# UCirKitBreadboardTop-0823.net
KiCad netlist of a schematic drawn in EAGLE
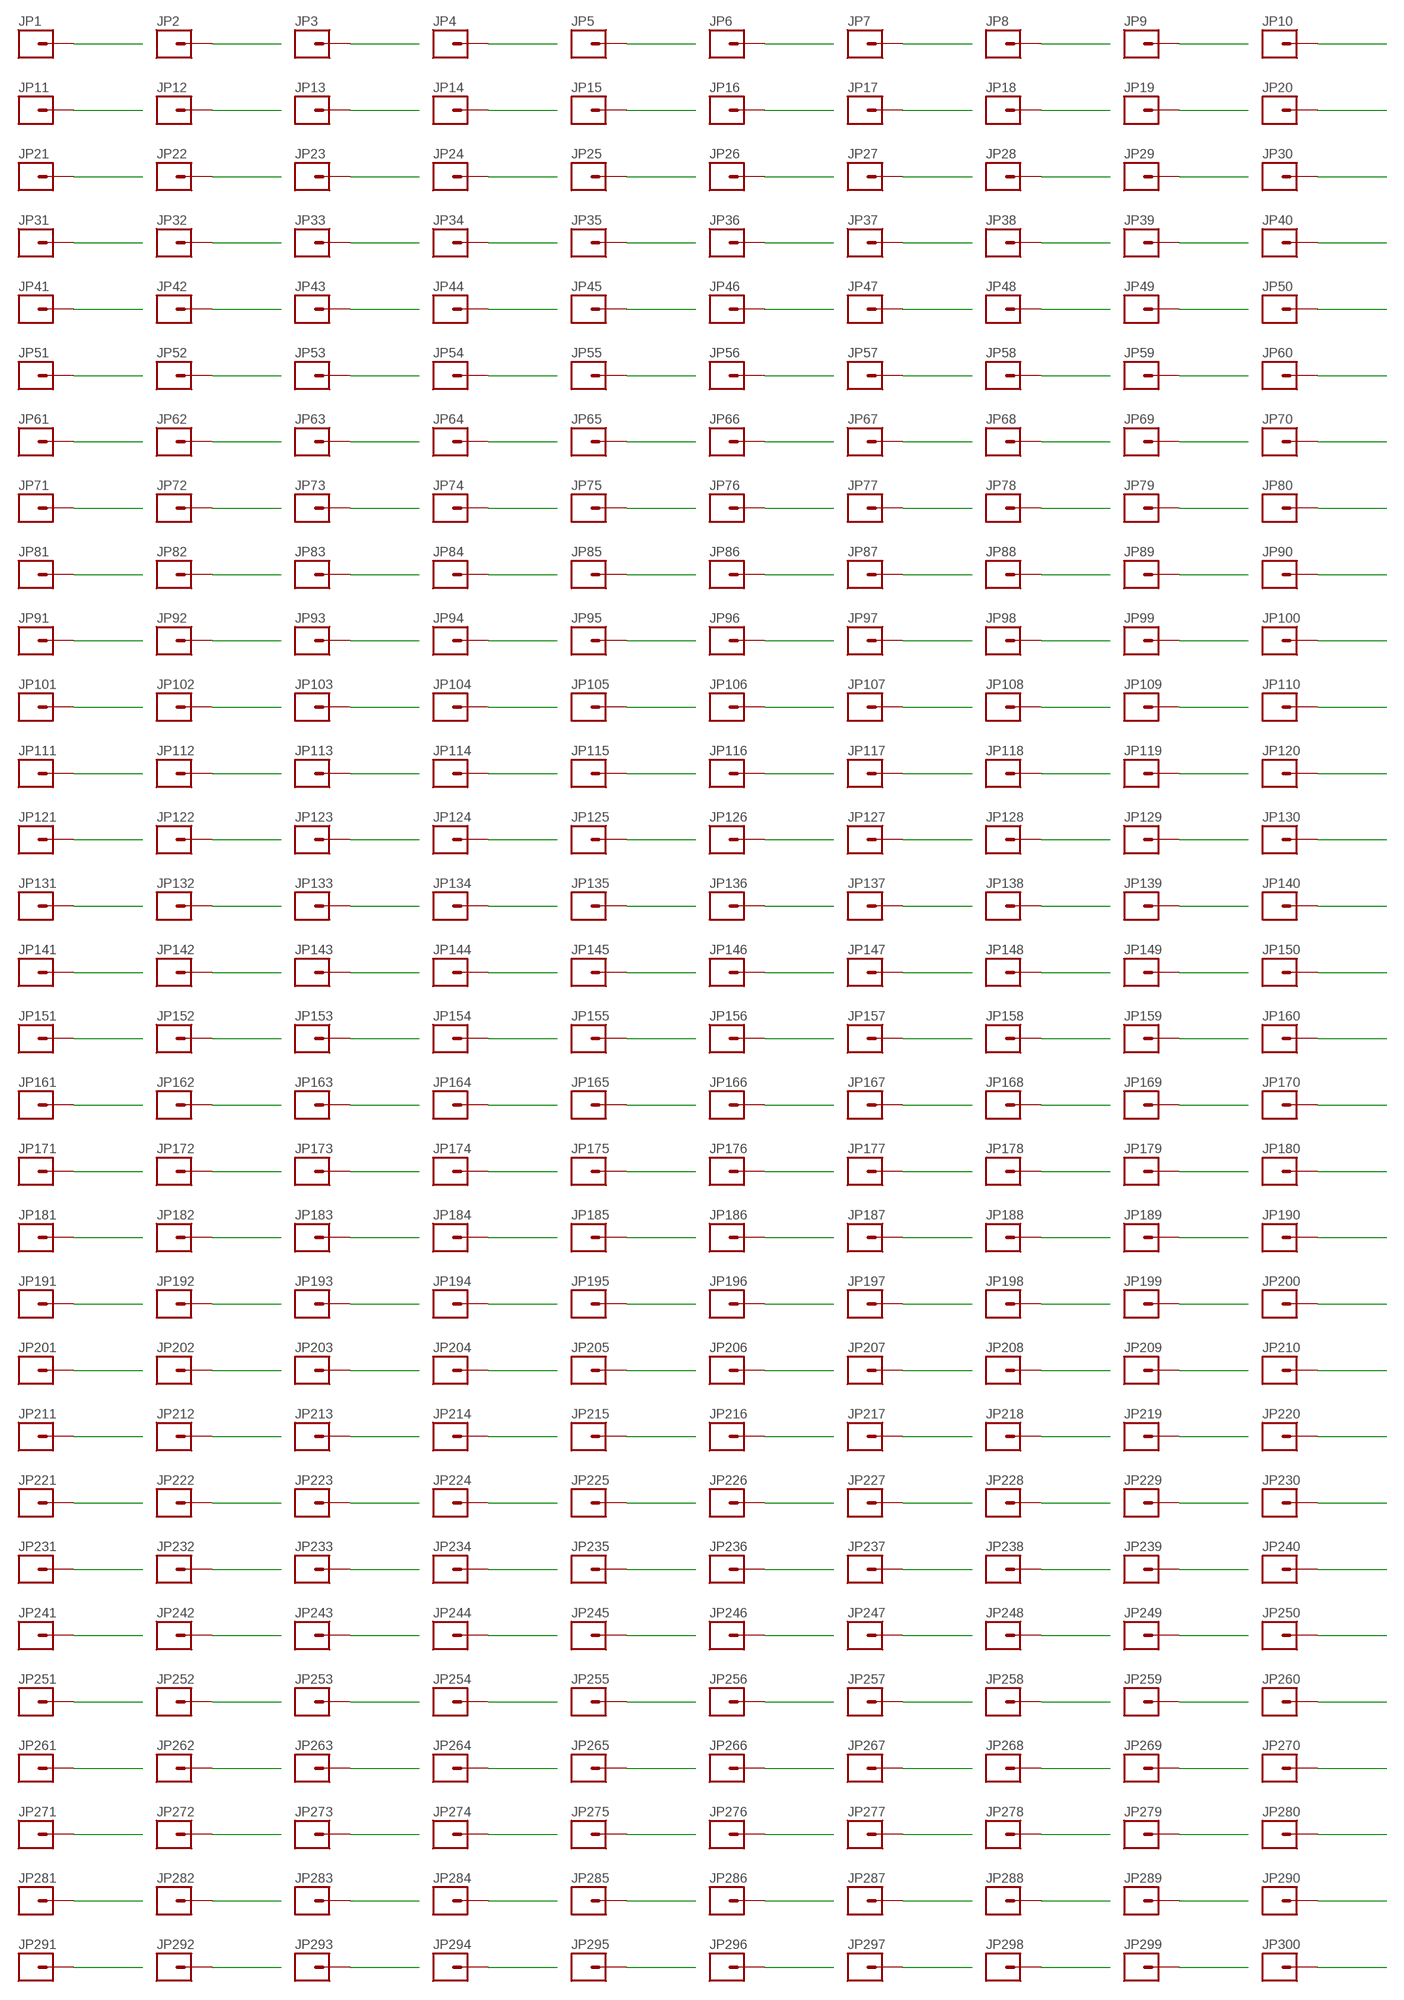
[diagram p0: schematic, sheet 1, part 1 of 2]
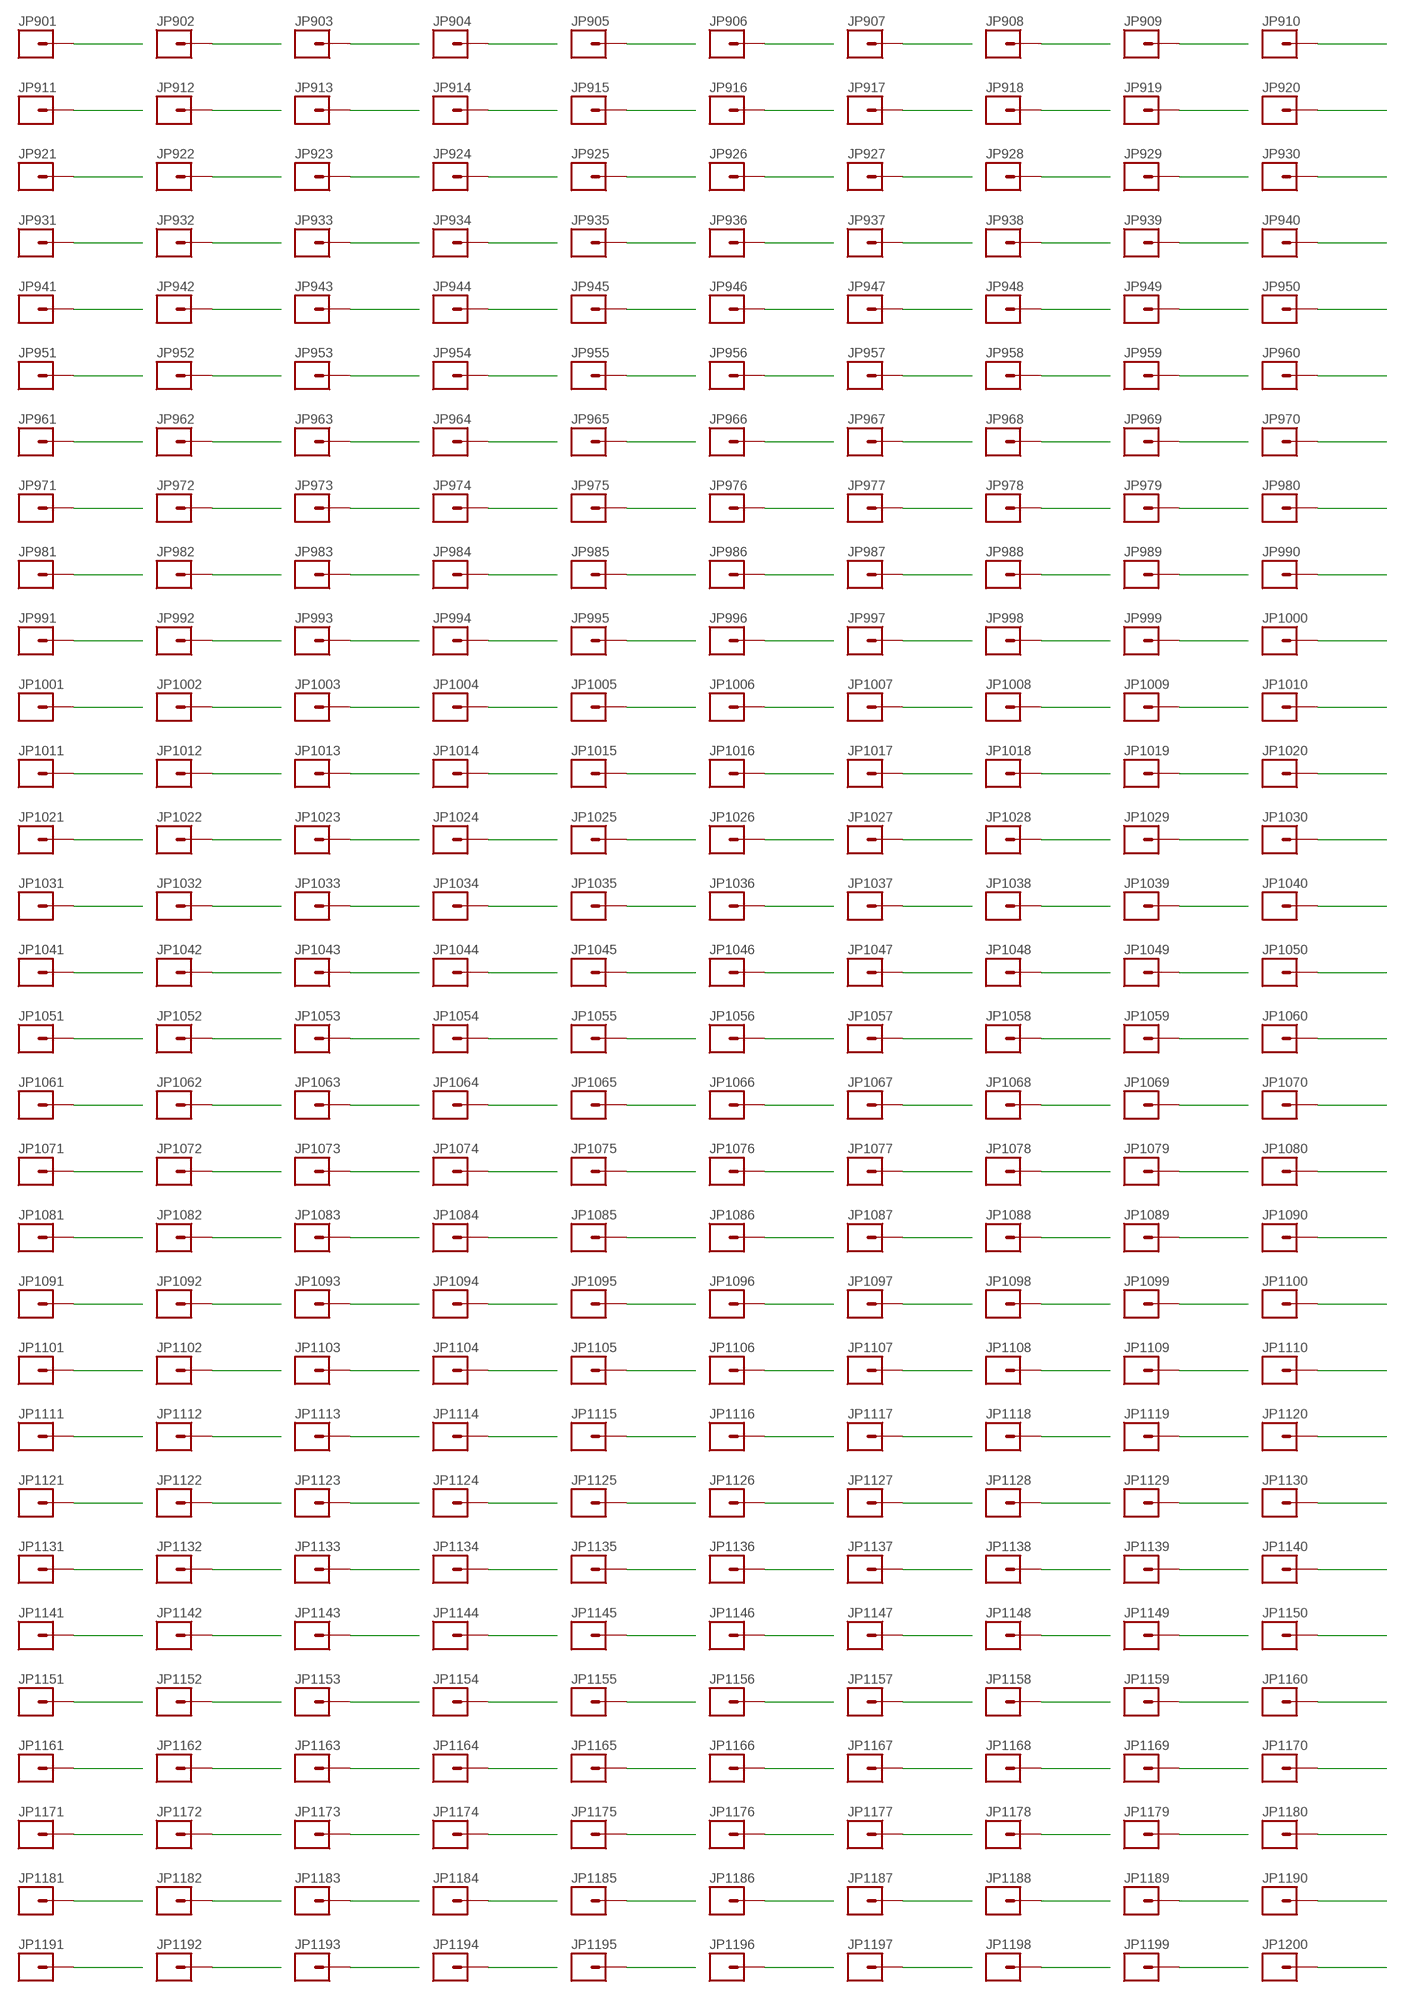
[diagram p1: schematic, sheet 1, part 2 of 2]

(export (version "E")
  (design (tool "Eeschema 10.0.6"))
  (components
    (comp (ref "JP1")
      (value "M01PTH_WITHOUT_TEXT")
      (footprint "eagle-import:1X01_WITHOUT_TEXT")
      (libsource (lib "eagle-import") (part "M01PTH_WITHOUT_TEXT"))
    )
    (comp (ref "JP2")
      (value "M01PTH_WITHOUT_TEXT")
      (footprint "eagle-import:1X01_WITHOUT_TEXT")
      (libsource (lib "eagle-import") (part "M01PTH_WITHOUT_TEXT"))
    )
    (comp (ref "JP3")
      (value "M01PTH_WITHOUT_TEXT")
      (footprint "eagle-import:1X01_WITHOUT_TEXT")
      (libsource (lib "eagle-import") (part "M01PTH_WITHOUT_TEXT"))
    )
    (comp (ref "JP4")
      (value "M01PTH_WITHOUT_TEXT")
      (footprint "eagle-import:1X01_WITHOUT_TEXT")
      (libsource (lib "eagle-import") (part "M01PTH_WITHOUT_TEXT"))
    )
    (comp (ref "JP5")
      (value "M01PTH_WITHOUT_TEXT")
      (footprint "eagle-import:1X01_WITHOUT_TEXT")
      (libsource (lib "eagle-import") (part "M01PTH_WITHOUT_TEXT"))
    )
    (comp (ref "JP6")
      (value "M01PTH_WITHOUT_TEXT")
      (footprint "eagle-import:1X01_WITHOUT_TEXT")
      (libsource (lib "eagle-import") (part "M01PTH_WITHOUT_TEXT"))
    )
    (comp (ref "JP7")
      (value "M01PTH_WITHOUT_TEXT")
      (footprint "eagle-import:1X01_WITHOUT_TEXT")
      (libsource (lib "eagle-import") (part "M01PTH_WITHOUT_TEXT"))
    )
    (comp (ref "JP8")
      (value "M01PTH_WITHOUT_TEXT")
      (footprint "eagle-import:1X01_WITHOUT_TEXT")
      (libsource (lib "eagle-import") (part "M01PTH_WITHOUT_TEXT"))
    )
    (comp (ref "JP9")
      (value "M01PTH_WITHOUT_TEXT")
      (footprint "eagle-import:1X01_WITHOUT_TEXT")
      (libsource (lib "eagle-import") (part "M01PTH_WITHOUT_TEXT"))
    )
    (comp (ref "JP10")
      (value "M01PTH_WITHOUT_TEXT")
      (footprint "eagle-import:1X01_WITHOUT_TEXT")
      (libsource (lib "eagle-import") (part "M01PTH_WITHOUT_TEXT"))
    )
    (comp (ref "JP11")
      (value "M01PTH_WITHOUT_TEXT")
      (footprint "eagle-import:1X01_WITHOUT_TEXT")
      (libsource (lib "eagle-import") (part "M01PTH_WITHOUT_TEXT"))
    )
    (comp (ref "JP12")
      (value "M01PTH_WITHOUT_TEXT")
      (footprint "eagle-import:1X01_WITHOUT_TEXT")
      (libsource (lib "eagle-import") (part "M01PTH_WITHOUT_TEXT"))
    )
    (comp (ref "JP13")
      (value "M01PTH_WITHOUT_TEXT")
      (footprint "eagle-import:1X01_WITHOUT_TEXT")
      (libsource (lib "eagle-import") (part "M01PTH_WITHOUT_TEXT"))
    )
    (comp (ref "JP14")
      (value "M01PTH_WITHOUT_TEXT")
      (footprint "eagle-import:1X01_WITHOUT_TEXT")
      (libsource (lib "eagle-import") (part "M01PTH_WITHOUT_TEXT"))
    )
    (comp (ref "JP15")
      (value "M01PTH_WITHOUT_TEXT")
      (footprint "eagle-import:1X01_WITHOUT_TEXT")
      (libsource (lib "eagle-import") (part "M01PTH_WITHOUT_TEXT"))
    )
    (comp (ref "JP16")
      (value "M01PTH_WITHOUT_TEXT")
      (footprint "eagle-import:1X01_WITHOUT_TEXT")
      (libsource (lib "eagle-import") (part "M01PTH_WITHOUT_TEXT"))
    )
    (comp (ref "JP17")
      (value "M01PTH_WITHOUT_TEXT")
      (footprint "eagle-import:1X01_WITHOUT_TEXT")
      (libsource (lib "eagle-import") (part "M01PTH_WITHOUT_TEXT"))
    )
    (comp (ref "JP18")
      (value "M01PTH_WITHOUT_TEXT")
      (footprint "eagle-import:1X01_WITHOUT_TEXT")
      (libsource (lib "eagle-import") (part "M01PTH_WITHOUT_TEXT"))
    )
    (comp (ref "JP19")
      (value "M01PTH_WITHOUT_TEXT")
      (footprint "eagle-import:1X01_WITHOUT_TEXT")
      (libsource (lib "eagle-import") (part "M01PTH_WITHOUT_TEXT"))
    )
    (comp (ref "JP20")
      (value "M01PTH_WITHOUT_TEXT")
      (footprint "eagle-import:1X01_WITHOUT_TEXT")
      (libsource (lib "eagle-import") (part "M01PTH_WITHOUT_TEXT"))
    )
    (comp (ref "JP21")
      (value "M01PTH_WITHOUT_TEXT")
      (footprint "eagle-import:1X01_WITHOUT_TEXT")
      (libsource (lib "eagle-import") (part "M01PTH_WITHOUT_TEXT"))
    )
    (comp (ref "JP22")
      (value "M01PTH_WITHOUT_TEXT")
      (footprint "eagle-import:1X01_WITHOUT_TEXT")
      (libsource (lib "eagle-import") (part "M01PTH_WITHOUT_TEXT"))
    )
    (comp (ref "JP23")
      (value "M01PTH_WITHOUT_TEXT")
      (footprint "eagle-import:1X01_WITHOUT_TEXT")
      (libsource (lib "eagle-import") (part "M01PTH_WITHOUT_TEXT"))
    )
    (comp (ref "JP24")
      (value "M01PTH_WITHOUT_TEXT")
      (footprint "eagle-import:1X01_WITHOUT_TEXT")
      (libsource (lib "eagle-import") (part "M01PTH_WITHOUT_TEXT"))
    )
    (comp (ref "JP25")
      (value "M01PTH_WITHOUT_TEXT")
      (footprint "eagle-import:1X01_WITHOUT_TEXT")
      (libsource (lib "eagle-import") (part "M01PTH_WITHOUT_TEXT"))
    )
    (comp (ref "JP26")
      (value "M01PTH_WITHOUT_TEXT")
      (footprint "eagle-import:1X01_WITHOUT_TEXT")
      (libsource (lib "eagle-import") (part "M01PTH_WITHOUT_TEXT"))
    )
    (comp (ref "JP27")
      (value "M01PTH_WITHOUT_TEXT")
      (footprint "eagle-import:1X01_WITHOUT_TEXT")
      (libsource (lib "eagle-import") (part "M01PTH_WITHOUT_TEXT"))
    )
    (comp (ref "JP28")
      (value "M01PTH_WITHOUT_TEXT")
      (footprint "eagle-import:1X01_WITHOUT_TEXT")
      (libsource (lib "eagle-import") (part "M01PTH_WITHOUT_TEXT"))
    )
    (comp (ref "JP29")
      (value "M01PTH_WITHOUT_TEXT")
      (footprint "eagle-import:1X01_WITHOUT_TEXT")
      (libsource (lib "eagle-import") (part "M01PTH_WITHOUT_TEXT"))
    )
    (comp (ref "JP30")
      (value "M01PTH_WITHOUT_TEXT")
      (footprint "eagle-import:1X01_WITHOUT_TEXT")
      (libsource (lib "eagle-import") (part "M01PTH_WITHOUT_TEXT"))
    )
    (comp (ref "JP31")
      (value "M01PTH_WITHOUT_TEXT")
      (footprint "eagle-import:1X01_WITHOUT_TEXT")
      (libsource (lib "eagle-import") (part "M01PTH_WITHOUT_TEXT"))
    )
    (comp (ref "JP32")
      (value "M01PTH_WITHOUT_TEXT")
      (footprint "eagle-import:1X01_WITHOUT_TEXT")
      (libsource (lib "eagle-import") (part "M01PTH_WITHOUT_TEXT"))
    )
    (comp (ref "JP33")
      (value "M01PTH_WITHOUT_TEXT")
      (footprint "eagle-import:1X01_WITHOUT_TEXT")
      (libsource (lib "eagle-import") (part "M01PTH_WITHOUT_TEXT"))
    )
    (comp (ref "JP34")
      (value "M01PTH_WITHOUT_TEXT")
      (footprint "eagle-import:1X01_WITHOUT_TEXT")
      (libsource (lib "eagle-import") (part "M01PTH_WITHOUT_TEXT"))
    )
    (comp (ref "JP35")
      (value "M01PTH_WITHOUT_TEXT")
      (footprint "eagle-import:1X01_WITHOUT_TEXT")
      (libsource (lib "eagle-import") (part "M01PTH_WITHOUT_TEXT"))
    )
    (comp (ref "JP36")
      (value "M01PTH_WITHOUT_TEXT")
      (footprint "eagle-import:1X01_WITHOUT_TEXT")
      (libsource (lib "eagle-import") (part "M01PTH_WITHOUT_TEXT"))
    )
    (comp (ref "JP37")
      (value "M01PTH_WITHOUT_TEXT")
      (footprint "eagle-import:1X01_WITHOUT_TEXT")
      (libsource (lib "eagle-import") (part "M01PTH_WITHOUT_TEXT"))
    )
    (comp (ref "JP38")
      (value "M01PTH_WITHOUT_TEXT")
      (footprint "eagle-import:1X01_WITHOUT_TEXT")
      (libsource (lib "eagle-import") (part "M01PTH_WITHOUT_TEXT"))
    )
    (comp (ref "JP39")
      (value "M01PTH_WITHOUT_TEXT")
      (footprint "eagle-import:1X01_WITHOUT_TEXT")
      (libsource (lib "eagle-import") (part "M01PTH_WITHOUT_TEXT"))
    )
    (comp (ref "JP40")
      (value "M01PTH_WITHOUT_TEXT")
      (footprint "eagle-import:1X01_WITHOUT_TEXT")
      (libsource (lib "eagle-import") (part "M01PTH_WITHOUT_TEXT"))
    )
    (comp (ref "JP41")
      (value "M01PTH_WITHOUT_TEXT")
      (footprint "eagle-import:1X01_WITHOUT_TEXT")
      (libsource (lib "eagle-import") (part "M01PTH_WITHOUT_TEXT"))
    )
    (comp (ref "JP42")
      (value "M01PTH_WITHOUT_TEXT")
      (footprint "eagle-import:1X01_WITHOUT_TEXT")
      (libsource (lib "eagle-import") (part "M01PTH_WITHOUT_TEXT"))
    )
    (comp (ref "JP43")
      (value "M01PTH_WITHOUT_TEXT")
      (footprint "eagle-import:1X01_WITHOUT_TEXT")
      (libsource (lib "eagle-import") (part "M01PTH_WITHOUT_TEXT"))
    )
    (comp (ref "JP44")
      (value "M01PTH_WITHOUT_TEXT")
      (footprint "eagle-import:1X01_WITHOUT_TEXT")
      (libsource (lib "eagle-import") (part "M01PTH_WITHOUT_TEXT"))
    )
    (comp (ref "JP45")
      (value "M01PTH_WITHOUT_TEXT")
      (footprint "eagle-import:1X01_WITHOUT_TEXT")
      (libsource (lib "eagle-import") (part "M01PTH_WITHOUT_TEXT"))
    )
    (comp (ref "JP46")
      (value "M01PTH_WITHOUT_TEXT")
      (footprint "eagle-import:1X01_WITHOUT_TEXT")
      (libsource (lib "eagle-import") (part "M01PTH_WITHOUT_TEXT"))
    )
    (comp (ref "JP47")
      (value "M01PTH_WITHOUT_TEXT")
      (footprint "eagle-import:1X01_WITHOUT_TEXT")
      (libsource (lib "eagle-import") (part "M01PTH_WITHOUT_TEXT"))
    )
    (comp (ref "JP48")
      (value "M01PTH_WITHOUT_TEXT")
      (footprint "eagle-import:1X01_WITHOUT_TEXT")
      (libsource (lib "eagle-import") (part "M01PTH_WITHOUT_TEXT"))
    )
    (comp (ref "JP49")
      (value "M01PTH_WITHOUT_TEXT")
      (footprint "eagle-import:1X01_WITHOUT_TEXT")
      (libsource (lib "eagle-import") (part "M01PTH_WITHOUT_TEXT"))
    )
    (comp (ref "JP50")
      (value "M01PTH_WITHOUT_TEXT")
      (footprint "eagle-import:1X01_WITHOUT_TEXT")
      (libsource (lib "eagle-import") (part "M01PTH_WITHOUT_TEXT"))
    )
    (comp (ref "JP51")
      (value "M01PTH_WITHOUT_TEXT")
      (footprint "eagle-import:1X01_WITHOUT_TEXT")
      (libsource (lib "eagle-import") (part "M01PTH_WITHOUT_TEXT"))
    )
    (comp (ref "JP52")
      (value "M01PTH_WITHOUT_TEXT")
      (footprint "eagle-import:1X01_WITHOUT_TEXT")
      (libsource (lib "eagle-import") (part "M01PTH_WITHOUT_TEXT"))
    )
    (comp (ref "JP53")
      (value "M01PTH_WITHOUT_TEXT")
      (footprint "eagle-import:1X01_WITHOUT_TEXT")
      (libsource (lib "eagle-import") (part "M01PTH_WITHOUT_TEXT"))
    )
    (comp (ref "JP54")
      (value "M01PTH_WITHOUT_TEXT")
      (footprint "eagle-import:1X01_WITHOUT_TEXT")
      (libsource (lib "eagle-import") (part "M01PTH_WITHOUT_TEXT"))
    )
    (comp (ref "JP55")
      (value "M01PTH_WITHOUT_TEXT")
      (footprint "eagle-import:1X01_WITHOUT_TEXT")
      (libsource (lib "eagle-import") (part "M01PTH_WITHOUT_TEXT"))
    )
    (comp (ref "JP56")
      (value "M01PTH_WITHOUT_TEXT")
      (footprint "eagle-import:1X01_WITHOUT_TEXT")
      (libsource (lib "eagle-import") (part "M01PTH_WITHOUT_TEXT"))
    )
    (comp (ref "JP57")
      (value "M01PTH_WITHOUT_TEXT")
      (footprint "eagle-import:1X01_WITHOUT_TEXT")
      (libsource (lib "eagle-import") (part "M01PTH_WITHOUT_TEXT"))
    )
    (comp (ref "JP58")
      (value "M01PTH_WITHOUT_TEXT")
      (footprint "eagle-import:1X01_WITHOUT_TEXT")
      (libsource (lib "eagle-import") (part "M01PTH_WITHOUT_TEXT"))
    )
    (comp (ref "JP59")
      (value "M01PTH_WITHOUT_TEXT")
      (footprint "eagle-import:1X01_WITHOUT_TEXT")
      (libsource (lib "eagle-import") (part "M01PTH_WITHOUT_TEXT"))
    )
    (comp (ref "JP60")
      (value "M01PTH_WITHOUT_TEXT")
      (footprint "eagle-import:1X01_WITHOUT_TEXT")
      (libsource (lib "eagle-import") (part "M01PTH_WITHOUT_TEXT"))
    )
    (comp (ref "JP61")
      (value "M01PTH_WITHOUT_TEXT")
      (footprint "eagle-import:1X01_WITHOUT_TEXT")
      (libsource (lib "eagle-import") (part "M01PTH_WITHOUT_TEXT"))
    )
    (comp (ref "JP62")
      (value "M01PTH_WITHOUT_TEXT")
      (footprint "eagle-import:1X01_WITHOUT_TEXT")
      (libsource (lib "eagle-import") (part "M01PTH_WITHOUT_TEXT"))
    )
    (comp (ref "JP63")
      (value "M01PTH_WITHOUT_TEXT")
      (footprint "eagle-import:1X01_WITHOUT_TEXT")
      (libsource (lib "eagle-import") (part "M01PTH_WITHOUT_TEXT"))
    )
    (comp (ref "JP64")
      (value "M01PTH_WITHOUT_TEXT")
      (footprint "eagle-import:1X01_WITHOUT_TEXT")
      (libsource (lib "eagle-import") (part "M01PTH_WITHOUT_TEXT"))
    )
    (comp (ref "JP65")
      (value "M01PTH_WITHOUT_TEXT")
      (footprint "eagle-import:1X01_WITHOUT_TEXT")
      (libsource (lib "eagle-import") (part "M01PTH_WITHOUT_TEXT"))
    )
    (comp (ref "JP66")
      (value "M01PTH_WITHOUT_TEXT")
      (footprint "eagle-import:1X01_WITHOUT_TEXT")
      (libsource (lib "eagle-import") (part "M01PTH_WITHOUT_TEXT"))
    )
    (comp (ref "JP67")
      (value "M01PTH_WITHOUT_TEXT")
      (footprint "eagle-import:1X01_WITHOUT_TEXT")
      (libsource (lib "eagle-import") (part "M01PTH_WITHOUT_TEXT"))
    )
    (comp (ref "JP68")
      (value "M01PTH_WITHOUT_TEXT")
      (footprint "eagle-import:1X01_WITHOUT_TEXT")
      (libsource (lib "eagle-import") (part "M01PTH_WITHOUT_TEXT"))
    )
    (comp (ref "JP69")
      (value "M01PTH_WITHOUT_TEXT")
      (footprint "eagle-import:1X01_WITHOUT_TEXT")
      (libsource (lib "eagle-import") (part "M01PTH_WITHOUT_TEXT"))
    )
    (comp (ref "JP70")
      (value "M01PTH_WITHOUT_TEXT")
      (footprint "eagle-import:1X01_WITHOUT_TEXT")
      (libsource (lib "eagle-import") (part "M01PTH_WITHOUT_TEXT"))
    )
    (comp (ref "JP71")
      (value "M01PTH_WITHOUT_TEXT")
      (footprint "eagle-import:1X01_WITHOUT_TEXT")
      (libsource (lib "eagle-import") (part "M01PTH_WITHOUT_TEXT"))
    )
    (comp (ref "JP72")
      (value "M01PTH_WITHOUT_TEXT")
      (footprint "eagle-import:1X01_WITHOUT_TEXT")
      (libsource (lib "eagle-import") (part "M01PTH_WITHOUT_TEXT"))
    )
    (comp (ref "JP73")
      (value "M01PTH_WITHOUT_TEXT")
      (footprint "eagle-import:1X01_WITHOUT_TEXT")
      (libsource (lib "eagle-import") (part "M01PTH_WITHOUT_TEXT"))
    )
    (comp (ref "JP74")
      (value "M01PTH_WITHOUT_TEXT")
      (footprint "eagle-import:1X01_WITHOUT_TEXT")
      (libsource (lib "eagle-import") (part "M01PTH_WITHOUT_TEXT"))
    )
    (comp (ref "JP75")
      (value "M01PTH_WITHOUT_TEXT")
      (footprint "eagle-import:1X01_WITHOUT_TEXT")
      (libsource (lib "eagle-import") (part "M01PTH_WITHOUT_TEXT"))
    )
    (comp (ref "JP76")
      (value "M01PTH_WITHOUT_TEXT")
      (footprint "eagle-import:1X01_WITHOUT_TEXT")
      (libsource (lib "eagle-import") (part "M01PTH_WITHOUT_TEXT"))
    )
    (comp (ref "JP77")
      (value "M01PTH_WITHOUT_TEXT")
      (footprint "eagle-import:1X01_WITHOUT_TEXT")
      (libsource (lib "eagle-import") (part "M01PTH_WITHOUT_TEXT"))
    )
    (comp (ref "JP78")
      (value "M01PTH_WITHOUT_TEXT")
      (footprint "eagle-import:1X01_WITHOUT_TEXT")
      (libsource (lib "eagle-import") (part "M01PTH_WITHOUT_TEXT"))
    )
    (comp (ref "JP79")
      (value "M01PTH_WITHOUT_TEXT")
      (footprint "eagle-import:1X01_WITHOUT_TEXT")
      (libsource (lib "eagle-import") (part "M01PTH_WITHOUT_TEXT"))
    )
    (comp (ref "JP80")
      (value "M01PTH_WITHOUT_TEXT")
      (footprint "eagle-import:1X01_WITHOUT_TEXT")
      (libsource (lib "eagle-import") (part "M01PTH_WITHOUT_TEXT"))
    )
    (comp (ref "JP81")
      (value "M01PTH_WITHOUT_TEXT")
      (footprint "eagle-import:1X01_WITHOUT_TEXT")
      (libsource (lib "eagle-import") (part "M01PTH_WITHOUT_TEXT"))
    )
    (comp (ref "JP82")
      (value "M01PTH_WITHOUT_TEXT")
      (footprint "eagle-import:1X01_WITHOUT_TEXT")
      (libsource (lib "eagle-import") (part "M01PTH_WITHOUT_TEXT"))
    )
    (comp (ref "JP83")
      (value "M01PTH_WITHOUT_TEXT")
      (footprint "eagle-import:1X01_WITHOUT_TEXT")
      (libsource (lib "eagle-import") (part "M01PTH_WITHOUT_TEXT"))
    )
    (comp (ref "JP84")
      (value "M01PTH_WITHOUT_TEXT")
      (footprint "eagle-import:1X01_WITHOUT_TEXT")
      (libsource (lib "eagle-import") (part "M01PTH_WITHOUT_TEXT"))
    )
    (comp (ref "JP85")
      (value "M01PTH_WITHOUT_TEXT")
      (footprint "eagle-import:1X01_WITHOUT_TEXT")
      (libsource (lib "eagle-import") (part "M01PTH_WITHOUT_TEXT"))
    )
    (comp (ref "JP86")
      (value "M01PTH_WITHOUT_TEXT")
      (footprint "eagle-import:1X01_WITHOUT_TEXT")
      (libsource (lib "eagle-import") (part "M01PTH_WITHOUT_TEXT"))
    )
    (comp (ref "JP87")
      (value "M01PTH_WITHOUT_TEXT")
      (footprint "eagle-import:1X01_WITHOUT_TEXT")
      (libsource (lib "eagle-import") (part "M01PTH_WITHOUT_TEXT"))
    )
    (comp (ref "JP88")
      (value "M01PTH_WITHOUT_TEXT")
      (footprint "eagle-import:1X01_WITHOUT_TEXT")
      (libsource (lib "eagle-import") (part "M01PTH_WITHOUT_TEXT"))
    )
    (comp (ref "JP89")
      (value "M01PTH_WITHOUT_TEXT")
      (footprint "eagle-import:1X01_WITHOUT_TEXT")
      (libsource (lib "eagle-import") (part "M01PTH_WITHOUT_TEXT"))
    )
    (comp (ref "JP90")
      (value "M01PTH_WITHOUT_TEXT")
      (footprint "eagle-import:1X01_WITHOUT_TEXT")
      (libsource (lib "eagle-import") (part "M01PTH_WITHOUT_TEXT"))
    )
    (comp (ref "JP91")
      (value "M01PTH_WITHOUT_TEXT")
      (footprint "eagle-import:1X01_WITHOUT_TEXT")
      (libsource (lib "eagle-import") (part "M01PTH_WITHOUT_TEXT"))
    )
    (comp (ref "JP92")
      (value "M01PTH_WITHOUT_TEXT")
      (footprint "eagle-import:1X01_WITHOUT_TEXT")
      (libsource (lib "eagle-import") (part "M01PTH_WITHOUT_TEXT"))
    )
    (comp (ref "JP93")
      (value "M01PTH_WITHOUT_TEXT")
      (footprint "eagle-import:1X01_WITHOUT_TEXT")
      (libsource (lib "eagle-import") (part "M01PTH_WITHOUT_TEXT"))
    )
    (comp (ref "JP94")
      (value "M01PTH_WITHOUT_TEXT")
      (footprint "eagle-import:1X01_WITHOUT_TEXT")
      (libsource (lib "eagle-import") (part "M01PTH_WITHOUT_TEXT"))
    )
    (comp (ref "JP95")
      (value "M01PTH_WITHOUT_TEXT")
      (footprint "eagle-import:1X01_WITHOUT_TEXT")
      (libsource (lib "eagle-import") (part "M01PTH_WITHOUT_TEXT"))
    )
    (comp (ref "JP96")
      (value "M01PTH_WITHOUT_TEXT")
      (footprint "eagle-import:1X01_WITHOUT_TEXT")
      (libsource (lib "eagle-import") (part "M01PTH_WITHOUT_TEXT"))
    )
    (comp (ref "JP97")
      (value "M01PTH_WITHOUT_TEXT")
      (footprint "eagle-import:1X01_WITHOUT_TEXT")
      (libsource (lib "eagle-import") (part "M01PTH_WITHOUT_TEXT"))
    )
    (comp (ref "JP98")
      (value "M01PTH_WITHOUT_TEXT")
      (footprint "eagle-import:1X01_WITHOUT_TEXT")
      (libsource (lib "eagle-import") (part "M01PTH_WITHOUT_TEXT"))
    )
    (comp (ref "JP99")
      (value "M01PTH_WITHOUT_TEXT")
      (footprint "eagle-import:1X01_WITHOUT_TEXT")
      (libsource (lib "eagle-import") (part "M01PTH_WITHOUT_TEXT"))
    )
    (comp (ref "JP100")
      (value "M01PTH_WITHOUT_TEXT")
      (footprint "eagle-import:1X01_WITHOUT_TEXT")
      (libsource (lib "eagle-import") (part "M01PTH_WITHOUT_TEXT"))
    )
    (comp (ref "JP101")
      (value "M01PTH_WITHOUT_TEXT")
      (footprint "eagle-import:1X01_WITHOUT_TEXT")
      (libsource (lib "eagle-import") (part "M01PTH_WITHOUT_TEXT"))
    )
    (comp (ref "JP102")
      (value "M01PTH_WITHOUT_TEXT")
      (footprint "eagle-import:1X01_WITHOUT_TEXT")
      (libsource (lib "eagle-import") (part "M01PTH_WITHOUT_TEXT"))
    )
    (comp (ref "JP103")
      (value "M01PTH_WITHOUT_TEXT")
      (footprint "eagle-import:1X01_WITHOUT_TEXT")
      (libsource (lib "eagle-import") (part "M01PTH_WITHOUT_TEXT"))
    )
    (comp (ref "JP104")
      (value "M01PTH_WITHOUT_TEXT")
      (footprint "eagle-import:1X01_WITHOUT_TEXT")
      (libsource (lib "eagle-import") (part "M01PTH_WITHOUT_TEXT"))
    )
    (comp (ref "JP105")
      (value "M01PTH_WITHOUT_TEXT")
      (footprint "eagle-import:1X01_WITHOUT_TEXT")
      (libsource (lib "eagle-import") (part "M01PTH_WITHOUT_TEXT"))
    )
    (comp (ref "JP106")
      (value "M01PTH_WITHOUT_TEXT")
      (footprint "eagle-import:1X01_WITHOUT_TEXT")
      (libsource (lib "eagle-import") (part "M01PTH_WITHOUT_TEXT"))
    )
    (comp (ref "JP107")
      (value "M01PTH_WITHOUT_TEXT")
      (footprint "eagle-import:1X01_WITHOUT_TEXT")
      (libsource (lib "eagle-import") (part "M01PTH_WITHOUT_TEXT"))
    )
    (comp (ref "JP108")
      (value "M01PTH_WITHOUT_TEXT")
      (footprint "eagle-import:1X01_WITHOUT_TEXT")
      (libsource (lib "eagle-import") (part "M01PTH_WITHOUT_TEXT"))
    )
    (comp (ref "JP109")
      (value "M01PTH_WITHOUT_TEXT")
      (footprint "eagle-import:1X01_WITHOUT_TEXT")
      (libsource (lib "eagle-import") (part "M01PTH_WITHOUT_TEXT"))
    )
    (comp (ref "JP110")
      (value "M01PTH_WITHOUT_TEXT")
      (footprint "eagle-import:1X01_WITHOUT_TEXT")
      (libsource (lib "eagle-import") (part "M01PTH_WITHOUT_TEXT"))
    )
    (comp (ref "JP111")
      (value "M01PTH_WITHOUT_TEXT")
      (footprint "eagle-import:1X01_WITHOUT_TEXT")
      (libsource (lib "eagle-import") (part "M01PTH_WITHOUT_TEXT"))
    )
    (comp (ref "JP112")
      (value "M01PTH_WITHOUT_TEXT")
      (footprint "eagle-import:1X01_WITHOUT_TEXT")
      (libsource (lib "eagle-import") (part "M01PTH_WITHOUT_TEXT"))
    )
    (comp (ref "JP113")
      (value "M01PTH_WITHOUT_TEXT")
      (footprint "eagle-import:1X01_WITHOUT_TEXT")
      (libsource (lib "eagle-import") (part "M01PTH_WITHOUT_TEXT"))
    )
    (comp (ref "JP114")
      (value "M01PTH_WITHOUT_TEXT")
      (footprint "eagle-import:1X01_WITHOUT_TEXT")
      (libsource (lib "eagle-import") (part "M01PTH_WITHOUT_TEXT"))
    )
    (comp (ref "JP115")
      (value "M01PTH_WITHOUT_TEXT")
      (footprint "eagle-import:1X01_WITHOUT_TEXT")
      (libsource (lib "eagle-import") (part "M01PTH_WITHOUT_TEXT"))
    )
    (comp (ref "JP116")
      (value "M01PTH_WITHOUT_TEXT")
      (footprint "eagle-import:1X01_WITHOUT_TEXT")
      (libsource (lib "eagle-import") (part "M01PTH_WITHOUT_TEXT"))
    )
    (comp (ref "JP117")
      (value "M01PTH_WITHOUT_TEXT")
      (footprint "eagle-import:1X01_WITHOUT_TEXT")
      (libsource (lib "eagle-import") (part "M01PTH_WITHOUT_TEXT"))
    )
    (comp (ref "JP118")
      (value "M01PTH_WITHOUT_TEXT")
      (footprint "eagle-import:1X01_WITHOUT_TEXT")
      (libsource (lib "eagle-import") (part "M01PTH_WITHOUT_TEXT"))
    )
    (comp (ref "JP119")
      (value "M01PTH_WITHOUT_TEXT")
      (footprint "eagle-import:1X01_WITHOUT_TEXT")
      (libsource (lib "eagle-import") (part "M01PTH_WITHOUT_TEXT"))
    )
    (comp (ref "JP120")
      (value "M01PTH_WITHOUT_TEXT")
      (footprint "eagle-import:1X01_WITHOUT_TEXT")
      (libsource (lib "eagle-import") (part "M01PTH_WITHOUT_TEXT"))
    )
    (comp (ref "JP121")
      (value "M01PTH_WITHOUT_TEXT")
      (footprint "eagle-import:1X01_WITHOUT_TEXT")
      (libsource (lib "eagle-import") (part "M01PTH_WITHOUT_TEXT"))
    )
    (comp (ref "JP122")
      (value "M01PTH_WITHOUT_TEXT")
      (footprint "eagle-import:1X01_WITHOUT_TEXT")
      (libsource (lib "eagle-import") (part "M01PTH_WITHOUT_TEXT"))
    )
    (comp (ref "JP123")
      (value "M01PTH_WITHOUT_TEXT")
      (footprint "eagle-import:1X01_WITHOUT_TEXT")
      (libsource (lib "eagle-import") (part "M01PTH_WITHOUT_TEXT"))
    )
    (comp (ref "JP124")
      (value "M01PTH_WITHOUT_TEXT")
      (footprint "eagle-import:1X01_WITHOUT_TEXT")
      (libsource (lib "eagle-import") (part "M01PTH_WITHOUT_TEXT"))
    )
    (comp (ref "JP125")
      (value "M01PTH_WITHOUT_TEXT")
      (footprint "eagle-import:1X01_WITHOUT_TEXT")
      (libsource (lib "eagle-import") (part "M01PTH_WITHOUT_TEXT"))
    )
    (comp (ref "JP126")
      (value "M01PTH_WITHOUT_TEXT")
      (footprint "eagle-import:1X01_WITHOUT_TEXT")
      (libsource (lib "eagle-import") (part "M01PTH_WITHOUT_TEXT"))
    )
    (comp (ref "JP127")
      (value "M01PTH_WITHOUT_TEXT")
      (footprint "eagle-import:1X01_WITHOUT_TEXT")
      (libsource (lib "eagle-import") (part "M01PTH_WITHOUT_TEXT"))
    )
    (comp (ref "JP128")
      (value "M01PTH_WITHOUT_TEXT")
      (footprint "eagle-import:1X01_WITHOUT_TEXT")
      (libsource (lib "eagle-import") (part "M01PTH_WITHOUT_TEXT"))
    )
    (comp (ref "JP129")
      (value "M01PTH_WITHOUT_TEXT")
      (footprint "eagle-import:1X01_WITHOUT_TEXT")
      (libsource (lib "eagle-import") (part "M01PTH_WITHOUT_TEXT"))
    )
    (comp (ref "JP130")
      (value "M01PTH_WITHOUT_TEXT")
      (footprint "eagle-import:1X01_WITHOUT_TEXT")
      (libsource (lib "eagle-import") (part "M01PTH_WITHOUT_TEXT"))
    )
    (comp (ref "JP131")
      (value "M01PTH_WITHOUT_TEXT")
      (footprint "eagle-import:1X01_WITHOUT_TEXT")
      (libsource (lib "eagle-import") (part "M01PTH_WITHOUT_TEXT"))
    )
    (comp (ref "JP132")
      (value "M01PTH_WITHOUT_TEXT")
      (footprint "eagle-import:1X01_WITHOUT_TEXT")
      (libsource (lib "eagle-import") (part "M01PTH_WITHOUT_TEXT"))
    )
    (comp (ref "JP133")
      (value "M01PTH_WITHOUT_TEXT")
      (footprint "eagle-import:1X01_WITHOUT_TEXT")
      (libsource (lib "eagle-import") (part "M01PTH_WITHOUT_TEXT"))
    )
    (comp (ref "JP134")
      (value "M01PTH_WITHOUT_TEXT")
      (footprint "eagle-import:1X01_WITHOUT_TEXT")
      (libsource (lib "eagle-import") (part "M01PTH_WITHOUT_TEXT"))
    )
    (comp (ref "JP135")
      (value "M01PTH_WITHOUT_TEXT")
      (footprint "eagle-import:1X01_WITHOUT_TEXT")
      (libsource (lib "eagle-import") (part "M01PTH_WITHOUT_TEXT"))
    )
    (comp (ref "JP136")
      (value "M01PTH_WITHOUT_TEXT")
      (footprint "eagle-import:1X01_WITHOUT_TEXT")
      (libsource (lib "eagle-import") (part "M01PTH_WITHOUT_TEXT"))
    )
    (comp (ref "JP137")
      (value "M01PTH_WITHOUT_TEXT")
      (footprint "eagle-import:1X01_WITHOUT_TEXT")
      (libsource (lib "eagle-import") (part "M01PTH_WITHOUT_TEXT"))
    )
    (comp (ref "JP138")
      (value "M01PTH_WITHOUT_TEXT")
      (footprint "eagle-import:1X01_WITHOUT_TEXT")
      (libsource (lib "eagle-import") (part "M01PTH_WITHOUT_TEXT"))
    )
    (comp (ref "JP139")
      (value "M01PTH_WITHOUT_TEXT")
      (footprint "eagle-import:1X01_WITHOUT_TEXT")
      (libsource (lib "eagle-import") (part "M01PTH_WITHOUT_TEXT"))
    )
    (comp (ref "JP140")
      (value "M01PTH_WITHOUT_TEXT")
      (footprint "eagle-import:1X01_WITHOUT_TEXT")
      (libsource (lib "eagle-import") (part "M01PTH_WITHOUT_TEXT"))
    )
    (comp (ref "JP141")
      (value "M01PTH_WITHOUT_TEXT")
      (footprint "eagle-import:1X01_WITHOUT_TEXT")
      (libsource (lib "eagle-import") (part "M01PTH_WITHOUT_TEXT"))
    )
    (comp (ref "JP142")
      (value "M01PTH_WITHOUT_TEXT")
      (footprint "eagle-import:1X01_WITHOUT_TEXT")
      (libsource (lib "eagle-import") (part "M01PTH_WITHOUT_TEXT"))
    )
    (comp (ref "JP143")
      (value "M01PTH_WITHOUT_TEXT")
      (footprint "eagle-import:1X01_WITHOUT_TEXT")
      (libsource (lib "eagle-import") (part "M01PTH_WITHOUT_TEXT"))
    )
    (comp (ref "JP144")
      (value "M01PTH_WITHOUT_TEXT")
      (footprint "eagle-import:1X01_WITHOUT_TEXT")
      (libsource (lib "eagle-import") (part "M01PTH_WITHOUT_TEXT"))
    )
    (comp (ref "JP145")
      (value "M01PTH_WITHOUT_TEXT")
      (footprint "eagle-import:1X01_WITHOUT_TEXT")
      (libsource (lib "eagle-import") (part "M01PTH_WITHOUT_TEXT"))
    )
    (comp (ref "JP146")
      (value "M01PTH_WITHOUT_TEXT")
      (footprint "eagle-import:1X01_WITHOUT_TEXT")
      (libsource (lib "eagle-import") (part "M01PTH_WITHOUT_TEXT"))
    )
    (comp (ref "JP147")
      (value "M01PTH_WITHOUT_TEXT")
      (footprint "eagle-import:1X01_WITHOUT_TEXT")
      (libsource (lib "eagle-import") (part "M01PTH_WITHOUT_TEXT"))
    )
    (comp (ref "JP148")
      (value "M01PTH_WITHOUT_TEXT")
      (footprint "eagle-import:1X01_WITHOUT_TEXT")
      (libsource (lib "eagle-import") (part "M01PTH_WITHOUT_TEXT"))
    )
    (comp (ref "JP149")
      (value "M01PTH_WITHOUT_TEXT")
      (footprint "eagle-import:1X01_WITHOUT_TEXT")
      (libsource (lib "eagle-import") (part "M01PTH_WITHOUT_TEXT"))
    )
    (comp (ref "JP150")
      (value "M01PTH_WITHOUT_TEXT")
      (footprint "eagle-import:1X01_WITHOUT_TEXT")
      (libsource (lib "eagle-import") (part "M01PTH_WITHOUT_TEXT"))
    )
    (comp (ref "JP151")
      (value "M01PTH_WITHOUT_TEXT")
      (footprint "eagle-import:1X01_WITHOUT_TEXT")
      (libsource (lib "eagle-import") (part "M01PTH_WITHOUT_TEXT"))
    )
    (comp (ref "JP152")
      (value "M01PTH_WITHOUT_TEXT")
      (footprint "eagle-import:1X01_WITHOUT_TEXT")
      (libsource (lib "eagle-import") (part "M01PTH_WITHOUT_TEXT"))
    )
    (comp (ref "JP153")
      (value "M01PTH_WITHOUT_TEXT")
      (footprint "eagle-import:1X01_WITHOUT_TEXT")
      (libsource (lib "eagle-import") (part "M01PTH_WITHOUT_TEXT"))
    )
    (comp (ref "JP154")
      (value "M01PTH_WITHOUT_TEXT")
      (footprint "eagle-import:1X01_WITHOUT_TEXT")
      (libsource (lib "eagle-import") (part "M01PTH_WITHOUT_TEXT"))
    )
    (comp (ref "JP155")
      (value "M01PTH_WITHOUT_TEXT")
      (footprint "eagle-import:1X01_WITHOUT_TEXT")
      (libsource (lib "eagle-import") (part "M01PTH_WITHOUT_TEXT"))
    )
    (comp (ref "JP156")
      (value "M01PTH_WITHOUT_TEXT")
      (footprint "eagle-import:1X01_WITHOUT_TEXT")
      (libsource (lib "eagle-import") (part "M01PTH_WITHOUT_TEXT"))
    )
    (comp (ref "JP157")
      (value "M01PTH_WITHOUT_TEXT")
      (footprint "eagle-import:1X01_WITHOUT_TEXT")
      (libsource (lib "eagle-import") (part "M01PTH_WITHOUT_TEXT"))
    )
    (comp (ref "JP158")
      (value "M01PTH_WITHOUT_TEXT")
      (footprint "eagle-import:1X01_WITHOUT_TEXT")
      (libsource (lib "eagle-import") (part "M01PTH_WITHOUT_TEXT"))
    )
    (comp (ref "JP159")
      (value "M01PTH_WITHOUT_TEXT")
      (footprint "eagle-import:1X01_WITHOUT_TEXT")
      (libsource (lib "eagle-import") (part "M01PTH_WITHOUT_TEXT"))
    )
    (comp (ref "JP160")
      (value "M01PTH_WITHOUT_TEXT")
      (footprint "eagle-import:1X01_WITHOUT_TEXT")
      (libsource (lib "eagle-import") (part "M01PTH_WITHOUT_TEXT"))
    )
    (comp (ref "JP161")
      (value "M01PTH_WITHOUT_TEXT")
      (footprint "eagle-import:1X01_WITHOUT_TEXT")
      (libsource (lib "eagle-import") (part "M01PTH_WITHOUT_TEXT"))
    )
    (comp (ref "JP162")
      (value "M01PTH_WITHOUT_TEXT")
      (footprint "eagle-import:1X01_WITHOUT_TEXT")
      (libsource (lib "eagle-import") (part "M01PTH_WITHOUT_TEXT"))
    )
    (comp (ref "JP163")
      (value "M01PTH_WITHOUT_TEXT")
      (footprint "eagle-import:1X01_WITHOUT_TEXT")
      (libsource (lib "eagle-import") (part "M01PTH_WITHOUT_TEXT"))
    )
    (comp (ref "JP164")
      (value "M01PTH_WITHOUT_TEXT")
      (footprint "eagle-import:1X01_WITHOUT_TEXT")
      (libsource (lib "eagle-import") (part "M01PTH_WITHOUT_TEXT"))
    )
    (comp (ref "JP165")
      (value "M01PTH_WITHOUT_TEXT")
      (footprint "eagle-import:1X01_WITHOUT_TEXT")
      (libsource (lib "eagle-import") (part "M01PTH_WITHOUT_TEXT"))
    )
    (comp (ref "JP166")
      (value "M01PTH_WITHOUT_TEXT")
      (footprint "eagle-import:1X01_WITHOUT_TEXT")
      (libsource (lib "eagle-import") (part "M01PTH_WITHOUT_TEXT"))
    )
    (comp (ref "JP167")
      (value "M01PTH_WITHOUT_TEXT")
      (footprint "eagle-import:1X01_WITHOUT_TEXT")
      (libsource (lib "eagle-import") (part "M01PTH_WITHOUT_TEXT"))
    )
    (comp (ref "JP168")
      (value "M01PTH_WITHOUT_TEXT")
      (footprint "eagle-import:1X01_WITHOUT_TEXT")
      (libsource (lib "eagle-import") (part "M01PTH_WITHOUT_TEXT"))
    )
    (comp (ref "JP169")
      (value "M01PTH_WITHOUT_TEXT")
      (footprint "eagle-import:1X01_WITHOUT_TEXT")
      (libsource (lib "eagle-import") (part "M01PTH_WITHOUT_TEXT"))
    )
    (comp (ref "JP170")
      (value "M01PTH_WITHOUT_TEXT")
      (footprint "eagle-import:1X01_WITHOUT_TEXT")
      (libsource (lib "eagle-import") (part "M01PTH_WITHOUT_TEXT"))
    )
    (comp (ref "JP171")
      (value "M01PTH_WITHOUT_TEXT")
      (footprint "eagle-import:1X01_WITHOUT_TEXT")
      (libsource (lib "eagle-import") (part "M01PTH_WITHOUT_TEXT"))
    )
    (comp (ref "JP172")
      (value "M01PTH_WITHOUT_TEXT")
      (footprint "eagle-import:1X01_WITHOUT_TEXT")
      (libsource (lib "eagle-import") (part "M01PTH_WITHOUT_TEXT"))
    )
    (comp (ref "JP173")
      (value "M01PTH_WITHOUT_TEXT")
      (footprint "eagle-import:1X01_WITHOUT_TEXT")
      (libsource (lib "eagle-import") (part "M01PTH_WITHOUT_TEXT"))
    )
    (comp (ref "JP174")
      (value "M01PTH_WITHOUT_TEXT")
      (footprint "eagle-import:1X01_WITHOUT_TEXT")
      (libsource (lib "eagle-import") (part "M01PTH_WITHOUT_TEXT"))
    )
    (comp (ref "JP175")
      (value "M01PTH_WITHOUT_TEXT")
      (footprint "eagle-import:1X01_WITHOUT_TEXT")
      (libsource (lib "eagle-import") (part "M01PTH_WITHOUT_TEXT"))
    )
    (comp (ref "JP176")
      (value "M01PTH_WITHOUT_TEXT")
      (footprint "eagle-import:1X01_WITHOUT_TEXT")
      (libsource (lib "eagle-import") (part "M01PTH_WITHOUT_TEXT"))
    )
    (comp (ref "JP177")
      (value "M01PTH_WITHOUT_TEXT")
      (footprint "eagle-import:1X01_WITHOUT_TEXT")
      (libsource (lib "eagle-import") (part "M01PTH_WITHOUT_TEXT"))
    )
    (comp (ref "JP178")
      (value "M01PTH_WITHOUT_TEXT")
      (footprint "eagle-import:1X01_WITHOUT_TEXT")
      (libsource (lib "eagle-import") (part "M01PTH_WITHOUT_TEXT"))
    )
    (comp (ref "JP179")
      (value "M01PTH_WITHOUT_TEXT")
      (footprint "eagle-import:1X01_WITHOUT_TEXT")
      (libsource (lib "eagle-import") (part "M01PTH_WITHOUT_TEXT"))
    )
    (comp (ref "JP180")
      (value "M01PTH_WITHOUT_TEXT")
      (footprint "eagle-import:1X01_WITHOUT_TEXT")
      (libsource (lib "eagle-import") (part "M01PTH_WITHOUT_TEXT"))
    )
    (comp (ref "JP181")
      (value "M01PTH_WITHOUT_TEXT")
      (footprint "eagle-import:1X01_WITHOUT_TEXT")
      (libsource (lib "eagle-import") (part "M01PTH_WITHOUT_TEXT"))
    )
    (comp (ref "JP182")
      (value "M01PTH_WITHOUT_TEXT")
      (footprint "eagle-import:1X01_WITHOUT_TEXT")
      (libsource (lib "eagle-import") (part "M01PTH_WITHOUT_TEXT"))
    )
    (comp (ref "JP183")
      (value "M01PTH_WITHOUT_TEXT")
      (footprint "eagle-import:1X01_WITHOUT_TEXT")
      (libsource (lib "eagle-import") (part "M01PTH_WITHOUT_TEXT"))
    )
    (comp (ref "JP184")
      (value "M01PTH_WITHOUT_TEXT")
      (footprint "eagle-import:1X01_WITHOUT_TEXT")
      (libsource (lib "eagle-import") (part "M01PTH_WITHOUT_TEXT"))
    )
    (comp (ref "JP185")
      (value "M01PTH_WITHOUT_TEXT")
      (footprint "eagle-import:1X01_WITHOUT_TEXT")
      (libsource (lib "eagle-import") (part "M01PTH_WITHOUT_TEXT"))
    )
    (comp (ref "JP186")
      (value "M01PTH_WITHOUT_TEXT")
      (footprint "eagle-import:1X01_WITHOUT_TEXT")
      (libsource (lib "eagle-import") (part "M01PTH_WITHOUT_TEXT"))
    )
    (comp (ref "JP187")
      (value "M01PTH_WITHOUT_TEXT")
      (footprint "eagle-import:1X01_WITHOUT_TEXT")
      (libsource (lib "eagle-import") (part "M01PTH_WITHOUT_TEXT"))
    )
    (comp (ref "JP188")
      (value "M01PTH_WITHOUT_TEXT")
      (footprint "eagle-import:1X01_WITHOUT_TEXT")
      (libsource (lib "eagle-import") (part "M01PTH_WITHOUT_TEXT"))
    )
    (comp (ref "JP189")
      (value "M01PTH_WITHOUT_TEXT")
      (footprint "eagle-import:1X01_WITHOUT_TEXT")
      (libsource (lib "eagle-import") (part "M01PTH_WITHOUT_TEXT"))
    )
    (comp (ref "JP190")
      (value "M01PTH_WITHOUT_TEXT")
      (footprint "eagle-import:1X01_WITHOUT_TEXT")
      (libsource (lib "eagle-import") (part "M01PTH_WITHOUT_TEXT"))
    )
    (comp (ref "JP191")
      (value "M01PTH_WITHOUT_TEXT")
      (footprint "eagle-import:1X01_WITHOUT_TEXT")
      (libsource (lib "eagle-import") (part "M01PTH_WITHOUT_TEXT"))
    )
    (comp (ref "JP192")
      (value "M01PTH_WITHOUT_TEXT")
      (footprint "eagle-import:1X01_WITHOUT_TEXT")
      (libsource (lib "eagle-import") (part "M01PTH_WITHOUT_TEXT"))
    )
    (comp (ref "JP193")
      (value "M01PTH_WITHOUT_TEXT")
      (footprint "eagle-import:1X01_WITHOUT_TEXT")
      (libsource (lib "eagle-import") (part "M01PTH_WITHOUT_TEXT"))
    )
    (comp (ref "JP194")
      (value "M01PTH_WITHOUT_TEXT")
      (footprint "eagle-import:1X01_WITHOUT_TEXT")
      (libsource (lib "eagle-import") (part "M01PTH_WITHOUT_TEXT"))
    )
    (comp (ref "JP195")
      (value "M01PTH_WITHOUT_TEXT")
      (footprint "eagle-import:1X01_WITHOUT_TEXT")
      (libsource (lib "eagle-import") (part "M01PTH_WITHOUT_TEXT"))
    )
    (comp (ref "JP196")
      (value "M01PTH_WITHOUT_TEXT")
      (footprint "eagle-import:1X01_WITHOUT_TEXT")
      (libsource (lib "eagle-import") (part "M01PTH_WITHOUT_TEXT"))
    )
    (comp (ref "JP197")
      (value "M01PTH_WITHOUT_TEXT")
      (footprint "eagle-import:1X01_WITHOUT_TEXT")
      (libsource (lib "eagle-import") (part "M01PTH_WITHOUT_TEXT"))
    )
    (comp (ref "JP198")
      (value "M01PTH_WITHOUT_TEXT")
      (footprint "eagle-import:1X01_WITHOUT_TEXT")
      (libsource (lib "eagle-import") (part "M01PTH_WITHOUT_TEXT"))
    )
    (comp (ref "JP199")
      (value "M01PTH_WITHOUT_TEXT")
      (footprint "eagle-import:1X01_WITHOUT_TEXT")
      (libsource (lib "eagle-import") (part "M01PTH_WITHOUT_TEXT"))
    )
    (comp (ref "JP200")
      (value "M01PTH_WITHOUT_TEXT")
      (footprint "eagle-import:1X01_WITHOUT_TEXT")
      (libsource (lib "eagle-import") (part "M01PTH_WITHOUT_TEXT"))
    )
    (comp (ref "JP201")
      (value "M01PTH_WITHOUT_TEXT")
      (footprint "eagle-import:1X01_WITHOUT_TEXT")
      (libsource (lib "eagle-import") (part "M01PTH_WITHOUT_TEXT"))
    )
    (comp (ref "JP202")
      (value "M01PTH_WITHOUT_TEXT")
      (footprint "eagle-import:1X01_WITHOUT_TEXT")
      (libsource (lib "eagle-import") (part "M01PTH_WITHOUT_TEXT"))
    )
    (comp (ref "JP203")
      (value "M01PTH_WITHOUT_TEXT")
      (footprint "eagle-import:1X01_WITHOUT_TEXT")
      (libsource (lib "eagle-import") (part "M01PTH_WITHOUT_TEXT"))
    )
    (comp (ref "JP204")
      (value "M01PTH_WITHOUT_TEXT")
      (footprint "eagle-import:1X01_WITHOUT_TEXT")
      (libsource (lib "eagle-import") (part "M01PTH_WITHOUT_TEXT"))
    )
    (comp (ref "JP205")
      (value "M01PTH_WITHOUT_TEXT")
      (footprint "eagle-import:1X01_WITHOUT_TEXT")
      (libsource (lib "eagle-import") (part "M01PTH_WITHOUT_TEXT"))
    )
    (comp (ref "JP206")
      (value "M01PTH_WITHOUT_TEXT")
      (footprint "eagle-import:1X01_WITHOUT_TEXT")
      (libsource (lib "eagle-import") (part "M01PTH_WITHOUT_TEXT"))
    )
    (comp (ref "JP207")
      (value "M01PTH_WITHOUT_TEXT")
      (footprint "eagle-import:1X01_WITHOUT_TEXT")
      (libsource (lib "eagle-import") (part "M01PTH_WITHOUT_TEXT"))
    )
    (comp (ref "JP208")
      (value "M01PTH_WITHOUT_TEXT")
      (footprint "eagle-import:1X01_WITHOUT_TEXT")
      (libsource (lib "eagle-import") (part "M01PTH_WITHOUT_TEXT"))
    )
    (comp (ref "JP209")
      (value "M01PTH_WITHOUT_TEXT")
      (footprint "eagle-import:1X01_WITHOUT_TEXT")
      (libsource (lib "eagle-import") (part "M01PTH_WITHOUT_TEXT"))
    )
    (comp (ref "JP210")
      (value "M01PTH_WITHOUT_TEXT")
      (footprint "eagle-import:1X01_WITHOUT_TEXT")
      (libsource (lib "eagle-import") (part "M01PTH_WITHOUT_TEXT"))
    )
    (comp (ref "JP211")
      (value "M01PTH_WITHOUT_TEXT")
      (footprint "eagle-import:1X01_WITHOUT_TEXT")
      (libsource (lib "eagle-import") (part "M01PTH_WITHOUT_TEXT"))
    )
    (comp (ref "JP212")
      (value "M01PTH_WITHOUT_TEXT")
      (footprint "eagle-import:1X01_WITHOUT_TEXT")
      (libsource (lib "eagle-import") (part "M01PTH_WITHOUT_TEXT"))
    )
    (comp (ref "JP213")
      (value "M01PTH_WITHOUT_TEXT")
      (footprint "eagle-import:1X01_WITHOUT_TEXT")
      (libsource (lib "eagle-import") (part "M01PTH_WITHOUT_TEXT"))
    )
    (comp (ref "JP214")
      (value "M01PTH_WITHOUT_TEXT")
      (footprint "eagle-import:1X01_WITHOUT_TEXT")
      (libsource (lib "eagle-import") (part "M01PTH_WITHOUT_TEXT"))
    )
    (comp (ref "JP215")
      (value "M01PTH_WITHOUT_TEXT")
      (footprint "eagle-import:1X01_WITHOUT_TEXT")
      (libsource (lib "eagle-import") (part "M01PTH_WITHOUT_TEXT"))
    )
    (comp (ref "JP216")
      (value "M01PTH_WITHOUT_TEXT")
      (footprint "eagle-import:1X01_WITHOUT_TEXT")
      (libsource (lib "eagle-import") (part "M01PTH_WITHOUT_TEXT"))
    )
    (comp (ref "JP217")
      (value "M01PTH_WITHOUT_TEXT")
      (footprint "eagle-import:1X01_WITHOUT_TEXT")
      (libsource (lib "eagle-import") (part "M01PTH_WITHOUT_TEXT"))
    )
    (comp (ref "JP218")
      (value "M01PTH_WITHOUT_TEXT")
      (footprint "eagle-import:1X01_WITHOUT_TEXT")
      (libsource (lib "eagle-import") (part "M01PTH_WITHOUT_TEXT"))
    )
    (comp (ref "JP219")
      (value "M01PTH_WITHOUT_TEXT")
      (footprint "eagle-import:1X01_WITHOUT_TEXT")
      (libsource (lib "eagle-import") (part "M01PTH_WITHOUT_TEXT"))
    )
    (comp (ref "JP220")
      (value "M01PTH_WITHOUT_TEXT")
      (footprint "eagle-import:1X01_WITHOUT_TEXT")
      (libsource (lib "eagle-import") (part "M01PTH_WITHOUT_TEXT"))
    )
    (comp (ref "JP221")
      (value "M01PTH_WITHOUT_TEXT")
      (footprint "eagle-import:1X01_WITHOUT_TEXT")
      (libsource (lib "eagle-import") (part "M01PTH_WITHOUT_TEXT"))
    )
    (comp (ref "JP222")
      (value "M01PTH_WITHOUT_TEXT")
      (footprint "eagle-import:1X01_WITHOUT_TEXT")
      (libsource (lib "eagle-import") (part "M01PTH_WITHOUT_TEXT"))
    )
    (comp (ref "JP223")
      (value "M01PTH_WITHOUT_TEXT")
      (footprint "eagle-import:1X01_WITHOUT_TEXT")
      (libsource (lib "eagle-import") (part "M01PTH_WITHOUT_TEXT"))
    )
    (comp (ref "JP224")
      (value "M01PTH_WITHOUT_TEXT")
      (footprint "eagle-import:1X01_WITHOUT_TEXT")
      (libsource (lib "eagle-import") (part "M01PTH_WITHOUT_TEXT"))
    )
    (comp (ref "JP225")
      (value "M01PTH_WITHOUT_TEXT")
      (footprint "eagle-import:1X01_WITHOUT_TEXT")
      (libsource (lib "eagle-import") (part "M01PTH_WITHOUT_TEXT"))
    )
    (comp (ref "JP226")
      (value "M01PTH_WITHOUT_TEXT")
      (footprint "eagle-import:1X01_WITHOUT_TEXT")
      (libsource (lib "eagle-import") (part "M01PTH_WITHOUT_TEXT"))
    )
    (comp (ref "JP227")
      (value "M01PTH_WITHOUT_TEXT")
      (footprint "eagle-import:1X01_WITHOUT_TEXT")
      (libsource (lib "eagle-import") (part "M01PTH_WITHOUT_TEXT"))
    )
    (comp (ref "JP228")
      (value "M01PTH_WITHOUT_TEXT")
      (footprint "eagle-import:1X01_WITHOUT_TEXT")
      (libsource (lib "eagle-import") (part "M01PTH_WITHOUT_TEXT"))
    )
    (comp (ref "JP229")
      (value "M01PTH_WITHOUT_TEXT")
      (footprint "eagle-import:1X01_WITHOUT_TEXT")
      (libsource (lib "eagle-import") (part "M01PTH_WITHOUT_TEXT"))
    )
    (comp (ref "JP230")
      (value "M01PTH_WITHOUT_TEXT")
      (footprint "eagle-import:1X01_WITHOUT_TEXT")
      (libsource (lib "eagle-import") (part "M01PTH_WITHOUT_TEXT"))
    )
    (comp (ref "JP231")
      (value "M01PTH_WITHOUT_TEXT")
      (footprint "eagle-import:1X01_WITHOUT_TEXT")
      (libsource (lib "eagle-import") (part "M01PTH_WITHOUT_TEXT"))
    )
    (comp (ref "JP232")
      (value "M01PTH_WITHOUT_TEXT")
      (footprint "eagle-import:1X01_WITHOUT_TEXT")
      (libsource (lib "eagle-import") (part "M01PTH_WITHOUT_TEXT"))
    )
    (comp (ref "JP233")
      (value "M01PTH_WITHOUT_TEXT")
      (footprint "eagle-import:1X01_WITHOUT_TEXT")
      (libsource (lib "eagle-import") (part "M01PTH_WITHOUT_TEXT"))
    )
    (comp (ref "JP234")
      (value "M01PTH_WITHOUT_TEXT")
      (footprint "eagle-import:1X01_WITHOUT_TEXT")
      (libsource (lib "eagle-import") (part "M01PTH_WITHOUT_TEXT"))
    )
    (comp (ref "JP235")
      (value "M01PTH_WITHOUT_TEXT")
      (footprint "eagle-import:1X01_WITHOUT_TEXT")
      (libsource (lib "eagle-import") (part "M01PTH_WITHOUT_TEXT"))
    )
    (comp (ref "JP236")
      (value "M01PTH_WITHOUT_TEXT")
      (footprint "eagle-import:1X01_WITHOUT_TEXT")
      (libsource (lib "eagle-import") (part "M01PTH_WITHOUT_TEXT"))
    )
    (comp (ref "JP237")
      (value "M01PTH_WITHOUT_TEXT")
      (footprint "eagle-import:1X01_WITHOUT_TEXT")
      (libsource (lib "eagle-import") (part "M01PTH_WITHOUT_TEXT"))
    )
    (comp (ref "JP238")
      (value "M01PTH_WITHOUT_TEXT")
      (footprint "eagle-import:1X01_WITHOUT_TEXT")
      (libsource (lib "eagle-import") (part "M01PTH_WITHOUT_TEXT"))
    )
    (comp (ref "JP239")
      (value "M01PTH_WITHOUT_TEXT")
      (footprint "eagle-import:1X01_WITHOUT_TEXT")
      (libsource (lib "eagle-import") (part "M01PTH_WITHOUT_TEXT"))
    )
    (comp (ref "JP240")
      (value "M01PTH_WITHOUT_TEXT")
      (footprint "eagle-import:1X01_WITHOUT_TEXT")
      (libsource (lib "eagle-import") (part "M01PTH_WITHOUT_TEXT"))
    )
    (comp (ref "JP241")
      (value "M01PTH_WITHOUT_TEXT")
      (footprint "eagle-import:1X01_WITHOUT_TEXT")
      (libsource (lib "eagle-import") (part "M01PTH_WITHOUT_TEXT"))
    )
    (comp (ref "JP242")
      (value "M01PTH_WITHOUT_TEXT")
      (footprint "eagle-import:1X01_WITHOUT_TEXT")
      (libsource (lib "eagle-import") (part "M01PTH_WITHOUT_TEXT"))
    )
    (comp (ref "JP243")
      (value "M01PTH_WITHOUT_TEXT")
      (footprint "eagle-import:1X01_WITHOUT_TEXT")
      (libsource (lib "eagle-import") (part "M01PTH_WITHOUT_TEXT"))
    )
    (comp (ref "JP244")
      (value "M01PTH_WITHOUT_TEXT")
      (footprint "eagle-import:1X01_WITHOUT_TEXT")
      (libsource (lib "eagle-import") (part "M01PTH_WITHOUT_TEXT"))
    )
    (comp (ref "JP245")
      (value "M01PTH_WITHOUT_TEXT")
      (footprint "eagle-import:1X01_WITHOUT_TEXT")
      (libsource (lib "eagle-import") (part "M01PTH_WITHOUT_TEXT"))
    )
    (comp (ref "JP246")
      (value "M01PTH_WITHOUT_TEXT")
      (footprint "eagle-import:1X01_WITHOUT_TEXT")
      (libsource (lib "eagle-import") (part "M01PTH_WITHOUT_TEXT"))
    )
    (comp (ref "JP247")
      (value "M01PTH_WITHOUT_TEXT")
      (footprint "eagle-import:1X01_WITHOUT_TEXT")
      (libsource (lib "eagle-import") (part "M01PTH_WITHOUT_TEXT"))
    )
    (comp (ref "JP248")
      (value "M01PTH_WITHOUT_TEXT")
      (footprint "eagle-import:1X01_WITHOUT_TEXT")
      (libsource (lib "eagle-import") (part "M01PTH_WITHOUT_TEXT"))
    )
    (comp (ref "JP249")
      (value "M01PTH_WITHOUT_TEXT")
      (footprint "eagle-import:1X01_WITHOUT_TEXT")
      (libsource (lib "eagle-import") (part "M01PTH_WITHOUT_TEXT"))
    )
    (comp (ref "JP250")
      (value "M01PTH_WITHOUT_TEXT")
      (footprint "eagle-import:1X01_WITHOUT_TEXT")
      (libsource (lib "eagle-import") (part "M01PTH_WITHOUT_TEXT"))
    )
    (comp (ref "JP251")
      (value "M01PTH_WITHOUT_TEXT")
      (footprint "eagle-import:1X01_WITHOUT_TEXT")
      (libsource (lib "eagle-import") (part "M01PTH_WITHOUT_TEXT"))
    )
    (comp (ref "JP252")
      (value "M01PTH_WITHOUT_TEXT")
      (footprint "eagle-import:1X01_WITHOUT_TEXT")
      (libsource (lib "eagle-import") (part "M01PTH_WITHOUT_TEXT"))
    )
    (comp (ref "JP253")
      (value "M01PTH_WITHOUT_TEXT")
      (footprint "eagle-import:1X01_WITHOUT_TEXT")
      (libsource (lib "eagle-import") (part "M01PTH_WITHOUT_TEXT"))
    )
    (comp (ref "JP254")
      (value "M01PTH_WITHOUT_TEXT")
      (footprint "eagle-import:1X01_WITHOUT_TEXT")
      (libsource (lib "eagle-import") (part "M01PTH_WITHOUT_TEXT"))
    )
    (comp (ref "JP255")
      (value "M01PTH_WITHOUT_TEXT")
      (footprint "eagle-import:1X01_WITHOUT_TEXT")
      (libsource (lib "eagle-import") (part "M01PTH_WITHOUT_TEXT"))
    )
    (comp (ref "JP256")
      (value "M01PTH_WITHOUT_TEXT")
      (footprint "eagle-import:1X01_WITHOUT_TEXT")
      (libsource (lib "eagle-import") (part "M01PTH_WITHOUT_TEXT"))
    )
    (comp (ref "JP257")
      (value "M01PTH_WITHOUT_TEXT")
      (footprint "eagle-import:1X01_WITHOUT_TEXT")
      (libsource (lib "eagle-import") (part "M01PTH_WITHOUT_TEXT"))
    )
    (comp (ref "JP258")
      (value "M01PTH_WITHOUT_TEXT")
      (footprint "eagle-import:1X01_WITHOUT_TEXT")
      (libsource (lib "eagle-import") (part "M01PTH_WITHOUT_TEXT"))
    )
    (comp (ref "JP259")
      (value "M01PTH_WITHOUT_TEXT")
      (footprint "eagle-import:1X01_WITHOUT_TEXT")
      (libsource (lib "eagle-import") (part "M01PTH_WITHOUT_TEXT"))
    )
    (comp (ref "JP260")
      (value "M01PTH_WITHOUT_TEXT")
      (footprint "eagle-import:1X01_WITHOUT_TEXT")
      (libsource (lib "eagle-import") (part "M01PTH_WITHOUT_TEXT"))
    )
    (comp (ref "JP261")
      (value "M01PTH_WITHOUT_TEXT")
      (footprint "eagle-import:1X01_WITHOUT_TEXT")
      (libsource (lib "eagle-import") (part "M01PTH_WITHOUT_TEXT"))
    )
    (comp (ref "JP262")
      (value "M01PTH_WITHOUT_TEXT")
      (footprint "eagle-import:1X01_WITHOUT_TEXT")
      (libsource (lib "eagle-import") (part "M01PTH_WITHOUT_TEXT"))
    )
    (comp (ref "JP263")
      (value "M01PTH_WITHOUT_TEXT")
      (footprint "eagle-import:1X01_WITHOUT_TEXT")
      (libsource (lib "eagle-import") (part "M01PTH_WITHOUT_TEXT"))
    )
    (comp (ref "JP264")
      (value "M01PTH_WITHOUT_TEXT")
      (footprint "eagle-import:1X01_WITHOUT_TEXT")
      (libsource (lib "eagle-import") (part "M01PTH_WITHOUT_TEXT"))
    )
    (comp (ref "JP265")
      (value "M01PTH_WITHOUT_TEXT")
      (footprint "eagle-import:1X01_WITHOUT_TEXT")
      (libsource (lib "eagle-import") (part "M01PTH_WITHOUT_TEXT"))
    )
    (comp (ref "JP266")
      (value "M01PTH_WITHOUT_TEXT")
      (footprint "eagle-import:1X01_WITHOUT_TEXT")
      (libsource (lib "eagle-import") (part "M01PTH_WITHOUT_TEXT"))
    )
    (comp (ref "JP267")
      (value "M01PTH_WITHOUT_TEXT")
      (footprint "eagle-import:1X01_WITHOUT_TEXT")
      (libsource (lib "eagle-import") (part "M01PTH_WITHOUT_TEXT"))
    )
    (comp (ref "JP268")
      (value "M01PTH_WITHOUT_TEXT")
      (footprint "eagle-import:1X01_WITHOUT_TEXT")
      (libsource (lib "eagle-import") (part "M01PTH_WITHOUT_TEXT"))
    )
    (comp (ref "JP269")
      (value "M01PTH_WITHOUT_TEXT")
      (footprint "eagle-import:1X01_WITHOUT_TEXT")
      (libsource (lib "eagle-import") (part "M01PTH_WITHOUT_TEXT"))
    )
    (comp (ref "JP270")
      (value "M01PTH_WITHOUT_TEXT")
      (footprint "eagle-import:1X01_WITHOUT_TEXT")
      (libsource (lib "eagle-import") (part "M01PTH_WITHOUT_TEXT"))
    )
    (comp (ref "JP271")
      (value "M01PTH_WITHOUT_TEXT")
      (footprint "eagle-import:1X01_WITHOUT_TEXT")
      (libsource (lib "eagle-import") (part "M01PTH_WITHOUT_TEXT"))
    )
    (comp (ref "JP272")
      (value "M01PTH_WITHOUT_TEXT")
      (footprint "eagle-import:1X01_WITHOUT_TEXT")
      (libsource (lib "eagle-import") (part "M01PTH_WITHOUT_TEXT"))
    )
    (comp (ref "JP273")
      (value "M01PTH_WITHOUT_TEXT")
      (footprint "eagle-import:1X01_WITHOUT_TEXT")
      (libsource (lib "eagle-import") (part "M01PTH_WITHOUT_TEXT"))
    )
    (comp (ref "JP274")
      (value "M01PTH_WITHOUT_TEXT")
      (footprint "eagle-import:1X01_WITHOUT_TEXT")
      (libsource (lib "eagle-import") (part "M01PTH_WITHOUT_TEXT"))
    )
    (comp (ref "JP275")
      (value "M01PTH_WITHOUT_TEXT")
      (footprint "eagle-import:1X01_WITHOUT_TEXT")
      (libsource (lib "eagle-import") (part "M01PTH_WITHOUT_TEXT"))
    )
    (comp (ref "JP276")
      (value "M01PTH_WITHOUT_TEXT")
      (footprint "eagle-import:1X01_WITHOUT_TEXT")
      (libsource (lib "eagle-import") (part "M01PTH_WITHOUT_TEXT"))
    )
    (comp (ref "JP277")
      (value "M01PTH_WITHOUT_TEXT")
      (footprint "eagle-import:1X01_WITHOUT_TEXT")
      (libsource (lib "eagle-import") (part "M01PTH_WITHOUT_TEXT"))
    )
    (comp (ref "JP278")
      (value "M01PTH_WITHOUT_TEXT")
      (footprint "eagle-import:1X01_WITHOUT_TEXT")
      (libsource (lib "eagle-import") (part "M01PTH_WITHOUT_TEXT"))
    )
    (comp (ref "JP279")
      (value "M01PTH_WITHOUT_TEXT")
      (footprint "eagle-import:1X01_WITHOUT_TEXT")
      (libsource (lib "eagle-import") (part "M01PTH_WITHOUT_TEXT"))
    )
    (comp (ref "JP280")
      (value "M01PTH_WITHOUT_TEXT")
      (footprint "eagle-import:1X01_WITHOUT_TEXT")
      (libsource (lib "eagle-import") (part "M01PTH_WITHOUT_TEXT"))
    )
    (comp (ref "JP281")
      (value "M01PTH_WITHOUT_TEXT")
      (footprint "eagle-import:1X01_WITHOUT_TEXT")
      (libsource (lib "eagle-import") (part "M01PTH_WITHOUT_TEXT"))
    )
    (comp (ref "JP282")
      (value "M01PTH_WITHOUT_TEXT")
      (footprint "eagle-import:1X01_WITHOUT_TEXT")
      (libsource (lib "eagle-import") (part "M01PTH_WITHOUT_TEXT"))
    )
    (comp (ref "JP283")
      (value "M01PTH_WITHOUT_TEXT")
      (footprint "eagle-import:1X01_WITHOUT_TEXT")
      (libsource (lib "eagle-import") (part "M01PTH_WITHOUT_TEXT"))
    )
    (comp (ref "JP284")
      (value "M01PTH_WITHOUT_TEXT")
      (footprint "eagle-import:1X01_WITHOUT_TEXT")
      (libsource (lib "eagle-import") (part "M01PTH_WITHOUT_TEXT"))
    )
    (comp (ref "JP285")
      (value "M01PTH_WITHOUT_TEXT")
      (footprint "eagle-import:1X01_WITHOUT_TEXT")
      (libsource (lib "eagle-import") (part "M01PTH_WITHOUT_TEXT"))
    )
    (comp (ref "JP286")
      (value "M01PTH_WITHOUT_TEXT")
      (footprint "eagle-import:1X01_WITHOUT_TEXT")
      (libsource (lib "eagle-import") (part "M01PTH_WITHOUT_TEXT"))
    )
    (comp (ref "JP287")
      (value "M01PTH_WITHOUT_TEXT")
      (footprint "eagle-import:1X01_WITHOUT_TEXT")
      (libsource (lib "eagle-import") (part "M01PTH_WITHOUT_TEXT"))
    )
    (comp (ref "JP288")
      (value "M01PTH_WITHOUT_TEXT")
      (footprint "eagle-import:1X01_WITHOUT_TEXT")
      (libsource (lib "eagle-import") (part "M01PTH_WITHOUT_TEXT"))
    )
    (comp (ref "JP289")
      (value "M01PTH_WITHOUT_TEXT")
      (footprint "eagle-import:1X01_WITHOUT_TEXT")
      (libsource (lib "eagle-import") (part "M01PTH_WITHOUT_TEXT"))
    )
    (comp (ref "JP290")
      (value "M01PTH_WITHOUT_TEXT")
      (footprint "eagle-import:1X01_WITHOUT_TEXT")
      (libsource (lib "eagle-import") (part "M01PTH_WITHOUT_TEXT"))
    )
    (comp (ref "JP291")
      (value "M01PTH_WITHOUT_TEXT")
      (footprint "eagle-import:1X01_WITHOUT_TEXT")
      (libsource (lib "eagle-import") (part "M01PTH_WITHOUT_TEXT"))
    )
    (comp (ref "JP292")
      (value "M01PTH_WITHOUT_TEXT")
      (footprint "eagle-import:1X01_WITHOUT_TEXT")
      (libsource (lib "eagle-import") (part "M01PTH_WITHOUT_TEXT"))
    )
    (comp (ref "JP293")
      (value "M01PTH_WITHOUT_TEXT")
      (footprint "eagle-import:1X01_WITHOUT_TEXT")
      (libsource (lib "eagle-import") (part "M01PTH_WITHOUT_TEXT"))
    )
    (comp (ref "JP294")
      (value "M01PTH_WITHOUT_TEXT")
      (footprint "eagle-import:1X01_WITHOUT_TEXT")
      (libsource (lib "eagle-import") (part "M01PTH_WITHOUT_TEXT"))
    )
    (comp (ref "JP295")
      (value "M01PTH_WITHOUT_TEXT")
      (footprint "eagle-import:1X01_WITHOUT_TEXT")
      (libsource (lib "eagle-import") (part "M01PTH_WITHOUT_TEXT"))
    )
    (comp (ref "JP296")
      (value "M01PTH_WITHOUT_TEXT")
      (footprint "eagle-import:1X01_WITHOUT_TEXT")
      (libsource (lib "eagle-import") (part "M01PTH_WITHOUT_TEXT"))
    )
    (comp (ref "JP297")
      (value "M01PTH_WITHOUT_TEXT")
      (footprint "eagle-import:1X01_WITHOUT_TEXT")
      (libsource (lib "eagle-import") (part "M01PTH_WITHOUT_TEXT"))
    )
    (comp (ref "JP298")
      (value "M01PTH_WITHOUT_TEXT")
      (footprint "eagle-import:1X01_WITHOUT_TEXT")
      (libsource (lib "eagle-import") (part "M01PTH_WITHOUT_TEXT"))
    )
    (comp (ref "JP299")
      (value "M01PTH_WITHOUT_TEXT")
      (footprint "eagle-import:1X01_WITHOUT_TEXT")
      (libsource (lib "eagle-import") (part "M01PTH_WITHOUT_TEXT"))
    )
    (comp (ref "JP300")
      (value "M01PTH_WITHOUT_TEXT")
      (footprint "eagle-import:1X01_WITHOUT_TEXT")
      (libsource (lib "eagle-import") (part "M01PTH_WITHOUT_TEXT"))
    )
    (comp (ref "JP901")
      (value "M01PTH_SMD_3.25X0.85MM_NO_SILK")
      (footprint "eagle-import:1X01_SMD_3.25X0.85MM_NO_SILK")
      (libsource (lib "eagle-import") (part "M01PTH_SMD_3.25X0.85MM_NO_SILK"))
    )
    (comp (ref "JP902")
      (value "M01PTH_SMD_3.25X0.85MM_NO_SILK")
      (footprint "eagle-import:1X01_SMD_3.25X0.85MM_NO_SILK")
      (libsource (lib "eagle-import") (part "M01PTH_SMD_3.25X0.85MM_NO_SILK"))
    )
    (comp (ref "JP903")
      (value "M01PTH_SMD_3.25X0.85MM_NO_SILK")
      (footprint "eagle-import:1X01_SMD_3.25X0.85MM_NO_SILK")
      (libsource (lib "eagle-import") (part "M01PTH_SMD_3.25X0.85MM_NO_SILK"))
    )
    (comp (ref "JP904")
      (value "M01PTH_SMD_3.25X0.85MM_NO_SILK")
      (footprint "eagle-import:1X01_SMD_3.25X0.85MM_NO_SILK")
      (libsource (lib "eagle-import") (part "M01PTH_SMD_3.25X0.85MM_NO_SILK"))
    )
    (comp (ref "JP905")
      (value "M01PTH_SMD_3.25X0.85MM_NO_SILK")
      (footprint "eagle-import:1X01_SMD_3.25X0.85MM_NO_SILK")
      (libsource (lib "eagle-import") (part "M01PTH_SMD_3.25X0.85MM_NO_SILK"))
    )
    (comp (ref "JP906")
      (value "M01PTH_SMD_3.25X0.85MM_NO_SILK")
      (footprint "eagle-import:1X01_SMD_3.25X0.85MM_NO_SILK")
      (libsource (lib "eagle-import") (part "M01PTH_SMD_3.25X0.85MM_NO_SILK"))
    )
    (comp (ref "JP907")
      (value "M01PTH_SMD_3.25X0.85MM_NO_SILK")
      (footprint "eagle-import:1X01_SMD_3.25X0.85MM_NO_SILK")
      (libsource (lib "eagle-import") (part "M01PTH_SMD_3.25X0.85MM_NO_SILK"))
    )
    (comp (ref "JP908")
      (value "M01PTH_SMD_3.25X0.85MM_NO_SILK")
      (footprint "eagle-import:1X01_SMD_3.25X0.85MM_NO_SILK")
      (libsource (lib "eagle-import") (part "M01PTH_SMD_3.25X0.85MM_NO_SILK"))
    )
    (comp (ref "JP909")
      (value "M01PTH_SMD_3.25X0.85MM_NO_SILK")
      (footprint "eagle-import:1X01_SMD_3.25X0.85MM_NO_SILK")
      (libsource (lib "eagle-import") (part "M01PTH_SMD_3.25X0.85MM_NO_SILK"))
    )
    (comp (ref "JP910")
      (value "M01PTH_SMD_3.25X0.85MM_NO_SILK")
      (footprint "eagle-import:1X01_SMD_3.25X0.85MM_NO_SILK")
      (libsource (lib "eagle-import") (part "M01PTH_SMD_3.25X0.85MM_NO_SILK"))
    )
    (comp (ref "JP911")
      (value "M01PTH_SMD_3.25X0.85MM_NO_SILK")
      (footprint "eagle-import:1X01_SMD_3.25X0.85MM_NO_SILK")
      (libsource (lib "eagle-import") (part "M01PTH_SMD_3.25X0.85MM_NO_SILK"))
    )
    (comp (ref "JP912")
      (value "M01PTH_SMD_3.25X0.85MM_NO_SILK")
      (footprint "eagle-import:1X01_SMD_3.25X0.85MM_NO_SILK")
      (libsource (lib "eagle-import") (part "M01PTH_SMD_3.25X0.85MM_NO_SILK"))
    )
    (comp (ref "JP913")
      (value "M01PTH_SMD_3.25X0.85MM_NO_SILK")
      (footprint "eagle-import:1X01_SMD_3.25X0.85MM_NO_SILK")
      (libsource (lib "eagle-import") (part "M01PTH_SMD_3.25X0.85MM_NO_SILK"))
    )
    (comp (ref "JP914")
      (value "M01PTH_SMD_3.25X0.85MM_NO_SILK")
      (footprint "eagle-import:1X01_SMD_3.25X0.85MM_NO_SILK")
      (libsource (lib "eagle-import") (part "M01PTH_SMD_3.25X0.85MM_NO_SILK"))
    )
    (comp (ref "JP915")
      (value "M01PTH_SMD_3.25X0.85MM_NO_SILK")
      (footprint "eagle-import:1X01_SMD_3.25X0.85MM_NO_SILK")
      (libsource (lib "eagle-import") (part "M01PTH_SMD_3.25X0.85MM_NO_SILK"))
    )
    (comp (ref "JP916")
      (value "M01PTH_SMD_3.25X0.85MM_NO_SILK")
      (footprint "eagle-import:1X01_SMD_3.25X0.85MM_NO_SILK")
      (libsource (lib "eagle-import") (part "M01PTH_SMD_3.25X0.85MM_NO_SILK"))
    )
    (comp (ref "JP917")
      (value "M01PTH_SMD_3.25X0.85MM_NO_SILK")
      (footprint "eagle-import:1X01_SMD_3.25X0.85MM_NO_SILK")
      (libsource (lib "eagle-import") (part "M01PTH_SMD_3.25X0.85MM_NO_SILK"))
    )
    (comp (ref "JP918")
      (value "M01PTH_SMD_3.25X0.85MM_NO_SILK")
      (footprint "eagle-import:1X01_SMD_3.25X0.85MM_NO_SILK")
      (libsource (lib "eagle-import") (part "M01PTH_SMD_3.25X0.85MM_NO_SILK"))
    )
    (comp (ref "JP919")
      (value "M01PTH_SMD_3.25X0.85MM_NO_SILK")
      (footprint "eagle-import:1X01_SMD_3.25X0.85MM_NO_SILK")
      (libsource (lib "eagle-import") (part "M01PTH_SMD_3.25X0.85MM_NO_SILK"))
    )
    (comp (ref "JP920")
      (value "M01PTH_SMD_3.25X0.85MM_NO_SILK")
      (footprint "eagle-import:1X01_SMD_3.25X0.85MM_NO_SILK")
      (libsource (lib "eagle-import") (part "M01PTH_SMD_3.25X0.85MM_NO_SILK"))
    )
    (comp (ref "JP921")
      (value "M01PTH_SMD_3.25X0.85MM_NO_SILK")
      (footprint "eagle-import:1X01_SMD_3.25X0.85MM_NO_SILK")
      (libsource (lib "eagle-import") (part "M01PTH_SMD_3.25X0.85MM_NO_SILK"))
    )
    (comp (ref "JP922")
      (value "M01PTH_SMD_3.25X0.85MM_NO_SILK")
      (footprint "eagle-import:1X01_SMD_3.25X0.85MM_NO_SILK")
      (libsource (lib "eagle-import") (part "M01PTH_SMD_3.25X0.85MM_NO_SILK"))
    )
    (comp (ref "JP923")
      (value "M01PTH_SMD_3.25X0.85MM_NO_SILK")
      (footprint "eagle-import:1X01_SMD_3.25X0.85MM_NO_SILK")
      (libsource (lib "eagle-import") (part "M01PTH_SMD_3.25X0.85MM_NO_SILK"))
    )
    (comp (ref "JP924")
      (value "M01PTH_SMD_3.25X0.85MM_NO_SILK")
      (footprint "eagle-import:1X01_SMD_3.25X0.85MM_NO_SILK")
      (libsource (lib "eagle-import") (part "M01PTH_SMD_3.25X0.85MM_NO_SILK"))
    )
    (comp (ref "JP925")
      (value "M01PTH_SMD_3.25X0.85MM_NO_SILK")
      (footprint "eagle-import:1X01_SMD_3.25X0.85MM_NO_SILK")
      (libsource (lib "eagle-import") (part "M01PTH_SMD_3.25X0.85MM_NO_SILK"))
    )
    (comp (ref "JP926")
      (value "M01PTH_SMD_3.25X0.85MM_NO_SILK")
      (footprint "eagle-import:1X01_SMD_3.25X0.85MM_NO_SILK")
      (libsource (lib "eagle-import") (part "M01PTH_SMD_3.25X0.85MM_NO_SILK"))
    )
    (comp (ref "JP927")
      (value "M01PTH_SMD_3.25X0.85MM_NO_SILK")
      (footprint "eagle-import:1X01_SMD_3.25X0.85MM_NO_SILK")
      (libsource (lib "eagle-import") (part "M01PTH_SMD_3.25X0.85MM_NO_SILK"))
    )
    (comp (ref "JP928")
      (value "M01PTH_SMD_3.25X0.85MM_NO_SILK")
      (footprint "eagle-import:1X01_SMD_3.25X0.85MM_NO_SILK")
      (libsource (lib "eagle-import") (part "M01PTH_SMD_3.25X0.85MM_NO_SILK"))
    )
    (comp (ref "JP929")
      (value "M01PTH_SMD_3.25X0.85MM_NO_SILK")
      (footprint "eagle-import:1X01_SMD_3.25X0.85MM_NO_SILK")
      (libsource (lib "eagle-import") (part "M01PTH_SMD_3.25X0.85MM_NO_SILK"))
    )
    (comp (ref "JP930")
      (value "M01PTH_SMD_3.25X0.85MM_NO_SILK")
      (footprint "eagle-import:1X01_SMD_3.25X0.85MM_NO_SILK")
      (libsource (lib "eagle-import") (part "M01PTH_SMD_3.25X0.85MM_NO_SILK"))
    )
    (comp (ref "JP931")
      (value "M01PTH_SMD_3.25X0.85MM_NO_SILK")
      (footprint "eagle-import:1X01_SMD_3.25X0.85MM_NO_SILK")
      (libsource (lib "eagle-import") (part "M01PTH_SMD_3.25X0.85MM_NO_SILK"))
    )
    (comp (ref "JP932")
      (value "M01PTH_SMD_3.25X0.85MM_NO_SILK")
      (footprint "eagle-import:1X01_SMD_3.25X0.85MM_NO_SILK")
      (libsource (lib "eagle-import") (part "M01PTH_SMD_3.25X0.85MM_NO_SILK"))
    )
    (comp (ref "JP933")
      (value "M01PTH_SMD_3.25X0.85MM_NO_SILK")
      (footprint "eagle-import:1X01_SMD_3.25X0.85MM_NO_SILK")
      (libsource (lib "eagle-import") (part "M01PTH_SMD_3.25X0.85MM_NO_SILK"))
    )
    (comp (ref "JP934")
      (value "M01PTH_SMD_3.25X0.85MM_NO_SILK")
      (footprint "eagle-import:1X01_SMD_3.25X0.85MM_NO_SILK")
      (libsource (lib "eagle-import") (part "M01PTH_SMD_3.25X0.85MM_NO_SILK"))
    )
    (comp (ref "JP935")
      (value "M01PTH_SMD_3.25X0.85MM_NO_SILK")
      (footprint "eagle-import:1X01_SMD_3.25X0.85MM_NO_SILK")
      (libsource (lib "eagle-import") (part "M01PTH_SMD_3.25X0.85MM_NO_SILK"))
    )
    (comp (ref "JP936")
      (value "M01PTH_SMD_3.25X0.85MM_NO_SILK")
      (footprint "eagle-import:1X01_SMD_3.25X0.85MM_NO_SILK")
      (libsource (lib "eagle-import") (part "M01PTH_SMD_3.25X0.85MM_NO_SILK"))
    )
    (comp (ref "JP937")
      (value "M01PTH_SMD_3.25X0.85MM_NO_SILK")
      (footprint "eagle-import:1X01_SMD_3.25X0.85MM_NO_SILK")
      (libsource (lib "eagle-import") (part "M01PTH_SMD_3.25X0.85MM_NO_SILK"))
    )
    (comp (ref "JP938")
      (value "M01PTH_SMD_3.25X0.85MM_NO_SILK")
      (footprint "eagle-import:1X01_SMD_3.25X0.85MM_NO_SILK")
      (libsource (lib "eagle-import") (part "M01PTH_SMD_3.25X0.85MM_NO_SILK"))
    )
    (comp (ref "JP939")
      (value "M01PTH_SMD_3.25X0.85MM_NO_SILK")
      (footprint "eagle-import:1X01_SMD_3.25X0.85MM_NO_SILK")
      (libsource (lib "eagle-import") (part "M01PTH_SMD_3.25X0.85MM_NO_SILK"))
    )
    (comp (ref "JP940")
      (value "M01PTH_SMD_3.25X0.85MM_NO_SILK")
      (footprint "eagle-import:1X01_SMD_3.25X0.85MM_NO_SILK")
      (libsource (lib "eagle-import") (part "M01PTH_SMD_3.25X0.85MM_NO_SILK"))
    )
    (comp (ref "JP941")
      (value "M01PTH_SMD_3.25X0.85MM_NO_SILK")
      (footprint "eagle-import:1X01_SMD_3.25X0.85MM_NO_SILK")
      (libsource (lib "eagle-import") (part "M01PTH_SMD_3.25X0.85MM_NO_SILK"))
    )
    (comp (ref "JP942")
      (value "M01PTH_SMD_3.25X0.85MM_NO_SILK")
      (footprint "eagle-import:1X01_SMD_3.25X0.85MM_NO_SILK")
      (libsource (lib "eagle-import") (part "M01PTH_SMD_3.25X0.85MM_NO_SILK"))
    )
    (comp (ref "JP943")
      (value "M01PTH_SMD_3.25X0.85MM_NO_SILK")
      (footprint "eagle-import:1X01_SMD_3.25X0.85MM_NO_SILK")
      (libsource (lib "eagle-import") (part "M01PTH_SMD_3.25X0.85MM_NO_SILK"))
    )
    (comp (ref "JP944")
      (value "M01PTH_SMD_3.25X0.85MM_NO_SILK")
      (footprint "eagle-import:1X01_SMD_3.25X0.85MM_NO_SILK")
      (libsource (lib "eagle-import") (part "M01PTH_SMD_3.25X0.85MM_NO_SILK"))
    )
    (comp (ref "JP945")
      (value "M01PTH_SMD_3.25X0.85MM_NO_SILK")
      (footprint "eagle-import:1X01_SMD_3.25X0.85MM_NO_SILK")
      (libsource (lib "eagle-import") (part "M01PTH_SMD_3.25X0.85MM_NO_SILK"))
    )
    (comp (ref "JP946")
      (value "M01PTH_SMD_3.25X0.85MM_NO_SILK")
      (footprint "eagle-import:1X01_SMD_3.25X0.85MM_NO_SILK")
      (libsource (lib "eagle-import") (part "M01PTH_SMD_3.25X0.85MM_NO_SILK"))
    )
    (comp (ref "JP947")
      (value "M01PTH_SMD_3.25X0.85MM_NO_SILK")
      (footprint "eagle-import:1X01_SMD_3.25X0.85MM_NO_SILK")
      (libsource (lib "eagle-import") (part "M01PTH_SMD_3.25X0.85MM_NO_SILK"))
    )
    (comp (ref "JP948")
      (value "M01PTH_SMD_3.25X0.85MM_NO_SILK")
      (footprint "eagle-import:1X01_SMD_3.25X0.85MM_NO_SILK")
      (libsource (lib "eagle-import") (part "M01PTH_SMD_3.25X0.85MM_NO_SILK"))
    )
    (comp (ref "JP949")
      (value "M01PTH_SMD_3.25X0.85MM_NO_SILK")
      (footprint "eagle-import:1X01_SMD_3.25X0.85MM_NO_SILK")
      (libsource (lib "eagle-import") (part "M01PTH_SMD_3.25X0.85MM_NO_SILK"))
    )
    (comp (ref "JP950")
      (value "M01PTH_SMD_3.25X0.85MM_NO_SILK")
      (footprint "eagle-import:1X01_SMD_3.25X0.85MM_NO_SILK")
      (libsource (lib "eagle-import") (part "M01PTH_SMD_3.25X0.85MM_NO_SILK"))
    )
    (comp (ref "JP951")
      (value "M01PTH_SMD_3.25X0.85MM_NO_SILK")
      (footprint "eagle-import:1X01_SMD_3.25X0.85MM_NO_SILK")
      (libsource (lib "eagle-import") (part "M01PTH_SMD_3.25X0.85MM_NO_SILK"))
    )
    (comp (ref "JP952")
      (value "M01PTH_SMD_3.25X0.85MM_NO_SILK")
      (footprint "eagle-import:1X01_SMD_3.25X0.85MM_NO_SILK")
      (libsource (lib "eagle-import") (part "M01PTH_SMD_3.25X0.85MM_NO_SILK"))
    )
    (comp (ref "JP953")
      (value "M01PTH_SMD_3.25X0.85MM_NO_SILK")
      (footprint "eagle-import:1X01_SMD_3.25X0.85MM_NO_SILK")
      (libsource (lib "eagle-import") (part "M01PTH_SMD_3.25X0.85MM_NO_SILK"))
    )
    (comp (ref "JP954")
      (value "M01PTH_SMD_3.25X0.85MM_NO_SILK")
      (footprint "eagle-import:1X01_SMD_3.25X0.85MM_NO_SILK")
      (libsource (lib "eagle-import") (part "M01PTH_SMD_3.25X0.85MM_NO_SILK"))
    )
    (comp (ref "JP955")
      (value "M01PTH_SMD_3.25X0.85MM_NO_SILK")
      (footprint "eagle-import:1X01_SMD_3.25X0.85MM_NO_SILK")
      (libsource (lib "eagle-import") (part "M01PTH_SMD_3.25X0.85MM_NO_SILK"))
    )
    (comp (ref "JP956")
      (value "M01PTH_SMD_3.25X0.85MM_NO_SILK")
      (footprint "eagle-import:1X01_SMD_3.25X0.85MM_NO_SILK")
      (libsource (lib "eagle-import") (part "M01PTH_SMD_3.25X0.85MM_NO_SILK"))
    )
    (comp (ref "JP957")
      (value "M01PTH_SMD_3.25X0.85MM_NO_SILK")
      (footprint "eagle-import:1X01_SMD_3.25X0.85MM_NO_SILK")
      (libsource (lib "eagle-import") (part "M01PTH_SMD_3.25X0.85MM_NO_SILK"))
    )
    (comp (ref "JP958")
      (value "M01PTH_SMD_3.25X0.85MM_NO_SILK")
      (footprint "eagle-import:1X01_SMD_3.25X0.85MM_NO_SILK")
      (libsource (lib "eagle-import") (part "M01PTH_SMD_3.25X0.85MM_NO_SILK"))
    )
    (comp (ref "JP959")
      (value "M01PTH_SMD_3.25X0.85MM_NO_SILK")
      (footprint "eagle-import:1X01_SMD_3.25X0.85MM_NO_SILK")
      (libsource (lib "eagle-import") (part "M01PTH_SMD_3.25X0.85MM_NO_SILK"))
    )
    (comp (ref "JP960")
      (value "M01PTH_SMD_3.25X0.85MM_NO_SILK")
      (footprint "eagle-import:1X01_SMD_3.25X0.85MM_NO_SILK")
      (libsource (lib "eagle-import") (part "M01PTH_SMD_3.25X0.85MM_NO_SILK"))
    )
    (comp (ref "JP961")
      (value "M01PTH_SMD_3.25X0.85MM_NO_SILK")
      (footprint "eagle-import:1X01_SMD_3.25X0.85MM_NO_SILK")
      (libsource (lib "eagle-import") (part "M01PTH_SMD_3.25X0.85MM_NO_SILK"))
    )
    (comp (ref "JP962")
      (value "M01PTH_SMD_3.25X0.85MM_NO_SILK")
      (footprint "eagle-import:1X01_SMD_3.25X0.85MM_NO_SILK")
      (libsource (lib "eagle-import") (part "M01PTH_SMD_3.25X0.85MM_NO_SILK"))
    )
    (comp (ref "JP963")
      (value "M01PTH_SMD_3.25X0.85MM_NO_SILK")
      (footprint "eagle-import:1X01_SMD_3.25X0.85MM_NO_SILK")
      (libsource (lib "eagle-import") (part "M01PTH_SMD_3.25X0.85MM_NO_SILK"))
    )
    (comp (ref "JP964")
      (value "M01PTH_SMD_3.25X0.85MM_NO_SILK")
      (footprint "eagle-import:1X01_SMD_3.25X0.85MM_NO_SILK")
      (libsource (lib "eagle-import") (part "M01PTH_SMD_3.25X0.85MM_NO_SILK"))
    )
    (comp (ref "JP965")
      (value "M01PTH_SMD_3.25X0.85MM_NO_SILK")
      (footprint "eagle-import:1X01_SMD_3.25X0.85MM_NO_SILK")
      (libsource (lib "eagle-import") (part "M01PTH_SMD_3.25X0.85MM_NO_SILK"))
    )
    (comp (ref "JP966")
      (value "M01PTH_SMD_3.25X0.85MM_NO_SILK")
      (footprint "eagle-import:1X01_SMD_3.25X0.85MM_NO_SILK")
      (libsource (lib "eagle-import") (part "M01PTH_SMD_3.25X0.85MM_NO_SILK"))
    )
    (comp (ref "JP967")
      (value "M01PTH_SMD_3.25X0.85MM_NO_SILK")
      (footprint "eagle-import:1X01_SMD_3.25X0.85MM_NO_SILK")
      (libsource (lib "eagle-import") (part "M01PTH_SMD_3.25X0.85MM_NO_SILK"))
    )
    (comp (ref "JP968")
      (value "M01PTH_SMD_3.25X0.85MM_NO_SILK")
      (footprint "eagle-import:1X01_SMD_3.25X0.85MM_NO_SILK")
      (libsource (lib "eagle-import") (part "M01PTH_SMD_3.25X0.85MM_NO_SILK"))
    )
    (comp (ref "JP969")
      (value "M01PTH_SMD_3.25X0.85MM_NO_SILK")
      (footprint "eagle-import:1X01_SMD_3.25X0.85MM_NO_SILK")
      (libsource (lib "eagle-import") (part "M01PTH_SMD_3.25X0.85MM_NO_SILK"))
    )
    (comp (ref "JP970")
      (value "M01PTH_SMD_3.25X0.85MM_NO_SILK")
      (footprint "eagle-import:1X01_SMD_3.25X0.85MM_NO_SILK")
      (libsource (lib "eagle-import") (part "M01PTH_SMD_3.25X0.85MM_NO_SILK"))
    )
    (comp (ref "JP971")
      (value "M01PTH_SMD_3.25X0.85MM_NO_SILK")
      (footprint "eagle-import:1X01_SMD_3.25X0.85MM_NO_SILK")
      (libsource (lib "eagle-import") (part "M01PTH_SMD_3.25X0.85MM_NO_SILK"))
    )
    (comp (ref "JP972")
      (value "M01PTH_SMD_3.25X0.85MM_NO_SILK")
      (footprint "eagle-import:1X01_SMD_3.25X0.85MM_NO_SILK")
      (libsource (lib "eagle-import") (part "M01PTH_SMD_3.25X0.85MM_NO_SILK"))
    )
    (comp (ref "JP973")
      (value "M01PTH_SMD_3.25X0.85MM_NO_SILK")
      (footprint "eagle-import:1X01_SMD_3.25X0.85MM_NO_SILK")
      (libsource (lib "eagle-import") (part "M01PTH_SMD_3.25X0.85MM_NO_SILK"))
    )
    (comp (ref "JP974")
      (value "M01PTH_SMD_3.25X0.85MM_NO_SILK")
      (footprint "eagle-import:1X01_SMD_3.25X0.85MM_NO_SILK")
      (libsource (lib "eagle-import") (part "M01PTH_SMD_3.25X0.85MM_NO_SILK"))
    )
    (comp (ref "JP975")
      (value "M01PTH_SMD_3.25X0.85MM_NO_SILK")
      (footprint "eagle-import:1X01_SMD_3.25X0.85MM_NO_SILK")
      (libsource (lib "eagle-import") (part "M01PTH_SMD_3.25X0.85MM_NO_SILK"))
    )
    (comp (ref "JP976")
      (value "M01PTH_SMD_3.25X0.85MM_NO_SILK")
      (footprint "eagle-import:1X01_SMD_3.25X0.85MM_NO_SILK")
      (libsource (lib "eagle-import") (part "M01PTH_SMD_3.25X0.85MM_NO_SILK"))
    )
    (comp (ref "JP977")
      (value "M01PTH_SMD_3.25X0.85MM_NO_SILK")
      (footprint "eagle-import:1X01_SMD_3.25X0.85MM_NO_SILK")
      (libsource (lib "eagle-import") (part "M01PTH_SMD_3.25X0.85MM_NO_SILK"))
    )
    (comp (ref "JP978")
      (value "M01PTH_SMD_3.25X0.85MM_NO_SILK")
      (footprint "eagle-import:1X01_SMD_3.25X0.85MM_NO_SILK")
      (libsource (lib "eagle-import") (part "M01PTH_SMD_3.25X0.85MM_NO_SILK"))
    )
    (comp (ref "JP979")
      (value "M01PTH_SMD_3.25X0.85MM_NO_SILK")
      (footprint "eagle-import:1X01_SMD_3.25X0.85MM_NO_SILK")
      (libsource (lib "eagle-import") (part "M01PTH_SMD_3.25X0.85MM_NO_SILK"))
    )
    (comp (ref "JP980")
      (value "M01PTH_SMD_3.25X0.85MM_NO_SILK")
      (footprint "eagle-import:1X01_SMD_3.25X0.85MM_NO_SILK")
      (libsource (lib "eagle-import") (part "M01PTH_SMD_3.25X0.85MM_NO_SILK"))
    )
    (comp (ref "JP981")
      (value "M01PTH_SMD_3.25X0.85MM_NO_SILK")
      (footprint "eagle-import:1X01_SMD_3.25X0.85MM_NO_SILK")
      (libsource (lib "eagle-import") (part "M01PTH_SMD_3.25X0.85MM_NO_SILK"))
    )
    (comp (ref "JP982")
      (value "M01PTH_SMD_3.25X0.85MM_NO_SILK")
      (footprint "eagle-import:1X01_SMD_3.25X0.85MM_NO_SILK")
      (libsource (lib "eagle-import") (part "M01PTH_SMD_3.25X0.85MM_NO_SILK"))
    )
    (comp (ref "JP983")
      (value "M01PTH_SMD_3.25X0.85MM_NO_SILK")
      (footprint "eagle-import:1X01_SMD_3.25X0.85MM_NO_SILK")
      (libsource (lib "eagle-import") (part "M01PTH_SMD_3.25X0.85MM_NO_SILK"))
    )
    (comp (ref "JP984")
      (value "M01PTH_SMD_3.25X0.85MM_NO_SILK")
      (footprint "eagle-import:1X01_SMD_3.25X0.85MM_NO_SILK")
      (libsource (lib "eagle-import") (part "M01PTH_SMD_3.25X0.85MM_NO_SILK"))
    )
    (comp (ref "JP985")
      (value "M01PTH_SMD_3.25X0.85MM_NO_SILK")
      (footprint "eagle-import:1X01_SMD_3.25X0.85MM_NO_SILK")
      (libsource (lib "eagle-import") (part "M01PTH_SMD_3.25X0.85MM_NO_SILK"))
    )
    (comp (ref "JP986")
      (value "M01PTH_SMD_3.25X0.85MM_NO_SILK")
      (footprint "eagle-import:1X01_SMD_3.25X0.85MM_NO_SILK")
      (libsource (lib "eagle-import") (part "M01PTH_SMD_3.25X0.85MM_NO_SILK"))
    )
    (comp (ref "JP987")
      (value "M01PTH_SMD_3.25X0.85MM_NO_SILK")
      (footprint "eagle-import:1X01_SMD_3.25X0.85MM_NO_SILK")
      (libsource (lib "eagle-import") (part "M01PTH_SMD_3.25X0.85MM_NO_SILK"))
    )
    (comp (ref "JP988")
      (value "M01PTH_SMD_3.25X0.85MM_NO_SILK")
      (footprint "eagle-import:1X01_SMD_3.25X0.85MM_NO_SILK")
      (libsource (lib "eagle-import") (part "M01PTH_SMD_3.25X0.85MM_NO_SILK"))
    )
    (comp (ref "JP989")
      (value "M01PTH_SMD_3.25X0.85MM_NO_SILK")
      (footprint "eagle-import:1X01_SMD_3.25X0.85MM_NO_SILK")
      (libsource (lib "eagle-import") (part "M01PTH_SMD_3.25X0.85MM_NO_SILK"))
    )
    (comp (ref "JP990")
      (value "M01PTH_SMD_3.25X0.85MM_NO_SILK")
      (footprint "eagle-import:1X01_SMD_3.25X0.85MM_NO_SILK")
      (libsource (lib "eagle-import") (part "M01PTH_SMD_3.25X0.85MM_NO_SILK"))
    )
    (comp (ref "JP991")
      (value "M01PTH_SMD_3.25X0.85MM_NO_SILK")
      (footprint "eagle-import:1X01_SMD_3.25X0.85MM_NO_SILK")
      (libsource (lib "eagle-import") (part "M01PTH_SMD_3.25X0.85MM_NO_SILK"))
    )
    (comp (ref "JP992")
      (value "M01PTH_SMD_3.25X0.85MM_NO_SILK")
      (footprint "eagle-import:1X01_SMD_3.25X0.85MM_NO_SILK")
      (libsource (lib "eagle-import") (part "M01PTH_SMD_3.25X0.85MM_NO_SILK"))
    )
    (comp (ref "JP993")
      (value "M01PTH_SMD_3.25X0.85MM_NO_SILK")
      (footprint "eagle-import:1X01_SMD_3.25X0.85MM_NO_SILK")
      (libsource (lib "eagle-import") (part "M01PTH_SMD_3.25X0.85MM_NO_SILK"))
    )
    (comp (ref "JP994")
      (value "M01PTH_SMD_3.25X0.85MM_NO_SILK")
      (footprint "eagle-import:1X01_SMD_3.25X0.85MM_NO_SILK")
      (libsource (lib "eagle-import") (part "M01PTH_SMD_3.25X0.85MM_NO_SILK"))
    )
    (comp (ref "JP995")
      (value "M01PTH_SMD_3.25X0.85MM_NO_SILK")
      (footprint "eagle-import:1X01_SMD_3.25X0.85MM_NO_SILK")
      (libsource (lib "eagle-import") (part "M01PTH_SMD_3.25X0.85MM_NO_SILK"))
    )
    (comp (ref "JP996")
      (value "M01PTH_SMD_3.25X0.85MM_NO_SILK")
      (footprint "eagle-import:1X01_SMD_3.25X0.85MM_NO_SILK")
      (libsource (lib "eagle-import") (part "M01PTH_SMD_3.25X0.85MM_NO_SILK"))
    )
    (comp (ref "JP997")
      (value "M01PTH_SMD_3.25X0.85MM_NO_SILK")
      (footprint "eagle-import:1X01_SMD_3.25X0.85MM_NO_SILK")
      (libsource (lib "eagle-import") (part "M01PTH_SMD_3.25X0.85MM_NO_SILK"))
    )
    (comp (ref "JP998")
      (value "M01PTH_SMD_3.25X0.85MM_NO_SILK")
      (footprint "eagle-import:1X01_SMD_3.25X0.85MM_NO_SILK")
      (libsource (lib "eagle-import") (part "M01PTH_SMD_3.25X0.85MM_NO_SILK"))
    )
    (comp (ref "JP999")
      (value "M01PTH_SMD_3.25X0.85MM_NO_SILK")
      (footprint "eagle-import:1X01_SMD_3.25X0.85MM_NO_SILK")
      (libsource (lib "eagle-import") (part "M01PTH_SMD_3.25X0.85MM_NO_SILK"))
    )
    (comp (ref "JP1000")
      (value "M01PTH_SMD_3.25X0.85MM_NO_SILK")
      (footprint "eagle-import:1X01_SMD_3.25X0.85MM_NO_SILK")
      (libsource (lib "eagle-import") (part "M01PTH_SMD_3.25X0.85MM_NO_SILK"))
    )
    (comp (ref "JP1001")
      (value "M01PTH_SMD_3.25X0.85MM_NO_SILK")
      (footprint "eagle-import:1X01_SMD_3.25X0.85MM_NO_SILK")
      (libsource (lib "eagle-import") (part "M01PTH_SMD_3.25X0.85MM_NO_SILK"))
    )
    (comp (ref "JP1002")
      (value "M01PTH_SMD_3.25X0.85MM_NO_SILK")
      (footprint "eagle-import:1X01_SMD_3.25X0.85MM_NO_SILK")
      (libsource (lib "eagle-import") (part "M01PTH_SMD_3.25X0.85MM_NO_SILK"))
    )
    (comp (ref "JP1003")
      (value "M01PTH_SMD_3.25X0.85MM_NO_SILK")
      (footprint "eagle-import:1X01_SMD_3.25X0.85MM_NO_SILK")
      (libsource (lib "eagle-import") (part "M01PTH_SMD_3.25X0.85MM_NO_SILK"))
    )
    (comp (ref "JP1004")
      (value "M01PTH_SMD_3.25X0.85MM_NO_SILK")
      (footprint "eagle-import:1X01_SMD_3.25X0.85MM_NO_SILK")
      (libsource (lib "eagle-import") (part "M01PTH_SMD_3.25X0.85MM_NO_SILK"))
    )
    (comp (ref "JP1005")
      (value "M01PTH_SMD_3.25X0.85MM_NO_SILK")
      (footprint "eagle-import:1X01_SMD_3.25X0.85MM_NO_SILK")
      (libsource (lib "eagle-import") (part "M01PTH_SMD_3.25X0.85MM_NO_SILK"))
    )
    (comp (ref "JP1006")
      (value "M01PTH_SMD_3.25X0.85MM_NO_SILK")
      (footprint "eagle-import:1X01_SMD_3.25X0.85MM_NO_SILK")
      (libsource (lib "eagle-import") (part "M01PTH_SMD_3.25X0.85MM_NO_SILK"))
    )
    (comp (ref "JP1007")
      (value "M01PTH_SMD_3.25X0.85MM_NO_SILK")
      (footprint "eagle-import:1X01_SMD_3.25X0.85MM_NO_SILK")
      (libsource (lib "eagle-import") (part "M01PTH_SMD_3.25X0.85MM_NO_SILK"))
    )
    (comp (ref "JP1008")
      (value "M01PTH_SMD_3.25X0.85MM_NO_SILK")
      (footprint "eagle-import:1X01_SMD_3.25X0.85MM_NO_SILK")
      (libsource (lib "eagle-import") (part "M01PTH_SMD_3.25X0.85MM_NO_SILK"))
    )
    (comp (ref "JP1009")
      (value "M01PTH_SMD_3.25X0.85MM_NO_SILK")
      (footprint "eagle-import:1X01_SMD_3.25X0.85MM_NO_SILK")
      (libsource (lib "eagle-import") (part "M01PTH_SMD_3.25X0.85MM_NO_SILK"))
    )
    (comp (ref "JP1010")
      (value "M01PTH_SMD_3.25X0.85MM_NO_SILK")
      (footprint "eagle-import:1X01_SMD_3.25X0.85MM_NO_SILK")
      (libsource (lib "eagle-import") (part "M01PTH_SMD_3.25X0.85MM_NO_SILK"))
    )
    (comp (ref "JP1011")
      (value "M01PTH_SMD_3.25X0.85MM_NO_SILK")
      (footprint "eagle-import:1X01_SMD_3.25X0.85MM_NO_SILK")
      (libsource (lib "eagle-import") (part "M01PTH_SMD_3.25X0.85MM_NO_SILK"))
    )
    (comp (ref "JP1012")
      (value "M01PTH_SMD_3.25X0.85MM_NO_SILK")
      (footprint "eagle-import:1X01_SMD_3.25X0.85MM_NO_SILK")
      (libsource (lib "eagle-import") (part "M01PTH_SMD_3.25X0.85MM_NO_SILK"))
    )
    (comp (ref "JP1013")
      (value "M01PTH_SMD_3.25X0.85MM_NO_SILK")
      (footprint "eagle-import:1X01_SMD_3.25X0.85MM_NO_SILK")
      (libsource (lib "eagle-import") (part "M01PTH_SMD_3.25X0.85MM_NO_SILK"))
    )
    (comp (ref "JP1014")
      (value "M01PTH_SMD_3.25X0.85MM_NO_SILK")
      (footprint "eagle-import:1X01_SMD_3.25X0.85MM_NO_SILK")
      (libsource (lib "eagle-import") (part "M01PTH_SMD_3.25X0.85MM_NO_SILK"))
    )
    (comp (ref "JP1015")
      (value "M01PTH_SMD_3.25X0.85MM_NO_SILK")
      (footprint "eagle-import:1X01_SMD_3.25X0.85MM_NO_SILK")
      (libsource (lib "eagle-import") (part "M01PTH_SMD_3.25X0.85MM_NO_SILK"))
    )
    (comp (ref "JP1016")
      (value "M01PTH_SMD_3.25X0.85MM_NO_SILK")
      (footprint "eagle-import:1X01_SMD_3.25X0.85MM_NO_SILK")
      (libsource (lib "eagle-import") (part "M01PTH_SMD_3.25X0.85MM_NO_SILK"))
    )
    (comp (ref "JP1017")
      (value "M01PTH_SMD_3.25X0.85MM_NO_SILK")
      (footprint "eagle-import:1X01_SMD_3.25X0.85MM_NO_SILK")
      (libsource (lib "eagle-import") (part "M01PTH_SMD_3.25X0.85MM_NO_SILK"))
    )
    (comp (ref "JP1018")
      (value "M01PTH_SMD_3.25X0.85MM_NO_SILK")
      (footprint "eagle-import:1X01_SMD_3.25X0.85MM_NO_SILK")
      (libsource (lib "eagle-import") (part "M01PTH_SMD_3.25X0.85MM_NO_SILK"))
    )
    (comp (ref "JP1019")
      (value "M01PTH_SMD_3.25X0.85MM_NO_SILK")
      (footprint "eagle-import:1X01_SMD_3.25X0.85MM_NO_SILK")
      (libsource (lib "eagle-import") (part "M01PTH_SMD_3.25X0.85MM_NO_SILK"))
    )
    (comp (ref "JP1020")
      (value "M01PTH_SMD_3.25X0.85MM_NO_SILK")
      (footprint "eagle-import:1X01_SMD_3.25X0.85MM_NO_SILK")
      (libsource (lib "eagle-import") (part "M01PTH_SMD_3.25X0.85MM_NO_SILK"))
    )
    (comp (ref "JP1021")
      (value "M01PTH_SMD_3.25X0.85MM_NO_SILK")
      (footprint "eagle-import:1X01_SMD_3.25X0.85MM_NO_SILK")
      (libsource (lib "eagle-import") (part "M01PTH_SMD_3.25X0.85MM_NO_SILK"))
    )
    (comp (ref "JP1022")
      (value "M01PTH_SMD_3.25X0.85MM_NO_SILK")
      (footprint "eagle-import:1X01_SMD_3.25X0.85MM_NO_SILK")
      (libsource (lib "eagle-import") (part "M01PTH_SMD_3.25X0.85MM_NO_SILK"))
    )
    (comp (ref "JP1023")
      (value "M01PTH_SMD_3.25X0.85MM_NO_SILK")
      (footprint "eagle-import:1X01_SMD_3.25X0.85MM_NO_SILK")
      (libsource (lib "eagle-import") (part "M01PTH_SMD_3.25X0.85MM_NO_SILK"))
    )
    (comp (ref "JP1024")
      (value "M01PTH_SMD_3.25X0.85MM_NO_SILK")
      (footprint "eagle-import:1X01_SMD_3.25X0.85MM_NO_SILK")
      (libsource (lib "eagle-import") (part "M01PTH_SMD_3.25X0.85MM_NO_SILK"))
    )
    (comp (ref "JP1025")
      (value "M01PTH_SMD_3.25X0.85MM_NO_SILK")
      (footprint "eagle-import:1X01_SMD_3.25X0.85MM_NO_SILK")
      (libsource (lib "eagle-import") (part "M01PTH_SMD_3.25X0.85MM_NO_SILK"))
    )
    (comp (ref "JP1026")
      (value "M01PTH_SMD_3.25X0.85MM_NO_SILK")
      (footprint "eagle-import:1X01_SMD_3.25X0.85MM_NO_SILK")
      (libsource (lib "eagle-import") (part "M01PTH_SMD_3.25X0.85MM_NO_SILK"))
    )
    (comp (ref "JP1027")
      (value "M01PTH_SMD_3.25X0.85MM_NO_SILK")
      (footprint "eagle-import:1X01_SMD_3.25X0.85MM_NO_SILK")
      (libsource (lib "eagle-import") (part "M01PTH_SMD_3.25X0.85MM_NO_SILK"))
    )
    (comp (ref "JP1028")
      (value "M01PTH_SMD_3.25X0.85MM_NO_SILK")
      (footprint "eagle-import:1X01_SMD_3.25X0.85MM_NO_SILK")
      (libsource (lib "eagle-import") (part "M01PTH_SMD_3.25X0.85MM_NO_SILK"))
    )
    (comp (ref "JP1029")
      (value "M01PTH_SMD_3.25X0.85MM_NO_SILK")
      (footprint "eagle-import:1X01_SMD_3.25X0.85MM_NO_SILK")
      (libsource (lib "eagle-import") (part "M01PTH_SMD_3.25X0.85MM_NO_SILK"))
    )
    (comp (ref "JP1030")
      (value "M01PTH_SMD_3.25X0.85MM_NO_SILK")
      (footprint "eagle-import:1X01_SMD_3.25X0.85MM_NO_SILK")
      (libsource (lib "eagle-import") (part "M01PTH_SMD_3.25X0.85MM_NO_SILK"))
    )
    (comp (ref "JP1031")
      (value "M01PTH_SMD_3.25X0.85MM_NO_SILK")
      (footprint "eagle-import:1X01_SMD_3.25X0.85MM_NO_SILK")
      (libsource (lib "eagle-import") (part "M01PTH_SMD_3.25X0.85MM_NO_SILK"))
    )
    (comp (ref "JP1032")
      (value "M01PTH_SMD_3.25X0.85MM_NO_SILK")
      (footprint "eagle-import:1X01_SMD_3.25X0.85MM_NO_SILK")
      (libsource (lib "eagle-import") (part "M01PTH_SMD_3.25X0.85MM_NO_SILK"))
    )
    (comp (ref "JP1033")
      (value "M01PTH_SMD_3.25X0.85MM_NO_SILK")
      (footprint "eagle-import:1X01_SMD_3.25X0.85MM_NO_SILK")
      (libsource (lib "eagle-import") (part "M01PTH_SMD_3.25X0.85MM_NO_SILK"))
    )
    (comp (ref "JP1034")
      (value "M01PTH_SMD_3.25X0.85MM_NO_SILK")
      (footprint "eagle-import:1X01_SMD_3.25X0.85MM_NO_SILK")
      (libsource (lib "eagle-import") (part "M01PTH_SMD_3.25X0.85MM_NO_SILK"))
    )
    (comp (ref "JP1035")
      (value "M01PTH_SMD_3.25X0.85MM_NO_SILK")
      (footprint "eagle-import:1X01_SMD_3.25X0.85MM_NO_SILK")
      (libsource (lib "eagle-import") (part "M01PTH_SMD_3.25X0.85MM_NO_SILK"))
    )
    (comp (ref "JP1036")
      (value "M01PTH_SMD_3.25X0.85MM_NO_SILK")
      (footprint "eagle-import:1X01_SMD_3.25X0.85MM_NO_SILK")
      (libsource (lib "eagle-import") (part "M01PTH_SMD_3.25X0.85MM_NO_SILK"))
    )
    (comp (ref "JP1037")
      (value "M01PTH_SMD_3.25X0.85MM_NO_SILK")
      (footprint "eagle-import:1X01_SMD_3.25X0.85MM_NO_SILK")
      (libsource (lib "eagle-import") (part "M01PTH_SMD_3.25X0.85MM_NO_SILK"))
    )
    (comp (ref "JP1038")
      (value "M01PTH_SMD_3.25X0.85MM_NO_SILK")
      (footprint "eagle-import:1X01_SMD_3.25X0.85MM_NO_SILK")
      (libsource (lib "eagle-import") (part "M01PTH_SMD_3.25X0.85MM_NO_SILK"))
    )
    (comp (ref "JP1039")
      (value "M01PTH_SMD_3.25X0.85MM_NO_SILK")
      (footprint "eagle-import:1X01_SMD_3.25X0.85MM_NO_SILK")
      (libsource (lib "eagle-import") (part "M01PTH_SMD_3.25X0.85MM_NO_SILK"))
    )
    (comp (ref "JP1040")
      (value "M01PTH_SMD_3.25X0.85MM_NO_SILK")
      (footprint "eagle-import:1X01_SMD_3.25X0.85MM_NO_SILK")
      (libsource (lib "eagle-import") (part "M01PTH_SMD_3.25X0.85MM_NO_SILK"))
    )
    (comp (ref "JP1041")
      (value "M01PTH_SMD_3.25X0.85MM_NO_SILK")
      (footprint "eagle-import:1X01_SMD_3.25X0.85MM_NO_SILK")
      (libsource (lib "eagle-import") (part "M01PTH_SMD_3.25X0.85MM_NO_SILK"))
    )
    (comp (ref "JP1042")
      (value "M01PTH_SMD_3.25X0.85MM_NO_SILK")
      (footprint "eagle-import:1X01_SMD_3.25X0.85MM_NO_SILK")
      (libsource (lib "eagle-import") (part "M01PTH_SMD_3.25X0.85MM_NO_SILK"))
    )
    (comp (ref "JP1043")
      (value "M01PTH_SMD_3.25X0.85MM_NO_SILK")
      (footprint "eagle-import:1X01_SMD_3.25X0.85MM_NO_SILK")
      (libsource (lib "eagle-import") (part "M01PTH_SMD_3.25X0.85MM_NO_SILK"))
    )
    (comp (ref "JP1044")
      (value "M01PTH_SMD_3.25X0.85MM_NO_SILK")
      (footprint "eagle-import:1X01_SMD_3.25X0.85MM_NO_SILK")
      (libsource (lib "eagle-import") (part "M01PTH_SMD_3.25X0.85MM_NO_SILK"))
    )
    (comp (ref "JP1045")
      (value "M01PTH_SMD_3.25X0.85MM_NO_SILK")
      (footprint "eagle-import:1X01_SMD_3.25X0.85MM_NO_SILK")
      (libsource (lib "eagle-import") (part "M01PTH_SMD_3.25X0.85MM_NO_SILK"))
    )
    (comp (ref "JP1046")
      (value "M01PTH_SMD_3.25X0.85MM_NO_SILK")
      (footprint "eagle-import:1X01_SMD_3.25X0.85MM_NO_SILK")
      (libsource (lib "eagle-import") (part "M01PTH_SMD_3.25X0.85MM_NO_SILK"))
    )
    (comp (ref "JP1047")
      (value "M01PTH_SMD_3.25X0.85MM_NO_SILK")
      (footprint "eagle-import:1X01_SMD_3.25X0.85MM_NO_SILK")
      (libsource (lib "eagle-import") (part "M01PTH_SMD_3.25X0.85MM_NO_SILK"))
    )
    (comp (ref "JP1048")
      (value "M01PTH_SMD_3.25X0.85MM_NO_SILK")
      (footprint "eagle-import:1X01_SMD_3.25X0.85MM_NO_SILK")
      (libsource (lib "eagle-import") (part "M01PTH_SMD_3.25X0.85MM_NO_SILK"))
    )
    (comp (ref "JP1049")
      (value "M01PTH_SMD_3.25X0.85MM_NO_SILK")
      (footprint "eagle-import:1X01_SMD_3.25X0.85MM_NO_SILK")
      (libsource (lib "eagle-import") (part "M01PTH_SMD_3.25X0.85MM_NO_SILK"))
    )
    (comp (ref "JP1050")
      (value "M01PTH_SMD_3.25X0.85MM_NO_SILK")
      (footprint "eagle-import:1X01_SMD_3.25X0.85MM_NO_SILK")
      (libsource (lib "eagle-import") (part "M01PTH_SMD_3.25X0.85MM_NO_SILK"))
    )
    (comp (ref "JP1051")
      (value "M01PTH_SMD_3.25X0.85MM_NO_SILK")
      (footprint "eagle-import:1X01_SMD_3.25X0.85MM_NO_SILK")
      (libsource (lib "eagle-import") (part "M01PTH_SMD_3.25X0.85MM_NO_SILK"))
    )
    (comp (ref "JP1052")
      (value "M01PTH_SMD_3.25X0.85MM_NO_SILK")
      (footprint "eagle-import:1X01_SMD_3.25X0.85MM_NO_SILK")
      (libsource (lib "eagle-import") (part "M01PTH_SMD_3.25X0.85MM_NO_SILK"))
    )
    (comp (ref "JP1053")
      (value "M01PTH_SMD_3.25X0.85MM_NO_SILK")
      (footprint "eagle-import:1X01_SMD_3.25X0.85MM_NO_SILK")
      (libsource (lib "eagle-import") (part "M01PTH_SMD_3.25X0.85MM_NO_SILK"))
    )
    (comp (ref "JP1054")
      (value "M01PTH_SMD_3.25X0.85MM_NO_SILK")
      (footprint "eagle-import:1X01_SMD_3.25X0.85MM_NO_SILK")
      (libsource (lib "eagle-import") (part "M01PTH_SMD_3.25X0.85MM_NO_SILK"))
    )
    (comp (ref "JP1055")
      (value "M01PTH_SMD_3.25X0.85MM_NO_SILK")
      (footprint "eagle-import:1X01_SMD_3.25X0.85MM_NO_SILK")
      (libsource (lib "eagle-import") (part "M01PTH_SMD_3.25X0.85MM_NO_SILK"))
    )
    (comp (ref "JP1056")
      (value "M01PTH_SMD_3.25X0.85MM_NO_SILK")
      (footprint "eagle-import:1X01_SMD_3.25X0.85MM_NO_SILK")
      (libsource (lib "eagle-import") (part "M01PTH_SMD_3.25X0.85MM_NO_SILK"))
    )
    (comp (ref "JP1057")
      (value "M01PTH_SMD_3.25X0.85MM_NO_SILK")
      (footprint "eagle-import:1X01_SMD_3.25X0.85MM_NO_SILK")
      (libsource (lib "eagle-import") (part "M01PTH_SMD_3.25X0.85MM_NO_SILK"))
    )
    (comp (ref "JP1058")
      (value "M01PTH_SMD_3.25X0.85MM_NO_SILK")
      (footprint "eagle-import:1X01_SMD_3.25X0.85MM_NO_SILK")
      (libsource (lib "eagle-import") (part "M01PTH_SMD_3.25X0.85MM_NO_SILK"))
    )
    (comp (ref "JP1059")
      (value "M01PTH_SMD_3.25X0.85MM_NO_SILK")
      (footprint "eagle-import:1X01_SMD_3.25X0.85MM_NO_SILK")
      (libsource (lib "eagle-import") (part "M01PTH_SMD_3.25X0.85MM_NO_SILK"))
    )
    (comp (ref "JP1060")
      (value "M01PTH_SMD_3.25X0.85MM_NO_SILK")
      (footprint "eagle-import:1X01_SMD_3.25X0.85MM_NO_SILK")
      (libsource (lib "eagle-import") (part "M01PTH_SMD_3.25X0.85MM_NO_SILK"))
    )
    (comp (ref "JP1061")
      (value "M01PTH_SMD_3.25X0.85MM_NO_SILK")
      (footprint "eagle-import:1X01_SMD_3.25X0.85MM_NO_SILK")
      (libsource (lib "eagle-import") (part "M01PTH_SMD_3.25X0.85MM_NO_SILK"))
    )
    (comp (ref "JP1062")
      (value "M01PTH_SMD_3.25X0.85MM_NO_SILK")
      (footprint "eagle-import:1X01_SMD_3.25X0.85MM_NO_SILK")
      (libsource (lib "eagle-import") (part "M01PTH_SMD_3.25X0.85MM_NO_SILK"))
    )
    (comp (ref "JP1063")
      (value "M01PTH_SMD_3.25X0.85MM_NO_SILK")
      (footprint "eagle-import:1X01_SMD_3.25X0.85MM_NO_SILK")
      (libsource (lib "eagle-import") (part "M01PTH_SMD_3.25X0.85MM_NO_SILK"))
    )
    (comp (ref "JP1064")
      (value "M01PTH_SMD_3.25X0.85MM_NO_SILK")
      (footprint "eagle-import:1X01_SMD_3.25X0.85MM_NO_SILK")
      (libsource (lib "eagle-import") (part "M01PTH_SMD_3.25X0.85MM_NO_SILK"))
    )
    (comp (ref "JP1065")
      (value "M01PTH_SMD_3.25X0.85MM_NO_SILK")
      (footprint "eagle-import:1X01_SMD_3.25X0.85MM_NO_SILK")
      (libsource (lib "eagle-import") (part "M01PTH_SMD_3.25X0.85MM_NO_SILK"))
    )
    (comp (ref "JP1066")
      (value "M01PTH_SMD_3.25X0.85MM_NO_SILK")
      (footprint "eagle-import:1X01_SMD_3.25X0.85MM_NO_SILK")
      (libsource (lib "eagle-import") (part "M01PTH_SMD_3.25X0.85MM_NO_SILK"))
    )
    (comp (ref "JP1067")
      (value "M01PTH_SMD_3.25X0.85MM_NO_SILK")
      (footprint "eagle-import:1X01_SMD_3.25X0.85MM_NO_SILK")
      (libsource (lib "eagle-import") (part "M01PTH_SMD_3.25X0.85MM_NO_SILK"))
    )
    (comp (ref "JP1068")
      (value "M01PTH_SMD_3.25X0.85MM_NO_SILK")
      (footprint "eagle-import:1X01_SMD_3.25X0.85MM_NO_SILK")
      (libsource (lib "eagle-import") (part "M01PTH_SMD_3.25X0.85MM_NO_SILK"))
    )
    (comp (ref "JP1069")
      (value "M01PTH_SMD_3.25X0.85MM_NO_SILK")
      (footprint "eagle-import:1X01_SMD_3.25X0.85MM_NO_SILK")
      (libsource (lib "eagle-import") (part "M01PTH_SMD_3.25X0.85MM_NO_SILK"))
    )
    (comp (ref "JP1070")
      (value "M01PTH_SMD_3.25X0.85MM_NO_SILK")
      (footprint "eagle-import:1X01_SMD_3.25X0.85MM_NO_SILK")
      (libsource (lib "eagle-import") (part "M01PTH_SMD_3.25X0.85MM_NO_SILK"))
    )
    (comp (ref "JP1071")
      (value "M01PTH_SMD_3.25X0.85MM_NO_SILK")
      (footprint "eagle-import:1X01_SMD_3.25X0.85MM_NO_SILK")
      (libsource (lib "eagle-import") (part "M01PTH_SMD_3.25X0.85MM_NO_SILK"))
    )
    (comp (ref "JP1072")
      (value "M01PTH_SMD_3.25X0.85MM_NO_SILK")
      (footprint "eagle-import:1X01_SMD_3.25X0.85MM_NO_SILK")
      (libsource (lib "eagle-import") (part "M01PTH_SMD_3.25X0.85MM_NO_SILK"))
    )
    (comp (ref "JP1073")
      (value "M01PTH_SMD_3.25X0.85MM_NO_SILK")
      (footprint "eagle-import:1X01_SMD_3.25X0.85MM_NO_SILK")
      (libsource (lib "eagle-import") (part "M01PTH_SMD_3.25X0.85MM_NO_SILK"))
    )
    (comp (ref "JP1074")
      (value "M01PTH_SMD_3.25X0.85MM_NO_SILK")
      (footprint "eagle-import:1X01_SMD_3.25X0.85MM_NO_SILK")
      (libsource (lib "eagle-import") (part "M01PTH_SMD_3.25X0.85MM_NO_SILK"))
    )
    (comp (ref "JP1075")
      (value "M01PTH_SMD_3.25X0.85MM_NO_SILK")
      (footprint "eagle-import:1X01_SMD_3.25X0.85MM_NO_SILK")
      (libsource (lib "eagle-import") (part "M01PTH_SMD_3.25X0.85MM_NO_SILK"))
    )
    (comp (ref "JP1076")
      (value "M01PTH_SMD_3.25X0.85MM_NO_SILK")
      (footprint "eagle-import:1X01_SMD_3.25X0.85MM_NO_SILK")
      (libsource (lib "eagle-import") (part "M01PTH_SMD_3.25X0.85MM_NO_SILK"))
    )
    (comp (ref "JP1077")
      (value "M01PTH_SMD_3.25X0.85MM_NO_SILK")
      (footprint "eagle-import:1X01_SMD_3.25X0.85MM_NO_SILK")
      (libsource (lib "eagle-import") (part "M01PTH_SMD_3.25X0.85MM_NO_SILK"))
    )
    (comp (ref "JP1078")
      (value "M01PTH_SMD_3.25X0.85MM_NO_SILK")
      (footprint "eagle-import:1X01_SMD_3.25X0.85MM_NO_SILK")
      (libsource (lib "eagle-import") (part "M01PTH_SMD_3.25X0.85MM_NO_SILK"))
    )
    (comp (ref "JP1079")
      (value "M01PTH_SMD_3.25X0.85MM_NO_SILK")
      (footprint "eagle-import:1X01_SMD_3.25X0.85MM_NO_SILK")
      (libsource (lib "eagle-import") (part "M01PTH_SMD_3.25X0.85MM_NO_SILK"))
    )
    (comp (ref "JP1080")
      (value "M01PTH_SMD_3.25X0.85MM_NO_SILK")
      (footprint "eagle-import:1X01_SMD_3.25X0.85MM_NO_SILK")
      (libsource (lib "eagle-import") (part "M01PTH_SMD_3.25X0.85MM_NO_SILK"))
    )
    (comp (ref "JP1081")
      (value "M01PTH_SMD_3.25X0.85MM_NO_SILK")
      (footprint "eagle-import:1X01_SMD_3.25X0.85MM_NO_SILK")
      (libsource (lib "eagle-import") (part "M01PTH_SMD_3.25X0.85MM_NO_SILK"))
    )
    (comp (ref "JP1082")
      (value "M01PTH_SMD_3.25X0.85MM_NO_SILK")
      (footprint "eagle-import:1X01_SMD_3.25X0.85MM_NO_SILK")
      (libsource (lib "eagle-import") (part "M01PTH_SMD_3.25X0.85MM_NO_SILK"))
    )
    (comp (ref "JP1083")
      (value "M01PTH_SMD_3.25X0.85MM_NO_SILK")
      (footprint "eagle-import:1X01_SMD_3.25X0.85MM_NO_SILK")
      (libsource (lib "eagle-import") (part "M01PTH_SMD_3.25X0.85MM_NO_SILK"))
    )
    (comp (ref "JP1084")
      (value "M01PTH_SMD_3.25X0.85MM_NO_SILK")
      (footprint "eagle-import:1X01_SMD_3.25X0.85MM_NO_SILK")
      (libsource (lib "eagle-import") (part "M01PTH_SMD_3.25X0.85MM_NO_SILK"))
    )
    (comp (ref "JP1085")
      (value "M01PTH_SMD_3.25X0.85MM_NO_SILK")
      (footprint "eagle-import:1X01_SMD_3.25X0.85MM_NO_SILK")
      (libsource (lib "eagle-import") (part "M01PTH_SMD_3.25X0.85MM_NO_SILK"))
    )
    (comp (ref "JP1086")
      (value "M01PTH_SMD_3.25X0.85MM_NO_SILK")
      (footprint "eagle-import:1X01_SMD_3.25X0.85MM_NO_SILK")
      (libsource (lib "eagle-import") (part "M01PTH_SMD_3.25X0.85MM_NO_SILK"))
    )
    (comp (ref "JP1087")
      (value "M01PTH_SMD_3.25X0.85MM_NO_SILK")
      (footprint "eagle-import:1X01_SMD_3.25X0.85MM_NO_SILK")
      (libsource (lib "eagle-import") (part "M01PTH_SMD_3.25X0.85MM_NO_SILK"))
    )
    (comp (ref "JP1088")
      (value "M01PTH_SMD_3.25X0.85MM_NO_SILK")
      (footprint "eagle-import:1X01_SMD_3.25X0.85MM_NO_SILK")
      (libsource (lib "eagle-import") (part "M01PTH_SMD_3.25X0.85MM_NO_SILK"))
    )
    (comp (ref "JP1089")
      (value "M01PTH_SMD_3.25X0.85MM_NO_SILK")
      (footprint "eagle-import:1X01_SMD_3.25X0.85MM_NO_SILK")
      (libsource (lib "eagle-import") (part "M01PTH_SMD_3.25X0.85MM_NO_SILK"))
    )
    (comp (ref "JP1090")
      (value "M01PTH_SMD_3.25X0.85MM_NO_SILK")
      (footprint "eagle-import:1X01_SMD_3.25X0.85MM_NO_SILK")
      (libsource (lib "eagle-import") (part "M01PTH_SMD_3.25X0.85MM_NO_SILK"))
    )
    (comp (ref "JP1091")
      (value "M01PTH_SMD_3.25X0.85MM_NO_SILK")
      (footprint "eagle-import:1X01_SMD_3.25X0.85MM_NO_SILK")
      (libsource (lib "eagle-import") (part "M01PTH_SMD_3.25X0.85MM_NO_SILK"))
    )
    (comp (ref "JP1092")
      (value "M01PTH_SMD_3.25X0.85MM_NO_SILK")
      (footprint "eagle-import:1X01_SMD_3.25X0.85MM_NO_SILK")
      (libsource (lib "eagle-import") (part "M01PTH_SMD_3.25X0.85MM_NO_SILK"))
    )
    (comp (ref "JP1093")
      (value "M01PTH_SMD_3.25X0.85MM_NO_SILK")
      (footprint "eagle-import:1X01_SMD_3.25X0.85MM_NO_SILK")
      (libsource (lib "eagle-import") (part "M01PTH_SMD_3.25X0.85MM_NO_SILK"))
    )
    (comp (ref "JP1094")
      (value "M01PTH_SMD_3.25X0.85MM_NO_SILK")
      (footprint "eagle-import:1X01_SMD_3.25X0.85MM_NO_SILK")
      (libsource (lib "eagle-import") (part "M01PTH_SMD_3.25X0.85MM_NO_SILK"))
    )
    (comp (ref "JP1095")
      (value "M01PTH_SMD_3.25X0.85MM_NO_SILK")
      (footprint "eagle-import:1X01_SMD_3.25X0.85MM_NO_SILK")
      (libsource (lib "eagle-import") (part "M01PTH_SMD_3.25X0.85MM_NO_SILK"))
    )
    (comp (ref "JP1096")
      (value "M01PTH_SMD_3.25X0.85MM_NO_SILK")
      (footprint "eagle-import:1X01_SMD_3.25X0.85MM_NO_SILK")
      (libsource (lib "eagle-import") (part "M01PTH_SMD_3.25X0.85MM_NO_SILK"))
    )
    (comp (ref "JP1097")
      (value "M01PTH_SMD_3.25X0.85MM_NO_SILK")
      (footprint "eagle-import:1X01_SMD_3.25X0.85MM_NO_SILK")
      (libsource (lib "eagle-import") (part "M01PTH_SMD_3.25X0.85MM_NO_SILK"))
    )
    (comp (ref "JP1098")
      (value "M01PTH_SMD_3.25X0.85MM_NO_SILK")
      (footprint "eagle-import:1X01_SMD_3.25X0.85MM_NO_SILK")
      (libsource (lib "eagle-import") (part "M01PTH_SMD_3.25X0.85MM_NO_SILK"))
    )
    (comp (ref "JP1099")
      (value "M01PTH_SMD_3.25X0.85MM_NO_SILK")
      (footprint "eagle-import:1X01_SMD_3.25X0.85MM_NO_SILK")
      (libsource (lib "eagle-import") (part "M01PTH_SMD_3.25X0.85MM_NO_SILK"))
    )
    (comp (ref "JP1100")
      (value "M01PTH_SMD_3.25X0.85MM_NO_SILK")
      (footprint "eagle-import:1X01_SMD_3.25X0.85MM_NO_SILK")
      (libsource (lib "eagle-import") (part "M01PTH_SMD_3.25X0.85MM_NO_SILK"))
    )
    (comp (ref "JP1101")
      (value "M01PTH_SMD_3.25X0.85MM_NO_SILK")
      (footprint "eagle-import:1X01_SMD_3.25X0.85MM_NO_SILK")
      (libsource (lib "eagle-import") (part "M01PTH_SMD_3.25X0.85MM_NO_SILK"))
    )
    (comp (ref "JP1102")
      (value "M01PTH_SMD_3.25X0.85MM_NO_SILK")
      (footprint "eagle-import:1X01_SMD_3.25X0.85MM_NO_SILK")
      (libsource (lib "eagle-import") (part "M01PTH_SMD_3.25X0.85MM_NO_SILK"))
    )
    (comp (ref "JP1103")
      (value "M01PTH_SMD_3.25X0.85MM_NO_SILK")
      (footprint "eagle-import:1X01_SMD_3.25X0.85MM_NO_SILK")
      (libsource (lib "eagle-import") (part "M01PTH_SMD_3.25X0.85MM_NO_SILK"))
    )
    (comp (ref "JP1104")
      (value "M01PTH_SMD_3.25X0.85MM_NO_SILK")
      (footprint "eagle-import:1X01_SMD_3.25X0.85MM_NO_SILK")
      (libsource (lib "eagle-import") (part "M01PTH_SMD_3.25X0.85MM_NO_SILK"))
    )
    (comp (ref "JP1105")
      (value "M01PTH_SMD_3.25X0.85MM_NO_SILK")
      (footprint "eagle-import:1X01_SMD_3.25X0.85MM_NO_SILK")
      (libsource (lib "eagle-import") (part "M01PTH_SMD_3.25X0.85MM_NO_SILK"))
    )
    (comp (ref "JP1106")
      (value "M01PTH_SMD_3.25X0.85MM_NO_SILK")
      (footprint "eagle-import:1X01_SMD_3.25X0.85MM_NO_SILK")
      (libsource (lib "eagle-import") (part "M01PTH_SMD_3.25X0.85MM_NO_SILK"))
    )
    (comp (ref "JP1107")
      (value "M01PTH_SMD_3.25X0.85MM_NO_SILK")
      (footprint "eagle-import:1X01_SMD_3.25X0.85MM_NO_SILK")
      (libsource (lib "eagle-import") (part "M01PTH_SMD_3.25X0.85MM_NO_SILK"))
    )
    (comp (ref "JP1108")
      (value "M01PTH_SMD_3.25X0.85MM_NO_SILK")
      (footprint "eagle-import:1X01_SMD_3.25X0.85MM_NO_SILK")
      (libsource (lib "eagle-import") (part "M01PTH_SMD_3.25X0.85MM_NO_SILK"))
    )
    (comp (ref "JP1109")
      (value "M01PTH_SMD_3.25X0.85MM_NO_SILK")
      (footprint "eagle-import:1X01_SMD_3.25X0.85MM_NO_SILK")
      (libsource (lib "eagle-import") (part "M01PTH_SMD_3.25X0.85MM_NO_SILK"))
    )
    (comp (ref "JP1110")
      (value "M01PTH_SMD_3.25X0.85MM_NO_SILK")
      (footprint "eagle-import:1X01_SMD_3.25X0.85MM_NO_SILK")
      (libsource (lib "eagle-import") (part "M01PTH_SMD_3.25X0.85MM_NO_SILK"))
    )
    (comp (ref "JP1111")
      (value "M01PTH_SMD_3.25X0.85MM_NO_SILK")
      (footprint "eagle-import:1X01_SMD_3.25X0.85MM_NO_SILK")
      (libsource (lib "eagle-import") (part "M01PTH_SMD_3.25X0.85MM_NO_SILK"))
    )
    (comp (ref "JP1112")
      (value "M01PTH_SMD_3.25X0.85MM_NO_SILK")
      (footprint "eagle-import:1X01_SMD_3.25X0.85MM_NO_SILK")
      (libsource (lib "eagle-import") (part "M01PTH_SMD_3.25X0.85MM_NO_SILK"))
    )
    (comp (ref "JP1113")
      (value "M01PTH_SMD_3.25X0.85MM_NO_SILK")
      (footprint "eagle-import:1X01_SMD_3.25X0.85MM_NO_SILK")
      (libsource (lib "eagle-import") (part "M01PTH_SMD_3.25X0.85MM_NO_SILK"))
    )
    (comp (ref "JP1114")
      (value "M01PTH_SMD_3.25X0.85MM_NO_SILK")
      (footprint "eagle-import:1X01_SMD_3.25X0.85MM_NO_SILK")
      (libsource (lib "eagle-import") (part "M01PTH_SMD_3.25X0.85MM_NO_SILK"))
    )
    (comp (ref "JP1115")
      (value "M01PTH_SMD_3.25X0.85MM_NO_SILK")
      (footprint "eagle-import:1X01_SMD_3.25X0.85MM_NO_SILK")
      (libsource (lib "eagle-import") (part "M01PTH_SMD_3.25X0.85MM_NO_SILK"))
    )
    (comp (ref "JP1116")
      (value "M01PTH_SMD_3.25X0.85MM_NO_SILK")
      (footprint "eagle-import:1X01_SMD_3.25X0.85MM_NO_SILK")
      (libsource (lib "eagle-import") (part "M01PTH_SMD_3.25X0.85MM_NO_SILK"))
    )
    (comp (ref "JP1117")
      (value "M01PTH_SMD_3.25X0.85MM_NO_SILK")
      (footprint "eagle-import:1X01_SMD_3.25X0.85MM_NO_SILK")
      (libsource (lib "eagle-import") (part "M01PTH_SMD_3.25X0.85MM_NO_SILK"))
    )
    (comp (ref "JP1118")
      (value "M01PTH_SMD_3.25X0.85MM_NO_SILK")
      (footprint "eagle-import:1X01_SMD_3.25X0.85MM_NO_SILK")
      (libsource (lib "eagle-import") (part "M01PTH_SMD_3.25X0.85MM_NO_SILK"))
    )
    (comp (ref "JP1119")
      (value "M01PTH_SMD_3.25X0.85MM_NO_SILK")
      (footprint "eagle-import:1X01_SMD_3.25X0.85MM_NO_SILK")
      (libsource (lib "eagle-import") (part "M01PTH_SMD_3.25X0.85MM_NO_SILK"))
    )
    (comp (ref "JP1120")
      (value "M01PTH_SMD_3.25X0.85MM_NO_SILK")
      (footprint "eagle-import:1X01_SMD_3.25X0.85MM_NO_SILK")
      (libsource (lib "eagle-import") (part "M01PTH_SMD_3.25X0.85MM_NO_SILK"))
    )
    (comp (ref "JP1121")
      (value "M01PTH_SMD_3.25X0.85MM_NO_SILK")
      (footprint "eagle-import:1X01_SMD_3.25X0.85MM_NO_SILK")
      (libsource (lib "eagle-import") (part "M01PTH_SMD_3.25X0.85MM_NO_SILK"))
    )
    (comp (ref "JP1122")
      (value "M01PTH_SMD_3.25X0.85MM_NO_SILK")
      (footprint "eagle-import:1X01_SMD_3.25X0.85MM_NO_SILK")
      (libsource (lib "eagle-import") (part "M01PTH_SMD_3.25X0.85MM_NO_SILK"))
    )
    (comp (ref "JP1123")
      (value "M01PTH_SMD_3.25X0.85MM_NO_SILK")
      (footprint "eagle-import:1X01_SMD_3.25X0.85MM_NO_SILK")
      (libsource (lib "eagle-import") (part "M01PTH_SMD_3.25X0.85MM_NO_SILK"))
    )
    (comp (ref "JP1124")
      (value "M01PTH_SMD_3.25X0.85MM_NO_SILK")
      (footprint "eagle-import:1X01_SMD_3.25X0.85MM_NO_SILK")
      (libsource (lib "eagle-import") (part "M01PTH_SMD_3.25X0.85MM_NO_SILK"))
    )
    (comp (ref "JP1125")
      (value "M01PTH_SMD_3.25X0.85MM_NO_SILK")
      (footprint "eagle-import:1X01_SMD_3.25X0.85MM_NO_SILK")
      (libsource (lib "eagle-import") (part "M01PTH_SMD_3.25X0.85MM_NO_SILK"))
    )
    (comp (ref "JP1126")
      (value "M01PTH_SMD_3.25X0.85MM_NO_SILK")
      (footprint "eagle-import:1X01_SMD_3.25X0.85MM_NO_SILK")
      (libsource (lib "eagle-import") (part "M01PTH_SMD_3.25X0.85MM_NO_SILK"))
    )
    (comp (ref "JP1127")
      (value "M01PTH_SMD_3.25X0.85MM_NO_SILK")
      (footprint "eagle-import:1X01_SMD_3.25X0.85MM_NO_SILK")
      (libsource (lib "eagle-import") (part "M01PTH_SMD_3.25X0.85MM_NO_SILK"))
    )
    (comp (ref "JP1128")
      (value "M01PTH_SMD_3.25X0.85MM_NO_SILK")
      (footprint "eagle-import:1X01_SMD_3.25X0.85MM_NO_SILK")
      (libsource (lib "eagle-import") (part "M01PTH_SMD_3.25X0.85MM_NO_SILK"))
    )
    (comp (ref "JP1129")
      (value "M01PTH_SMD_3.25X0.85MM_NO_SILK")
      (footprint "eagle-import:1X01_SMD_3.25X0.85MM_NO_SILK")
      (libsource (lib "eagle-import") (part "M01PTH_SMD_3.25X0.85MM_NO_SILK"))
    )
    (comp (ref "JP1130")
      (value "M01PTH_SMD_3.25X0.85MM_NO_SILK")
      (footprint "eagle-import:1X01_SMD_3.25X0.85MM_NO_SILK")
      (libsource (lib "eagle-import") (part "M01PTH_SMD_3.25X0.85MM_NO_SILK"))
    )
    (comp (ref "JP1131")
      (value "M01PTH_SMD_3.25X0.85MM_NO_SILK")
      (footprint "eagle-import:1X01_SMD_3.25X0.85MM_NO_SILK")
      (libsource (lib "eagle-import") (part "M01PTH_SMD_3.25X0.85MM_NO_SILK"))
    )
    (comp (ref "JP1132")
      (value "M01PTH_SMD_3.25X0.85MM_NO_SILK")
      (footprint "eagle-import:1X01_SMD_3.25X0.85MM_NO_SILK")
      (libsource (lib "eagle-import") (part "M01PTH_SMD_3.25X0.85MM_NO_SILK"))
    )
    (comp (ref "JP1133")
      (value "M01PTH_SMD_3.25X0.85MM_NO_SILK")
      (footprint "eagle-import:1X01_SMD_3.25X0.85MM_NO_SILK")
      (libsource (lib "eagle-import") (part "M01PTH_SMD_3.25X0.85MM_NO_SILK"))
    )
    (comp (ref "JP1134")
      (value "M01PTH_SMD_3.25X0.85MM_NO_SILK")
      (footprint "eagle-import:1X01_SMD_3.25X0.85MM_NO_SILK")
      (libsource (lib "eagle-import") (part "M01PTH_SMD_3.25X0.85MM_NO_SILK"))
    )
    (comp (ref "JP1135")
      (value "M01PTH_SMD_3.25X0.85MM_NO_SILK")
      (footprint "eagle-import:1X01_SMD_3.25X0.85MM_NO_SILK")
      (libsource (lib "eagle-import") (part "M01PTH_SMD_3.25X0.85MM_NO_SILK"))
    )
    (comp (ref "JP1136")
      (value "M01PTH_SMD_3.25X0.85MM_NO_SILK")
      (footprint "eagle-import:1X01_SMD_3.25X0.85MM_NO_SILK")
      (libsource (lib "eagle-import") (part "M01PTH_SMD_3.25X0.85MM_NO_SILK"))
    )
    (comp (ref "JP1137")
      (value "M01PTH_SMD_3.25X0.85MM_NO_SILK")
      (footprint "eagle-import:1X01_SMD_3.25X0.85MM_NO_SILK")
      (libsource (lib "eagle-import") (part "M01PTH_SMD_3.25X0.85MM_NO_SILK"))
    )
    (comp (ref "JP1138")
      (value "M01PTH_SMD_3.25X0.85MM_NO_SILK")
      (footprint "eagle-import:1X01_SMD_3.25X0.85MM_NO_SILK")
      (libsource (lib "eagle-import") (part "M01PTH_SMD_3.25X0.85MM_NO_SILK"))
    )
    (comp (ref "JP1139")
      (value "M01PTH_SMD_3.25X0.85MM_NO_SILK")
      (footprint "eagle-import:1X01_SMD_3.25X0.85MM_NO_SILK")
      (libsource (lib "eagle-import") (part "M01PTH_SMD_3.25X0.85MM_NO_SILK"))
    )
    (comp (ref "JP1140")
      (value "M01PTH_SMD_3.25X0.85MM_NO_SILK")
      (footprint "eagle-import:1X01_SMD_3.25X0.85MM_NO_SILK")
      (libsource (lib "eagle-import") (part "M01PTH_SMD_3.25X0.85MM_NO_SILK"))
    )
    (comp (ref "JP1141")
      (value "M01PTH_SMD_3.25X0.85MM_NO_SILK")
      (footprint "eagle-import:1X01_SMD_3.25X0.85MM_NO_SILK")
      (libsource (lib "eagle-import") (part "M01PTH_SMD_3.25X0.85MM_NO_SILK"))
    )
    (comp (ref "JP1142")
      (value "M01PTH_SMD_3.25X0.85MM_NO_SILK")
      (footprint "eagle-import:1X01_SMD_3.25X0.85MM_NO_SILK")
      (libsource (lib "eagle-import") (part "M01PTH_SMD_3.25X0.85MM_NO_SILK"))
    )
    (comp (ref "JP1143")
      (value "M01PTH_SMD_3.25X0.85MM_NO_SILK")
      (footprint "eagle-import:1X01_SMD_3.25X0.85MM_NO_SILK")
      (libsource (lib "eagle-import") (part "M01PTH_SMD_3.25X0.85MM_NO_SILK"))
    )
    (comp (ref "JP1144")
      (value "M01PTH_SMD_3.25X0.85MM_NO_SILK")
      (footprint "eagle-import:1X01_SMD_3.25X0.85MM_NO_SILK")
      (libsource (lib "eagle-import") (part "M01PTH_SMD_3.25X0.85MM_NO_SILK"))
    )
    (comp (ref "JP1145")
      (value "M01PTH_SMD_3.25X0.85MM_NO_SILK")
      (footprint "eagle-import:1X01_SMD_3.25X0.85MM_NO_SILK")
      (libsource (lib "eagle-import") (part "M01PTH_SMD_3.25X0.85MM_NO_SILK"))
    )
    (comp (ref "JP1146")
      (value "M01PTH_SMD_3.25X0.85MM_NO_SILK")
      (footprint "eagle-import:1X01_SMD_3.25X0.85MM_NO_SILK")
      (libsource (lib "eagle-import") (part "M01PTH_SMD_3.25X0.85MM_NO_SILK"))
    )
    (comp (ref "JP1147")
      (value "M01PTH_SMD_3.25X0.85MM_NO_SILK")
      (footprint "eagle-import:1X01_SMD_3.25X0.85MM_NO_SILK")
      (libsource (lib "eagle-import") (part "M01PTH_SMD_3.25X0.85MM_NO_SILK"))
    )
    (comp (ref "JP1148")
      (value "M01PTH_SMD_3.25X0.85MM_NO_SILK")
      (footprint "eagle-import:1X01_SMD_3.25X0.85MM_NO_SILK")
      (libsource (lib "eagle-import") (part "M01PTH_SMD_3.25X0.85MM_NO_SILK"))
    )
    (comp (ref "JP1149")
      (value "M01PTH_SMD_3.25X0.85MM_NO_SILK")
      (footprint "eagle-import:1X01_SMD_3.25X0.85MM_NO_SILK")
      (libsource (lib "eagle-import") (part "M01PTH_SMD_3.25X0.85MM_NO_SILK"))
    )
    (comp (ref "JP1150")
      (value "M01PTH_SMD_3.25X0.85MM_NO_SILK")
      (footprint "eagle-import:1X01_SMD_3.25X0.85MM_NO_SILK")
      (libsource (lib "eagle-import") (part "M01PTH_SMD_3.25X0.85MM_NO_SILK"))
    )
    (comp (ref "JP1151")
      (value "M01PTH_SMD_3.25X0.85MM_NO_SILK")
      (footprint "eagle-import:1X01_SMD_3.25X0.85MM_NO_SILK")
      (libsource (lib "eagle-import") (part "M01PTH_SMD_3.25X0.85MM_NO_SILK"))
    )
    (comp (ref "JP1152")
      (value "M01PTH_SMD_3.25X0.85MM_NO_SILK")
      (footprint "eagle-import:1X01_SMD_3.25X0.85MM_NO_SILK")
      (libsource (lib "eagle-import") (part "M01PTH_SMD_3.25X0.85MM_NO_SILK"))
    )
    (comp (ref "JP1153")
      (value "M01PTH_SMD_3.25X0.85MM_NO_SILK")
      (footprint "eagle-import:1X01_SMD_3.25X0.85MM_NO_SILK")
      (libsource (lib "eagle-import") (part "M01PTH_SMD_3.25X0.85MM_NO_SILK"))
    )
    (comp (ref "JP1154")
      (value "M01PTH_SMD_3.25X0.85MM_NO_SILK")
      (footprint "eagle-import:1X01_SMD_3.25X0.85MM_NO_SILK")
      (libsource (lib "eagle-import") (part "M01PTH_SMD_3.25X0.85MM_NO_SILK"))
    )
    (comp (ref "JP1155")
      (value "M01PTH_SMD_3.25X0.85MM_NO_SILK")
      (footprint "eagle-import:1X01_SMD_3.25X0.85MM_NO_SILK")
      (libsource (lib "eagle-import") (part "M01PTH_SMD_3.25X0.85MM_NO_SILK"))
    )
    (comp (ref "JP1156")
      (value "M01PTH_SMD_3.25X0.85MM_NO_SILK")
      (footprint "eagle-import:1X01_SMD_3.25X0.85MM_NO_SILK")
      (libsource (lib "eagle-import") (part "M01PTH_SMD_3.25X0.85MM_NO_SILK"))
    )
    (comp (ref "JP1157")
      (value "M01PTH_SMD_3.25X0.85MM_NO_SILK")
      (footprint "eagle-import:1X01_SMD_3.25X0.85MM_NO_SILK")
      (libsource (lib "eagle-import") (part "M01PTH_SMD_3.25X0.85MM_NO_SILK"))
    )
    (comp (ref "JP1158")
      (value "M01PTH_SMD_3.25X0.85MM_NO_SILK")
      (footprint "eagle-import:1X01_SMD_3.25X0.85MM_NO_SILK")
      (libsource (lib "eagle-import") (part "M01PTH_SMD_3.25X0.85MM_NO_SILK"))
    )
    (comp (ref "JP1159")
      (value "M01PTH_SMD_3.25X0.85MM_NO_SILK")
      (footprint "eagle-import:1X01_SMD_3.25X0.85MM_NO_SILK")
      (libsource (lib "eagle-import") (part "M01PTH_SMD_3.25X0.85MM_NO_SILK"))
    )
    (comp (ref "JP1160")
      (value "M01PTH_SMD_3.25X0.85MM_NO_SILK")
      (footprint "eagle-import:1X01_SMD_3.25X0.85MM_NO_SILK")
      (libsource (lib "eagle-import") (part "M01PTH_SMD_3.25X0.85MM_NO_SILK"))
    )
    (comp (ref "JP1161")
      (value "M01PTH_SMD_3.25X0.85MM_NO_SILK")
      (footprint "eagle-import:1X01_SMD_3.25X0.85MM_NO_SILK")
      (libsource (lib "eagle-import") (part "M01PTH_SMD_3.25X0.85MM_NO_SILK"))
    )
    (comp (ref "JP1162")
      (value "M01PTH_SMD_3.25X0.85MM_NO_SILK")
      (footprint "eagle-import:1X01_SMD_3.25X0.85MM_NO_SILK")
      (libsource (lib "eagle-import") (part "M01PTH_SMD_3.25X0.85MM_NO_SILK"))
    )
    (comp (ref "JP1163")
      (value "M01PTH_SMD_3.25X0.85MM_NO_SILK")
      (footprint "eagle-import:1X01_SMD_3.25X0.85MM_NO_SILK")
      (libsource (lib "eagle-import") (part "M01PTH_SMD_3.25X0.85MM_NO_SILK"))
    )
    (comp (ref "JP1164")
      (value "M01PTH_SMD_3.25X0.85MM_NO_SILK")
      (footprint "eagle-import:1X01_SMD_3.25X0.85MM_NO_SILK")
      (libsource (lib "eagle-import") (part "M01PTH_SMD_3.25X0.85MM_NO_SILK"))
    )
    (comp (ref "JP1165")
      (value "M01PTH_SMD_3.25X0.85MM_NO_SILK")
      (footprint "eagle-import:1X01_SMD_3.25X0.85MM_NO_SILK")
      (libsource (lib "eagle-import") (part "M01PTH_SMD_3.25X0.85MM_NO_SILK"))
    )
    (comp (ref "JP1166")
      (value "M01PTH_SMD_3.25X0.85MM_NO_SILK")
      (footprint "eagle-import:1X01_SMD_3.25X0.85MM_NO_SILK")
      (libsource (lib "eagle-import") (part "M01PTH_SMD_3.25X0.85MM_NO_SILK"))
    )
    (comp (ref "JP1167")
      (value "M01PTH_SMD_3.25X0.85MM_NO_SILK")
      (footprint "eagle-import:1X01_SMD_3.25X0.85MM_NO_SILK")
      (libsource (lib "eagle-import") (part "M01PTH_SMD_3.25X0.85MM_NO_SILK"))
    )
    (comp (ref "JP1168")
      (value "M01PTH_SMD_3.25X0.85MM_NO_SILK")
      (footprint "eagle-import:1X01_SMD_3.25X0.85MM_NO_SILK")
      (libsource (lib "eagle-import") (part "M01PTH_SMD_3.25X0.85MM_NO_SILK"))
    )
    (comp (ref "JP1169")
      (value "M01PTH_SMD_3.25X0.85MM_NO_SILK")
      (footprint "eagle-import:1X01_SMD_3.25X0.85MM_NO_SILK")
      (libsource (lib "eagle-import") (part "M01PTH_SMD_3.25X0.85MM_NO_SILK"))
    )
    (comp (ref "JP1170")
      (value "M01PTH_SMD_3.25X0.85MM_NO_SILK")
      (footprint "eagle-import:1X01_SMD_3.25X0.85MM_NO_SILK")
      (libsource (lib "eagle-import") (part "M01PTH_SMD_3.25X0.85MM_NO_SILK"))
    )
    (comp (ref "JP1171")
      (value "M01PTH_SMD_3.25X0.85MM_NO_SILK")
      (footprint "eagle-import:1X01_SMD_3.25X0.85MM_NO_SILK")
      (libsource (lib "eagle-import") (part "M01PTH_SMD_3.25X0.85MM_NO_SILK"))
    )
    (comp (ref "JP1172")
      (value "M01PTH_SMD_3.25X0.85MM_NO_SILK")
      (footprint "eagle-import:1X01_SMD_3.25X0.85MM_NO_SILK")
      (libsource (lib "eagle-import") (part "M01PTH_SMD_3.25X0.85MM_NO_SILK"))
    )
    (comp (ref "JP1173")
      (value "M01PTH_SMD_3.25X0.85MM_NO_SILK")
      (footprint "eagle-import:1X01_SMD_3.25X0.85MM_NO_SILK")
      (libsource (lib "eagle-import") (part "M01PTH_SMD_3.25X0.85MM_NO_SILK"))
    )
    (comp (ref "JP1174")
      (value "M01PTH_SMD_3.25X0.85MM_NO_SILK")
      (footprint "eagle-import:1X01_SMD_3.25X0.85MM_NO_SILK")
      (libsource (lib "eagle-import") (part "M01PTH_SMD_3.25X0.85MM_NO_SILK"))
    )
    (comp (ref "JP1175")
      (value "M01PTH_SMD_3.25X0.85MM_NO_SILK")
      (footprint "eagle-import:1X01_SMD_3.25X0.85MM_NO_SILK")
      (libsource (lib "eagle-import") (part "M01PTH_SMD_3.25X0.85MM_NO_SILK"))
    )
    (comp (ref "JP1176")
      (value "M01PTH_SMD_3.25X0.85MM_NO_SILK")
      (footprint "eagle-import:1X01_SMD_3.25X0.85MM_NO_SILK")
      (libsource (lib "eagle-import") (part "M01PTH_SMD_3.25X0.85MM_NO_SILK"))
    )
    (comp (ref "JP1177")
      (value "M01PTH_SMD_3.25X0.85MM_NO_SILK")
      (footprint "eagle-import:1X01_SMD_3.25X0.85MM_NO_SILK")
      (libsource (lib "eagle-import") (part "M01PTH_SMD_3.25X0.85MM_NO_SILK"))
    )
    (comp (ref "JP1178")
      (value "M01PTH_SMD_3.25X0.85MM_NO_SILK")
      (footprint "eagle-import:1X01_SMD_3.25X0.85MM_NO_SILK")
      (libsource (lib "eagle-import") (part "M01PTH_SMD_3.25X0.85MM_NO_SILK"))
    )
    (comp (ref "JP1179")
      (value "M01PTH_SMD_3.25X0.85MM_NO_SILK")
      (footprint "eagle-import:1X01_SMD_3.25X0.85MM_NO_SILK")
      (libsource (lib "eagle-import") (part "M01PTH_SMD_3.25X0.85MM_NO_SILK"))
    )
    (comp (ref "JP1180")
      (value "M01PTH_SMD_3.25X0.85MM_NO_SILK")
      (footprint "eagle-import:1X01_SMD_3.25X0.85MM_NO_SILK")
      (libsource (lib "eagle-import") (part "M01PTH_SMD_3.25X0.85MM_NO_SILK"))
    )
    (comp (ref "JP1181")
      (value "M01PTH_SMD_3.25X0.85MM_NO_SILK")
      (footprint "eagle-import:1X01_SMD_3.25X0.85MM_NO_SILK")
      (libsource (lib "eagle-import") (part "M01PTH_SMD_3.25X0.85MM_NO_SILK"))
    )
    (comp (ref "JP1182")
      (value "M01PTH_SMD_3.25X0.85MM_NO_SILK")
      (footprint "eagle-import:1X01_SMD_3.25X0.85MM_NO_SILK")
      (libsource (lib "eagle-import") (part "M01PTH_SMD_3.25X0.85MM_NO_SILK"))
    )
    (comp (ref "JP1183")
      (value "M01PTH_SMD_3.25X0.85MM_NO_SILK")
      (footprint "eagle-import:1X01_SMD_3.25X0.85MM_NO_SILK")
      (libsource (lib "eagle-import") (part "M01PTH_SMD_3.25X0.85MM_NO_SILK"))
    )
    (comp (ref "JP1184")
      (value "M01PTH_SMD_3.25X0.85MM_NO_SILK")
      (footprint "eagle-import:1X01_SMD_3.25X0.85MM_NO_SILK")
      (libsource (lib "eagle-import") (part "M01PTH_SMD_3.25X0.85MM_NO_SILK"))
    )
    (comp (ref "JP1185")
      (value "M01PTH_SMD_3.25X0.85MM_NO_SILK")
      (footprint "eagle-import:1X01_SMD_3.25X0.85MM_NO_SILK")
      (libsource (lib "eagle-import") (part "M01PTH_SMD_3.25X0.85MM_NO_SILK"))
    )
    (comp (ref "JP1186")
      (value "M01PTH_SMD_3.25X0.85MM_NO_SILK")
      (footprint "eagle-import:1X01_SMD_3.25X0.85MM_NO_SILK")
      (libsource (lib "eagle-import") (part "M01PTH_SMD_3.25X0.85MM_NO_SILK"))
    )
    (comp (ref "JP1187")
      (value "M01PTH_SMD_3.25X0.85MM_NO_SILK")
      (footprint "eagle-import:1X01_SMD_3.25X0.85MM_NO_SILK")
      (libsource (lib "eagle-import") (part "M01PTH_SMD_3.25X0.85MM_NO_SILK"))
    )
    (comp (ref "JP1188")
      (value "M01PTH_SMD_3.25X0.85MM_NO_SILK")
      (footprint "eagle-import:1X01_SMD_3.25X0.85MM_NO_SILK")
      (libsource (lib "eagle-import") (part "M01PTH_SMD_3.25X0.85MM_NO_SILK"))
    )
    (comp (ref "JP1189")
      (value "M01PTH_SMD_3.25X0.85MM_NO_SILK")
      (footprint "eagle-import:1X01_SMD_3.25X0.85MM_NO_SILK")
      (libsource (lib "eagle-import") (part "M01PTH_SMD_3.25X0.85MM_NO_SILK"))
    )
    (comp (ref "JP1190")
      (value "M01PTH_SMD_3.25X0.85MM_NO_SILK")
      (footprint "eagle-import:1X01_SMD_3.25X0.85MM_NO_SILK")
      (libsource (lib "eagle-import") (part "M01PTH_SMD_3.25X0.85MM_NO_SILK"))
    )
    (comp (ref "JP1191")
      (value "M01PTH_SMD_3.25X0.85MM_NO_SILK")
      (footprint "eagle-import:1X01_SMD_3.25X0.85MM_NO_SILK")
      (libsource (lib "eagle-import") (part "M01PTH_SMD_3.25X0.85MM_NO_SILK"))
    )
    (comp (ref "JP1192")
      (value "M01PTH_SMD_3.25X0.85MM_NO_SILK")
      (footprint "eagle-import:1X01_SMD_3.25X0.85MM_NO_SILK")
      (libsource (lib "eagle-import") (part "M01PTH_SMD_3.25X0.85MM_NO_SILK"))
    )
    (comp (ref "JP1193")
      (value "M01PTH_SMD_3.25X0.85MM_NO_SILK")
      (footprint "eagle-import:1X01_SMD_3.25X0.85MM_NO_SILK")
      (libsource (lib "eagle-import") (part "M01PTH_SMD_3.25X0.85MM_NO_SILK"))
    )
    (comp (ref "JP1194")
      (value "M01PTH_SMD_3.25X0.85MM_NO_SILK")
      (footprint "eagle-import:1X01_SMD_3.25X0.85MM_NO_SILK")
      (libsource (lib "eagle-import") (part "M01PTH_SMD_3.25X0.85MM_NO_SILK"))
    )
    (comp (ref "JP1195")
      (value "M01PTH_SMD_3.25X0.85MM_NO_SILK")
      (footprint "eagle-import:1X01_SMD_3.25X0.85MM_NO_SILK")
      (libsource (lib "eagle-import") (part "M01PTH_SMD_3.25X0.85MM_NO_SILK"))
    )
    (comp (ref "JP1196")
      (value "M01PTH_SMD_3.25X0.85MM_NO_SILK")
      (footprint "eagle-import:1X01_SMD_3.25X0.85MM_NO_SILK")
      (libsource (lib "eagle-import") (part "M01PTH_SMD_3.25X0.85MM_NO_SILK"))
    )
    (comp (ref "JP1197")
      (value "M01PTH_SMD_3.25X0.85MM_NO_SILK")
      (footprint "eagle-import:1X01_SMD_3.25X0.85MM_NO_SILK")
      (libsource (lib "eagle-import") (part "M01PTH_SMD_3.25X0.85MM_NO_SILK"))
    )
    (comp (ref "JP1198")
      (value "M01PTH_SMD_3.25X0.85MM_NO_SILK")
      (footprint "eagle-import:1X01_SMD_3.25X0.85MM_NO_SILK")
      (libsource (lib "eagle-import") (part "M01PTH_SMD_3.25X0.85MM_NO_SILK"))
    )
    (comp (ref "JP1199")
      (value "M01PTH_SMD_3.25X0.85MM_NO_SILK")
      (footprint "eagle-import:1X01_SMD_3.25X0.85MM_NO_SILK")
      (libsource (lib "eagle-import") (part "M01PTH_SMD_3.25X0.85MM_NO_SILK"))
    )
    (comp (ref "JP1200")
      (value "M01PTH_SMD_3.25X0.85MM_NO_SILK")
      (footprint "eagle-import:1X01_SMD_3.25X0.85MM_NO_SILK")
      (libsource (lib "eagle-import") (part "M01PTH_SMD_3.25X0.85MM_NO_SILK"))
    )
  )
  (nets
    (net (code "1") (name "/0_1440304149") (class "Default")
      (node (ref "JP1") (pin "1") (pinfunction "1_1") (pintype "passive"))
      (node (ref "JP961") (pin "P$1") (pinfunction "1_P$1") (pintype "passive"))
    )
    (net (code "2") (name "/0_1440304208") (class "Default")
      (node (ref "JP1159") (pin "P$1") (pinfunction "1_P$1") (pintype "passive"))
      (node (ref "JP5") (pin "1") (pinfunction "1_1") (pintype "passive"))
    )
    (net (code "3") (name "/1_1440304149") (class "Default")
      (node (ref "JP11") (pin "1") (pinfunction "1_1") (pintype "passive"))
      (node (ref "JP963") (pin "P$1") (pinfunction "1_P$1") (pintype "passive"))
    )
    (net (code "4") (name "/1_1440304208") (class "Default")
      (node (ref "JP1160") (pin "P$1") (pinfunction "1_P$1") (pintype "passive"))
      (node (ref "JP15") (pin "1") (pinfunction "1_1") (pintype "passive"))
    )
    (net (code "5") (name "/2_1440304149") (class "Default")
      (node (ref "JP21") (pin "1") (pinfunction "1_1") (pintype "passive"))
      (node (ref "JP965") (pin "P$1") (pinfunction "1_P$1") (pintype "passive"))
    )
    (net (code "6") (name "/2_1440304208") (class "Default")
      (node (ref "JP1171") (pin "P$1") (pinfunction "1_P$1") (pintype "passive"))
      (node (ref "JP6") (pin "1") (pinfunction "1_1") (pintype "passive"))
    )
    (net (code "7") (name "/3_1440304149") (class "Default")
      (node (ref "JP31") (pin "1") (pinfunction "1_1") (pintype "passive"))
      (node (ref "JP967") (pin "P$1") (pinfunction "1_P$1") (pintype "passive"))
    )
    (net (code "8") (name "/3_1440304208") (class "Default")
      (node (ref "JP1172") (pin "P$1") (pinfunction "1_P$1") (pintype "passive"))
      (node (ref "JP16") (pin "1") (pinfunction "1_1") (pintype "passive"))
    )
    (net (code "9") (name "/4_1440304149") (class "Default")
      (node (ref "JP41") (pin "1") (pinfunction "1_1") (pintype "passive"))
      (node (ref "JP969") (pin "P$1") (pinfunction "1_P$1") (pintype "passive"))
    )
    (net (code "10") (name "/4_1440304208") (class "Default")
      (node (ref "JP1173") (pin "P$1") (pinfunction "1_P$1") (pintype "passive"))
      (node (ref "JP26") (pin "1") (pinfunction "1_1") (pintype "passive"))
    )
    (net (code "11") (name "/5_1440304149") (class "Default")
      (node (ref "JP51") (pin "1") (pinfunction "1_1") (pintype "passive"))
      (node (ref "JP971") (pin "P$1") (pinfunction "1_P$1") (pintype "passive"))
    )
    (net (code "12") (name "/5_1440304208") (class "Default")
      (node (ref "JP1174") (pin "P$1") (pinfunction "1_P$1") (pintype "passive"))
      (node (ref "JP36") (pin "1") (pinfunction "1_1") (pintype "passive"))
    )
    (net (code "13") (name "/6_1440304149") (class "Default")
      (node (ref "JP61") (pin "1") (pinfunction "1_1") (pintype "passive"))
      (node (ref "JP973") (pin "P$1") (pinfunction "1_P$1") (pintype "passive"))
    )
    (net (code "14") (name "/6_1440304208") (class "Default")
      (node (ref "JP1175") (pin "P$1") (pinfunction "1_P$1") (pintype "passive"))
      (node (ref "JP46") (pin "1") (pinfunction "1_1") (pintype "passive"))
    )
    (net (code "15") (name "/7_1440304149") (class "Default")
      (node (ref "JP71") (pin "1") (pinfunction "1_1") (pintype "passive"))
      (node (ref "JP975") (pin "P$1") (pinfunction "1_P$1") (pintype "passive"))
    )
    (net (code "16") (name "/7_1440304208") (class "Default")
      (node (ref "JP1176") (pin "P$1") (pinfunction "1_P$1") (pintype "passive"))
      (node (ref "JP56") (pin "1") (pinfunction "1_1") (pintype "passive"))
    )
    (net (code "17") (name "/8_1440304149") (class "Default")
      (node (ref "JP81") (pin "1") (pinfunction "1_1") (pintype "passive"))
      (node (ref "JP977") (pin "P$1") (pinfunction "1_P$1") (pintype "passive"))
    )
    (net (code "18") (name "/8_1440304208") (class "Default")
      (node (ref "JP1189") (pin "P$1") (pinfunction "1_P$1") (pintype "passive"))
      (node (ref "JP295") (pin "1") (pinfunction "1_1") (pintype "passive"))
    )
    (net (code "19") (name "/9_1440304149") (class "Default")
      (node (ref "JP91") (pin "1") (pinfunction "1_1") (pintype "passive"))
      (node (ref "JP979") (pin "P$1") (pinfunction "1_P$1") (pintype "passive"))
    )
    (net (code "20") (name "/9_1440304208") (class "Default")
      (node (ref "JP1190") (pin "P$1") (pinfunction "1_P$1") (pintype "passive"))
      (node (ref "JP285") (pin "1") (pinfunction "1_1") (pintype "passive"))
    )
    (net (code "21") (name "/10_1440304149") (class "Default")
      (node (ref "JP101") (pin "1") (pinfunction "1_1") (pintype "passive"))
      (node (ref "JP981") (pin "P$1") (pinfunction "1_P$1") (pintype "passive"))
    )
    (net (code "22") (name "/10_1440304208") (class "Default")
      (node (ref "JP1191") (pin "P$1") (pinfunction "1_P$1") (pintype "passive"))
      (node (ref "JP296") (pin "1") (pinfunction "1_1") (pintype "passive"))
    )
    (net (code "23") (name "/11_1440304149") (class "Default")
      (node (ref "JP111") (pin "1") (pinfunction "1_1") (pintype "passive"))
      (node (ref "JP983") (pin "P$1") (pinfunction "1_P$1") (pintype "passive"))
    )
    (net (code "24") (name "/11_1440304208") (class "Default")
      (node (ref "JP1192") (pin "P$1") (pinfunction "1_P$1") (pintype "passive"))
      (node (ref "JP286") (pin "1") (pinfunction "1_1") (pintype "passive"))
    )
    (net (code "25") (name "/12_1440304149") (class "Default")
      (node (ref "JP121") (pin "1") (pinfunction "1_1") (pintype "passive"))
      (node (ref "JP985") (pin "P$1") (pinfunction "1_P$1") (pintype "passive"))
    )
    (net (code "26") (name "/12_1440304208") (class "Default")
      (node (ref "JP1193") (pin "P$1") (pinfunction "1_P$1") (pintype "passive"))
      (node (ref "JP276") (pin "1") (pinfunction "1_1") (pintype "passive"))
    )
    (net (code "27") (name "/13_1440304149") (class "Default")
      (node (ref "JP131") (pin "1") (pinfunction "1_1") (pintype "passive"))
      (node (ref "JP987") (pin "P$1") (pinfunction "1_P$1") (pintype "passive"))
    )
    (net (code "28") (name "/13_1440304208") (class "Default")
      (node (ref "JP1194") (pin "P$1") (pinfunction "1_P$1") (pintype "passive"))
      (node (ref "JP266") (pin "1") (pinfunction "1_1") (pintype "passive"))
    )
    (net (code "29") (name "/14_1440304149") (class "Default")
      (node (ref "JP141") (pin "1") (pinfunction "1_1") (pintype "passive"))
      (node (ref "JP989") (pin "P$1") (pinfunction "1_P$1") (pintype "passive"))
    )
    (net (code "30") (name "/14_1440304208") (class "Default")
      (node (ref "JP1195") (pin "P$1") (pinfunction "1_P$1") (pintype "passive"))
      (node (ref "JP256") (pin "1") (pinfunction "1_1") (pintype "passive"))
    )
    (net (code "31") (name "/15_1440304149") (class "Default")
      (node (ref "JP151") (pin "1") (pinfunction "1_1") (pintype "passive"))
      (node (ref "JP991") (pin "P$1") (pinfunction "1_P$1") (pintype "passive"))
    )
    (net (code "32") (name "/15_1440304208") (class "Default")
      (node (ref "JP1158") (pin "P$1") (pinfunction "1_P$1") (pintype "passive"))
      (node (ref "JP25") (pin "1") (pinfunction "1_1") (pintype "passive"))
    )
    (net (code "33") (name "/16_1440304149") (class "Default")
      (node (ref "JP161") (pin "1") (pinfunction "1_1") (pintype "passive"))
      (node (ref "JP993") (pin "P$1") (pinfunction "1_P$1") (pintype "passive"))
    )
    (net (code "34") (name "/16_1440304208") (class "Default")
      (node (ref "JP1177") (pin "P$1") (pinfunction "1_P$1") (pintype "passive"))
      (node (ref "JP66") (pin "1") (pinfunction "1_1") (pintype "passive"))
    )
    (net (code "35") (name "/17_1440304149") (class "Default")
      (node (ref "JP171") (pin "1") (pinfunction "1_1") (pintype "passive"))
      (node (ref "JP995") (pin "P$1") (pinfunction "1_P$1") (pintype "passive"))
    )
    (net (code "36") (name "/17_1440304208") (class "Default")
      (node (ref "JP1188") (pin "P$1") (pinfunction "1_P$1") (pintype "passive"))
      (node (ref "JP275") (pin "1") (pinfunction "1_1") (pintype "passive"))
    )
    (net (code "37") (name "/18_1440304149") (class "Default")
      (node (ref "JP181") (pin "1") (pinfunction "1_1") (pintype "passive"))
      (node (ref "JP997") (pin "P$1") (pinfunction "1_P$1") (pintype "passive"))
    )
    (net (code "38") (name "/18_1440304208") (class "Default")
      (node (ref "JP1196") (pin "P$1") (pinfunction "1_P$1") (pintype "passive"))
      (node (ref "JP246") (pin "1") (pinfunction "1_1") (pintype "passive"))
    )
    (net (code "39") (name "/19_1440304149") (class "Default")
      (node (ref "JP191") (pin "1") (pinfunction "1_1") (pintype "passive"))
      (node (ref "JP999") (pin "P$1") (pinfunction "1_P$1") (pintype "passive"))
    )
    (net (code "40") (name "/19_1440304208") (class "Default")
      (node (ref "JP1157") (pin "P$1") (pinfunction "1_P$1") (pintype "passive"))
      (node (ref "JP35") (pin "1") (pinfunction "1_1") (pintype "passive"))
    )
    (net (code "41") (name "/20_1440304149") (class "Default")
      (node (ref "JP1001") (pin "P$1") (pinfunction "1_P$1") (pintype "passive"))
      (node (ref "JP201") (pin "1") (pinfunction "1_1") (pintype "passive"))
    )
    (net (code "42") (name "/20_1440304208") (class "Default")
      (node (ref "JP1187") (pin "P$1") (pinfunction "1_P$1") (pintype "passive"))
      (node (ref "JP265") (pin "1") (pinfunction "1_1") (pintype "passive"))
    )
    (net (code "43") (name "/21_1440304149") (class "Default")
      (node (ref "JP1003") (pin "P$1") (pinfunction "1_P$1") (pintype "passive"))
      (node (ref "JP211") (pin "1") (pinfunction "1_1") (pintype "passive"))
    )
    (net (code "44") (name "/21_1440304208") (class "Default")
      (node (ref "JP1197") (pin "P$1") (pinfunction "1_P$1") (pintype "passive"))
      (node (ref "JP236") (pin "1") (pinfunction "1_1") (pintype "passive"))
    )
    (net (code "45") (name "/22_1440304149") (class "Default")
      (node (ref "JP1005") (pin "P$1") (pinfunction "1_P$1") (pintype "passive"))
      (node (ref "JP221") (pin "1") (pinfunction "1_1") (pintype "passive"))
    )
    (net (code "46") (name "/22_1440304208") (class "Default")
      (node (ref "JP1156") (pin "P$1") (pinfunction "1_P$1") (pintype "passive"))
      (node (ref "JP45") (pin "1") (pinfunction "1_1") (pintype "passive"))
    )
    (net (code "47") (name "/23_1440304149") (class "Default")
      (node (ref "JP1007") (pin "P$1") (pinfunction "1_P$1") (pintype "passive"))
      (node (ref "JP231") (pin "1") (pinfunction "1_1") (pintype "passive"))
    )
    (net (code "48") (name "/23_1440304208") (class "Default")
      (node (ref "JP1178") (pin "P$1") (pinfunction "1_P$1") (pintype "passive"))
      (node (ref "JP76") (pin "1") (pinfunction "1_1") (pintype "passive"))
    )
    (net (code "49") (name "/24_1440304149") (class "Default")
      (node (ref "JP1009") (pin "P$1") (pinfunction "1_P$1") (pintype "passive"))
      (node (ref "JP241") (pin "1") (pinfunction "1_1") (pintype "passive"))
    )
    (net (code "50") (name "/24_1440304208") (class "Default")
      (node (ref "JP1186") (pin "P$1") (pinfunction "1_P$1") (pintype "passive"))
      (node (ref "JP255") (pin "1") (pinfunction "1_1") (pintype "passive"))
    )
    (net (code "51") (name "/25_1440304149") (class "Default")
      (node (ref "JP1011") (pin "P$1") (pinfunction "1_P$1") (pintype "passive"))
      (node (ref "JP251") (pin "1") (pinfunction "1_1") (pintype "passive"))
    )
    (net (code "52") (name "/25_1440304208") (class "Default")
      (node (ref "JP1198") (pin "P$1") (pinfunction "1_P$1") (pintype "passive"))
      (node (ref "JP226") (pin "1") (pinfunction "1_1") (pintype "passive"))
    )
    (net (code "53") (name "/26_1440304149") (class "Default")
      (node (ref "JP1013") (pin "P$1") (pinfunction "1_P$1") (pintype "passive"))
      (node (ref "JP261") (pin "1") (pinfunction "1_1") (pintype "passive"))
    )
    (net (code "54") (name "/26_1440304208") (class "Default")
      (node (ref "JP1155") (pin "P$1") (pinfunction "1_P$1") (pintype "passive"))
      (node (ref "JP55") (pin "1") (pinfunction "1_1") (pintype "passive"))
    )
    (net (code "55") (name "/27_1440304149") (class "Default")
      (node (ref "JP1015") (pin "P$1") (pinfunction "1_P$1") (pintype "passive"))
      (node (ref "JP271") (pin "1") (pinfunction "1_1") (pintype "passive"))
    )
    (net (code "56") (name "/27_1440304208") (class "Default")
      (node (ref "JP1179") (pin "P$1") (pinfunction "1_P$1") (pintype "passive"))
      (node (ref "JP86") (pin "1") (pinfunction "1_1") (pintype "passive"))
    )
    (net (code "57") (name "/28_1440304149") (class "Default")
      (node (ref "JP1017") (pin "P$1") (pinfunction "1_P$1") (pintype "passive"))
      (node (ref "JP281") (pin "1") (pinfunction "1_1") (pintype "passive"))
    )
    (net (code "58") (name "/28_1440304208") (class "Default")
      (node (ref "JP1185") (pin "P$1") (pinfunction "1_P$1") (pintype "passive"))
      (node (ref "JP245") (pin "1") (pinfunction "1_1") (pintype "passive"))
    )
    (net (code "59") (name "/29_1440304149") (class "Default")
      (node (ref "JP1019") (pin "P$1") (pinfunction "1_P$1") (pintype "passive"))
      (node (ref "JP291") (pin "1") (pinfunction "1_1") (pintype "passive"))
    )
    (net (code "60") (name "/29_1440304208") (class "Default")
      (node (ref "JP1199") (pin "P$1") (pinfunction "1_P$1") (pintype "passive"))
      (node (ref "JP216") (pin "1") (pinfunction "1_1") (pintype "passive"))
    )
    (net (code "61") (name "/30_1440304149") (class "Default")
      (node (ref "JP1020") (pin "P$1") (pinfunction "1_P$1") (pintype "passive"))
      (node (ref "JP292") (pin "1") (pinfunction "1_1") (pintype "passive"))
    )
    (net (code "62") (name "/30_1440304208") (class "Default")
      (node (ref "JP1154") (pin "P$1") (pinfunction "1_P$1") (pintype "passive"))
      (node (ref "JP65") (pin "1") (pinfunction "1_1") (pintype "passive"))
    )
    (net (code "63") (name "/31_1440304149") (class "Default")
      (node (ref "JP10") (pin "1") (pinfunction "1_1") (pintype "passive"))
      (node (ref "JP1021") (pin "P$1") (pinfunction "1_P$1") (pintype "passive"))
    )
    (net (code "64") (name "/31_1440304208") (class "Default")
      (node (ref "JP1180") (pin "P$1") (pinfunction "1_P$1") (pintype "passive"))
      (node (ref "JP96") (pin "1") (pinfunction "1_1") (pintype "passive"))
    )
    (net (code "65") (name "/32_1440304149") (class "Default")
      (node (ref "JP1023") (pin "P$1") (pinfunction "1_P$1") (pintype "passive"))
      (node (ref "JP20") (pin "1") (pinfunction "1_1") (pintype "passive"))
    )
    (net (code "66") (name "/32_1440304208") (class "Default")
      (node (ref "JP1184") (pin "P$1") (pinfunction "1_P$1") (pintype "passive"))
      (node (ref "JP235") (pin "1") (pinfunction "1_1") (pintype "passive"))
    )
    (net (code "67") (name "/33_1440304149") (class "Default")
      (node (ref "JP1025") (pin "P$1") (pinfunction "1_P$1") (pintype "passive"))
      (node (ref "JP30") (pin "1") (pinfunction "1_1") (pintype "passive"))
    )
    (net (code "68") (name "/33_1440304208") (class "Default")
      (node (ref "JP1200") (pin "P$1") (pinfunction "1_P$1") (pintype "passive"))
      (node (ref "JP206") (pin "1") (pinfunction "1_1") (pintype "passive"))
    )
    (net (code "69") (name "/34_1440304149") (class "Default")
      (node (ref "JP1027") (pin "P$1") (pinfunction "1_P$1") (pintype "passive"))
      (node (ref "JP40") (pin "1") (pinfunction "1_1") (pintype "passive"))
    )
    (net (code "70") (name "/34_1440304208") (class "Default")
      (node (ref "JP1153") (pin "P$1") (pinfunction "1_P$1") (pintype "passive"))
      (node (ref "JP75") (pin "1") (pinfunction "1_1") (pintype "passive"))
    )
    (net (code "71") (name "/35_1440304149") (class "Default")
      (node (ref "JP1029") (pin "P$1") (pinfunction "1_P$1") (pintype "passive"))
      (node (ref "JP50") (pin "1") (pinfunction "1_1") (pintype "passive"))
    )
    (net (code "72") (name "/35_1440304208") (class "Default")
      (node (ref "JP1183") (pin "P$1") (pinfunction "1_P$1") (pintype "passive"))
      (node (ref "JP225") (pin "1") (pinfunction "1_1") (pintype "passive"))
    )
    (net (code "73") (name "/36_1440304149") (class "Default")
      (node (ref "JP1031") (pin "P$1") (pinfunction "1_P$1") (pintype "passive"))
      (node (ref "JP60") (pin "1") (pinfunction "1_1") (pintype "passive"))
    )
    (net (code "74") (name "/36_1440304208") (class "Default")
      (node (ref "JP1152") (pin "P$1") (pinfunction "1_P$1") (pintype "passive"))
      (node (ref "JP85") (pin "1") (pinfunction "1_1") (pintype "passive"))
    )
    (net (code "75") (name "/37_1440304149") (class "Default")
      (node (ref "JP1033") (pin "P$1") (pinfunction "1_P$1") (pintype "passive"))
      (node (ref "JP70") (pin "1") (pinfunction "1_1") (pintype "passive"))
    )
    (net (code "76") (name "/37_1440304208") (class "Default")
      (node (ref "JP1182") (pin "P$1") (pinfunction "1_P$1") (pintype "passive"))
      (node (ref "JP215") (pin "1") (pinfunction "1_1") (pintype "passive"))
    )
    (net (code "77") (name "/38_1440304149") (class "Default")
      (node (ref "JP1035") (pin "P$1") (pinfunction "1_P$1") (pintype "passive"))
      (node (ref "JP80") (pin "1") (pinfunction "1_1") (pintype "passive"))
    )
    (net (code "78") (name "/38_1440304208") (class "Default")
      (node (ref "JP1151") (pin "P$1") (pinfunction "1_P$1") (pintype "passive"))
      (node (ref "JP95") (pin "1") (pinfunction "1_1") (pintype "passive"))
    )
    (net (code "79") (name "/39_1440304149") (class "Default")
      (node (ref "JP1037") (pin "P$1") (pinfunction "1_P$1") (pintype "passive"))
      (node (ref "JP90") (pin "1") (pinfunction "1_1") (pintype "passive"))
    )
    (net (code "80") (name "/39_1440304208") (class "Default")
      (node (ref "JP106") (pin "1") (pinfunction "1_1") (pintype "passive"))
      (node (ref "JP1161") (pin "P$1") (pinfunction "1_P$1") (pintype "passive"))
    )
    (net (code "81") (name "/40_1440304149") (class "Default")
      (node (ref "JP100") (pin "1") (pinfunction "1_1") (pintype "passive"))
      (node (ref "JP1039") (pin "P$1") (pinfunction "1_P$1") (pintype "passive"))
    )
    (net (code "82") (name "/40_1440304208") (class "Default")
      (node (ref "JP1181") (pin "P$1") (pinfunction "1_P$1") (pintype "passive"))
      (node (ref "JP205") (pin "1") (pinfunction "1_1") (pintype "passive"))
    )
    (net (code "83") (name "/41_1440304149") (class "Default")
      (node (ref "JP1041") (pin "P$1") (pinfunction "1_P$1") (pintype "passive"))
      (node (ref "JP110") (pin "1") (pinfunction "1_1") (pintype "passive"))
    )
    (net (code "84") (name "/41_1440304208") (class "Default")
      (node (ref "JP105") (pin "1") (pinfunction "1_1") (pintype "passive"))
      (node (ref "JP1149") (pin "P$1") (pinfunction "1_P$1") (pintype "passive"))
    )
    (net (code "85") (name "/42_1440304149") (class "Default")
      (node (ref "JP1043") (pin "P$1") (pinfunction "1_P$1") (pintype "passive"))
      (node (ref "JP120") (pin "1") (pinfunction "1_1") (pintype "passive"))
    )
    (net (code "86") (name "/42_1440304208") (class "Default")
      (node (ref "JP115") (pin "1") (pinfunction "1_1") (pintype "passive"))
      (node (ref "JP1150") (pin "P$1") (pinfunction "1_P$1") (pintype "passive"))
    )
    (net (code "87") (name "/43_1440304149") (class "Default")
      (node (ref "JP1045") (pin "P$1") (pinfunction "1_P$1") (pintype "passive"))
      (node (ref "JP130") (pin "1") (pinfunction "1_1") (pintype "passive"))
    )
    (net (code "88") (name "/43_1440304208") (class "Default")
      (node (ref "JP116") (pin "1") (pinfunction "1_1") (pintype "passive"))
      (node (ref "JP1162") (pin "P$1") (pinfunction "1_P$1") (pintype "passive"))
    )
    (net (code "89") (name "/44_1440304149") (class "Default")
      (node (ref "JP1047") (pin "P$1") (pinfunction "1_P$1") (pintype "passive"))
      (node (ref "JP140") (pin "1") (pinfunction "1_1") (pintype "passive"))
    )
    (net (code "90") (name "/44_1440304208") (class "Default")
      (node (ref "JP1163") (pin "P$1") (pinfunction "1_P$1") (pintype "passive"))
      (node (ref "JP126") (pin "1") (pinfunction "1_1") (pintype "passive"))
    )
    (net (code "91") (name "/45_1440304149") (class "Default")
      (node (ref "JP1049") (pin "P$1") (pinfunction "1_P$1") (pintype "passive"))
      (node (ref "JP150") (pin "1") (pinfunction "1_1") (pintype "passive"))
    )
    (net (code "92") (name "/45_1440304208") (class "Default")
      (node (ref "JP1148") (pin "P$1") (pinfunction "1_P$1") (pintype "passive"))
      (node (ref "JP125") (pin "1") (pinfunction "1_1") (pintype "passive"))
    )
    (net (code "93") (name "/46_1440304149") (class "Default")
      (node (ref "JP1051") (pin "P$1") (pinfunction "1_P$1") (pintype "passive"))
      (node (ref "JP160") (pin "1") (pinfunction "1_1") (pintype "passive"))
    )
    (net (code "94") (name "/46_1440304208") (class "Default")
      (node (ref "JP1164") (pin "P$1") (pinfunction "1_P$1") (pintype "passive"))
      (node (ref "JP136") (pin "1") (pinfunction "1_1") (pintype "passive"))
    )
    (net (code "95") (name "/47_1440304149") (class "Default")
      (node (ref "JP1053") (pin "P$1") (pinfunction "1_P$1") (pintype "passive"))
      (node (ref "JP170") (pin "1") (pinfunction "1_1") (pintype "passive"))
    )
    (net (code "96") (name "/47_1440304208") (class "Default")
      (node (ref "JP1147") (pin "P$1") (pinfunction "1_P$1") (pintype "passive"))
      (node (ref "JP135") (pin "1") (pinfunction "1_1") (pintype "passive"))
    )
    (net (code "97") (name "/48_1440304149") (class "Default")
      (node (ref "JP1055") (pin "P$1") (pinfunction "1_P$1") (pintype "passive"))
      (node (ref "JP180") (pin "1") (pinfunction "1_1") (pintype "passive"))
    )
    (net (code "98") (name "/48_1440304208") (class "Default")
      (node (ref "JP1165") (pin "P$1") (pinfunction "1_P$1") (pintype "passive"))
      (node (ref "JP146") (pin "1") (pinfunction "1_1") (pintype "passive"))
    )
    (net (code "99") (name "/49_1440304149") (class "Default")
      (node (ref "JP1057") (pin "P$1") (pinfunction "1_P$1") (pintype "passive"))
      (node (ref "JP190") (pin "1") (pinfunction "1_1") (pintype "passive"))
    )
    (net (code "100") (name "/49_1440304208") (class "Default")
      (node (ref "JP1146") (pin "P$1") (pinfunction "1_P$1") (pintype "passive"))
      (node (ref "JP145") (pin "1") (pinfunction "1_1") (pintype "passive"))
    )
    (net (code "101") (name "/50_1440304149") (class "Default")
      (node (ref "JP1059") (pin "P$1") (pinfunction "1_P$1") (pintype "passive"))
      (node (ref "JP200") (pin "1") (pinfunction "1_1") (pintype "passive"))
    )
    (net (code "102") (name "/50_1440304208") (class "Default")
      (node (ref "JP1166") (pin "P$1") (pinfunction "1_P$1") (pintype "passive"))
      (node (ref "JP156") (pin "1") (pinfunction "1_1") (pintype "passive"))
    )
    (net (code "103") (name "/51_1440304149") (class "Default")
      (node (ref "JP1061") (pin "P$1") (pinfunction "1_P$1") (pintype "passive"))
      (node (ref "JP210") (pin "1") (pinfunction "1_1") (pintype "passive"))
    )
    (net (code "104") (name "/51_1440304208") (class "Default")
      (node (ref "JP1167") (pin "P$1") (pinfunction "1_P$1") (pintype "passive"))
      (node (ref "JP166") (pin "1") (pinfunction "1_1") (pintype "passive"))
    )
    (net (code "105") (name "/52_1440304149") (class "Default")
      (node (ref "JP1063") (pin "P$1") (pinfunction "1_P$1") (pintype "passive"))
      (node (ref "JP220") (pin "1") (pinfunction "1_1") (pintype "passive"))
    )
    (net (code "106") (name "/52_1440304208") (class "Default")
      (node (ref "JP1145") (pin "P$1") (pinfunction "1_P$1") (pintype "passive"))
      (node (ref "JP155") (pin "1") (pinfunction "1_1") (pintype "passive"))
    )
    (net (code "107") (name "/53_1440304149") (class "Default")
      (node (ref "JP1065") (pin "P$1") (pinfunction "1_P$1") (pintype "passive"))
      (node (ref "JP230") (pin "1") (pinfunction "1_1") (pintype "passive"))
    )
    (net (code "108") (name "/53_1440304208") (class "Default")
      (node (ref "JP1168") (pin "P$1") (pinfunction "1_P$1") (pintype "passive"))
      (node (ref "JP176") (pin "1") (pinfunction "1_1") (pintype "passive"))
    )
    (net (code "109") (name "/54_1440304149") (class "Default")
      (node (ref "JP1067") (pin "P$1") (pinfunction "1_P$1") (pintype "passive"))
      (node (ref "JP240") (pin "1") (pinfunction "1_1") (pintype "passive"))
    )
    (net (code "110") (name "/54_1440304208") (class "Default")
      (node (ref "JP1144") (pin "P$1") (pinfunction "1_P$1") (pintype "passive"))
      (node (ref "JP165") (pin "1") (pinfunction "1_1") (pintype "passive"))
    )
    (net (code "111") (name "/55_1440304149") (class "Default")
      (node (ref "JP1069") (pin "P$1") (pinfunction "1_P$1") (pintype "passive"))
      (node (ref "JP250") (pin "1") (pinfunction "1_1") (pintype "passive"))
    )
    (net (code "112") (name "/55_1440304208") (class "Default")
      (node (ref "JP1169") (pin "P$1") (pinfunction "1_P$1") (pintype "passive"))
      (node (ref "JP186") (pin "1") (pinfunction "1_1") (pintype "passive"))
    )
    (net (code "113") (name "/56_1440304149") (class "Default")
      (node (ref "JP1071") (pin "P$1") (pinfunction "1_P$1") (pintype "passive"))
      (node (ref "JP260") (pin "1") (pinfunction "1_1") (pintype "passive"))
    )
    (net (code "114") (name "/56_1440304208") (class "Default")
      (node (ref "JP1143") (pin "P$1") (pinfunction "1_P$1") (pintype "passive"))
      (node (ref "JP175") (pin "1") (pinfunction "1_1") (pintype "passive"))
    )
    (net (code "115") (name "/57_1440304149") (class "Default")
      (node (ref "JP1073") (pin "P$1") (pinfunction "1_P$1") (pintype "passive"))
      (node (ref "JP270") (pin "1") (pinfunction "1_1") (pintype "passive"))
    )
    (net (code "116") (name "/57_1440304208") (class "Default")
      (node (ref "JP1170") (pin "P$1") (pinfunction "1_P$1") (pintype "passive"))
      (node (ref "JP196") (pin "1") (pinfunction "1_1") (pintype "passive"))
    )
    (net (code "117") (name "/58_1440304149") (class "Default")
      (node (ref "JP1075") (pin "P$1") (pinfunction "1_P$1") (pintype "passive"))
      (node (ref "JP280") (pin "1") (pinfunction "1_1") (pintype "passive"))
    )
    (net (code "118") (name "/58_1440304208") (class "Default")
      (node (ref "JP1142") (pin "P$1") (pinfunction "1_P$1") (pintype "passive"))
      (node (ref "JP185") (pin "1") (pinfunction "1_1") (pintype "passive"))
    )
    (net (code "119") (name "/59_1440304149") (class "Default")
      (node (ref "JP1077") (pin "P$1") (pinfunction "1_P$1") (pintype "passive"))
      (node (ref "JP290") (pin "1") (pinfunction "1_1") (pintype "passive"))
    )
    (net (code "120") (name "/59_1440304208") (class "Default")
      (node (ref "JP1141") (pin "P$1") (pinfunction "1_P$1") (pintype "passive"))
      (node (ref "JP195") (pin "1") (pinfunction "1_1") (pintype "passive"))
    )
    (net (code "121") (name "/60_1440304149") (class "Default")
      (node (ref "JP1079") (pin "P$1") (pinfunction "1_P$1") (pintype "passive"))
      (node (ref "JP300") (pin "1") (pinfunction "1_1") (pintype "passive"))
    )
    (net (code "122") (name "/61_1440304149") (class "Default")
      (node (ref "JP1080") (pin "P$1") (pinfunction "1_P$1") (pintype "passive"))
      (node (ref "JP299") (pin "1") (pinfunction "1_1") (pintype "passive"))
    )
    (net (code "123") (name "/62_1440304149") (class "Default")
      (node (ref "JP2") (pin "1") (pinfunction "1_1") (pintype "passive"))
      (node (ref "JP962") (pin "P$1") (pinfunction "1_P$1") (pintype "passive"))
    )
    (net (code "124") (name "/63_1440304149") (class "Default")
      (node (ref "JP12") (pin "1") (pinfunction "1_1") (pintype "passive"))
      (node (ref "JP964") (pin "P$1") (pinfunction "1_P$1") (pintype "passive"))
    )
    (net (code "125") (name "/64_1440304149") (class "Default")
      (node (ref "JP22") (pin "1") (pinfunction "1_1") (pintype "passive"))
      (node (ref "JP966") (pin "P$1") (pinfunction "1_P$1") (pintype "passive"))
    )
    (net (code "126") (name "/65_1440304149") (class "Default")
      (node (ref "JP32") (pin "1") (pinfunction "1_1") (pintype "passive"))
      (node (ref "JP968") (pin "P$1") (pinfunction "1_P$1") (pintype "passive"))
    )
    (net (code "127") (name "/66_1440304149") (class "Default")
      (node (ref "JP42") (pin "1") (pinfunction "1_1") (pintype "passive"))
      (node (ref "JP970") (pin "P$1") (pinfunction "1_P$1") (pintype "passive"))
    )
    (net (code "128") (name "/67_1440304149") (class "Default")
      (node (ref "JP52") (pin "1") (pinfunction "1_1") (pintype "passive"))
      (node (ref "JP972") (pin "P$1") (pinfunction "1_P$1") (pintype "passive"))
    )
    (net (code "129") (name "/68_1440304149") (class "Default")
      (node (ref "JP62") (pin "1") (pinfunction "1_1") (pintype "passive"))
      (node (ref "JP974") (pin "P$1") (pinfunction "1_P$1") (pintype "passive"))
    )
    (net (code "130") (name "/69_1440304149") (class "Default")
      (node (ref "JP72") (pin "1") (pinfunction "1_1") (pintype "passive"))
      (node (ref "JP976") (pin "P$1") (pinfunction "1_P$1") (pintype "passive"))
    )
    (net (code "131") (name "/70_1440304149") (class "Default")
      (node (ref "JP82") (pin "1") (pinfunction "1_1") (pintype "passive"))
      (node (ref "JP978") (pin "P$1") (pinfunction "1_P$1") (pintype "passive"))
    )
    (net (code "132") (name "/71_1440304149") (class "Default")
      (node (ref "JP92") (pin "1") (pinfunction "1_1") (pintype "passive"))
      (node (ref "JP980") (pin "P$1") (pinfunction "1_P$1") (pintype "passive"))
    )
    (net (code "133") (name "/72_1440304149") (class "Default")
      (node (ref "JP102") (pin "1") (pinfunction "1_1") (pintype "passive"))
      (node (ref "JP982") (pin "P$1") (pinfunction "1_P$1") (pintype "passive"))
    )
    (net (code "134") (name "/73_1440304149") (class "Default")
      (node (ref "JP112") (pin "1") (pinfunction "1_1") (pintype "passive"))
      (node (ref "JP984") (pin "P$1") (pinfunction "1_P$1") (pintype "passive"))
    )
    (net (code "135") (name "/74_1440304149") (class "Default")
      (node (ref "JP122") (pin "1") (pinfunction "1_1") (pintype "passive"))
      (node (ref "JP986") (pin "P$1") (pinfunction "1_P$1") (pintype "passive"))
    )
    (net (code "136") (name "/75_1440304149") (class "Default")
      (node (ref "JP132") (pin "1") (pinfunction "1_1") (pintype "passive"))
      (node (ref "JP988") (pin "P$1") (pinfunction "1_P$1") (pintype "passive"))
    )
    (net (code "137") (name "/76_1440304149") (class "Default")
      (node (ref "JP142") (pin "1") (pinfunction "1_1") (pintype "passive"))
      (node (ref "JP990") (pin "P$1") (pinfunction "1_P$1") (pintype "passive"))
    )
    (net (code "138") (name "/77_1440304149") (class "Default")
      (node (ref "JP152") (pin "1") (pinfunction "1_1") (pintype "passive"))
      (node (ref "JP992") (pin "P$1") (pinfunction "1_P$1") (pintype "passive"))
    )
    (net (code "139") (name "/78_1440304149") (class "Default")
      (node (ref "JP162") (pin "1") (pinfunction "1_1") (pintype "passive"))
      (node (ref "JP994") (pin "P$1") (pinfunction "1_P$1") (pintype "passive"))
    )
    (net (code "140") (name "/79_1440304149") (class "Default")
      (node (ref "JP172") (pin "1") (pinfunction "1_1") (pintype "passive"))
      (node (ref "JP996") (pin "P$1") (pinfunction "1_P$1") (pintype "passive"))
    )
    (net (code "141") (name "/80_1440304149") (class "Default")
      (node (ref "JP182") (pin "1") (pinfunction "1_1") (pintype "passive"))
      (node (ref "JP998") (pin "P$1") (pinfunction "1_P$1") (pintype "passive"))
    )
    (net (code "142") (name "/81_1440304149") (class "Default")
      (node (ref "JP1000") (pin "P$1") (pinfunction "1_P$1") (pintype "passive"))
      (node (ref "JP192") (pin "1") (pinfunction "1_1") (pintype "passive"))
    )
    (net (code "143") (name "/82_1440304149") (class "Default")
      (node (ref "JP1002") (pin "P$1") (pinfunction "1_P$1") (pintype "passive"))
      (node (ref "JP202") (pin "1") (pinfunction "1_1") (pintype "passive"))
    )
    (net (code "144") (name "/83_1440304149") (class "Default")
      (node (ref "JP1004") (pin "P$1") (pinfunction "1_P$1") (pintype "passive"))
      (node (ref "JP212") (pin "1") (pinfunction "1_1") (pintype "passive"))
    )
    (net (code "145") (name "/84_1440304149") (class "Default")
      (node (ref "JP1006") (pin "P$1") (pinfunction "1_P$1") (pintype "passive"))
      (node (ref "JP222") (pin "1") (pinfunction "1_1") (pintype "passive"))
    )
    (net (code "146") (name "/85_1440304149") (class "Default")
      (node (ref "JP1008") (pin "P$1") (pinfunction "1_P$1") (pintype "passive"))
      (node (ref "JP232") (pin "1") (pinfunction "1_1") (pintype "passive"))
    )
    (net (code "147") (name "/86_1440304149") (class "Default")
      (node (ref "JP1010") (pin "P$1") (pinfunction "1_P$1") (pintype "passive"))
      (node (ref "JP242") (pin "1") (pinfunction "1_1") (pintype "passive"))
    )
    (net (code "148") (name "/87_1440304149") (class "Default")
      (node (ref "JP1012") (pin "P$1") (pinfunction "1_P$1") (pintype "passive"))
      (node (ref "JP252") (pin "1") (pinfunction "1_1") (pintype "passive"))
    )
    (net (code "149") (name "/88_1440304149") (class "Default")
      (node (ref "JP1014") (pin "P$1") (pinfunction "1_P$1") (pintype "passive"))
      (node (ref "JP262") (pin "1") (pinfunction "1_1") (pintype "passive"))
    )
    (net (code "150") (name "/89_1440304149") (class "Default")
      (node (ref "JP1016") (pin "P$1") (pinfunction "1_P$1") (pintype "passive"))
      (node (ref "JP272") (pin "1") (pinfunction "1_1") (pintype "passive"))
    )
    (net (code "151") (name "/90_1440304149") (class "Default")
      (node (ref "JP1018") (pin "P$1") (pinfunction "1_P$1") (pintype "passive"))
      (node (ref "JP282") (pin "1") (pinfunction "1_1") (pintype "passive"))
    )
    (net (code "152") (name "/91_1440304149") (class "Default")
      (node (ref "JP1022") (pin "P$1") (pinfunction "1_P$1") (pintype "passive"))
      (node (ref "JP9") (pin "1") (pinfunction "1_1") (pintype "passive"))
    )
    (net (code "153") (name "/92_1440304149") (class "Default")
      (node (ref "JP1024") (pin "P$1") (pinfunction "1_P$1") (pintype "passive"))
      (node (ref "JP19") (pin "1") (pinfunction "1_1") (pintype "passive"))
    )
    (net (code "154") (name "/93_1440304149") (class "Default")
      (node (ref "JP1026") (pin "P$1") (pinfunction "1_P$1") (pintype "passive"))
      (node (ref "JP29") (pin "1") (pinfunction "1_1") (pintype "passive"))
    )
    (net (code "155") (name "/94_1440304149") (class "Default")
      (node (ref "JP1028") (pin "P$1") (pinfunction "1_P$1") (pintype "passive"))
      (node (ref "JP39") (pin "1") (pinfunction "1_1") (pintype "passive"))
    )
    (net (code "156") (name "/95_1440304149") (class "Default")
      (node (ref "JP1030") (pin "P$1") (pinfunction "1_P$1") (pintype "passive"))
      (node (ref "JP49") (pin "1") (pinfunction "1_1") (pintype "passive"))
    )
    (net (code "157") (name "/96_1440304149") (class "Default")
      (node (ref "JP1032") (pin "P$1") (pinfunction "1_P$1") (pintype "passive"))
      (node (ref "JP59") (pin "1") (pinfunction "1_1") (pintype "passive"))
    )
    (net (code "158") (name "/97_1440304149") (class "Default")
      (node (ref "JP1034") (pin "P$1") (pinfunction "1_P$1") (pintype "passive"))
      (node (ref "JP69") (pin "1") (pinfunction "1_1") (pintype "passive"))
    )
    (net (code "159") (name "/98_1440304149") (class "Default")
      (node (ref "JP1036") (pin "P$1") (pinfunction "1_P$1") (pintype "passive"))
      (node (ref "JP79") (pin "1") (pinfunction "1_1") (pintype "passive"))
    )
    (net (code "160") (name "/99_1440304149") (class "Default")
      (node (ref "JP1038") (pin "P$1") (pinfunction "1_P$1") (pintype "passive"))
      (node (ref "JP89") (pin "1") (pinfunction "1_1") (pintype "passive"))
    )
    (net (code "161") (name "/100_1440304149") (class "Default")
      (node (ref "JP1040") (pin "P$1") (pinfunction "1_P$1") (pintype "passive"))
      (node (ref "JP99") (pin "1") (pinfunction "1_1") (pintype "passive"))
    )
    (net (code "162") (name "/101_1440304149") (class "Default")
      (node (ref "JP1042") (pin "P$1") (pinfunction "1_P$1") (pintype "passive"))
      (node (ref "JP109") (pin "1") (pinfunction "1_1") (pintype "passive"))
    )
    (net (code "163") (name "/102_1440304149") (class "Default")
      (node (ref "JP1044") (pin "P$1") (pinfunction "1_P$1") (pintype "passive"))
      (node (ref "JP119") (pin "1") (pinfunction "1_1") (pintype "passive"))
    )
    (net (code "164") (name "/103_1440304149") (class "Default")
      (node (ref "JP1046") (pin "P$1") (pinfunction "1_P$1") (pintype "passive"))
      (node (ref "JP129") (pin "1") (pinfunction "1_1") (pintype "passive"))
    )
    (net (code "165") (name "/104_1440304149") (class "Default")
      (node (ref "JP1048") (pin "P$1") (pinfunction "1_P$1") (pintype "passive"))
      (node (ref "JP139") (pin "1") (pinfunction "1_1") (pintype "passive"))
    )
    (net (code "166") (name "/105_1440304149") (class "Default")
      (node (ref "JP1050") (pin "P$1") (pinfunction "1_P$1") (pintype "passive"))
      (node (ref "JP149") (pin "1") (pinfunction "1_1") (pintype "passive"))
    )
    (net (code "167") (name "/106_1440304149") (class "Default")
      (node (ref "JP1052") (pin "P$1") (pinfunction "1_P$1") (pintype "passive"))
      (node (ref "JP159") (pin "1") (pinfunction "1_1") (pintype "passive"))
    )
    (net (code "168") (name "/107_1440304149") (class "Default")
      (node (ref "JP1054") (pin "P$1") (pinfunction "1_P$1") (pintype "passive"))
      (node (ref "JP169") (pin "1") (pinfunction "1_1") (pintype "passive"))
    )
    (net (code "169") (name "/108_1440304149") (class "Default")
      (node (ref "JP1056") (pin "P$1") (pinfunction "1_P$1") (pintype "passive"))
      (node (ref "JP179") (pin "1") (pinfunction "1_1") (pintype "passive"))
    )
    (net (code "170") (name "/109_1440304149") (class "Default")
      (node (ref "JP1058") (pin "P$1") (pinfunction "1_P$1") (pintype "passive"))
      (node (ref "JP189") (pin "1") (pinfunction "1_1") (pintype "passive"))
    )
    (net (code "171") (name "/110_1440304149") (class "Default")
      (node (ref "JP1060") (pin "P$1") (pinfunction "1_P$1") (pintype "passive"))
      (node (ref "JP199") (pin "1") (pinfunction "1_1") (pintype "passive"))
    )
    (net (code "172") (name "/111_1440304149") (class "Default")
      (node (ref "JP1062") (pin "P$1") (pinfunction "1_P$1") (pintype "passive"))
      (node (ref "JP209") (pin "1") (pinfunction "1_1") (pintype "passive"))
    )
    (net (code "173") (name "/112_1440304149") (class "Default")
      (node (ref "JP1064") (pin "P$1") (pinfunction "1_P$1") (pintype "passive"))
      (node (ref "JP219") (pin "1") (pinfunction "1_1") (pintype "passive"))
    )
    (net (code "174") (name "/113_1440304149") (class "Default")
      (node (ref "JP1066") (pin "P$1") (pinfunction "1_P$1") (pintype "passive"))
      (node (ref "JP229") (pin "1") (pinfunction "1_1") (pintype "passive"))
    )
    (net (code "175") (name "/114_1440304149") (class "Default")
      (node (ref "JP1068") (pin "P$1") (pinfunction "1_P$1") (pintype "passive"))
      (node (ref "JP239") (pin "1") (pinfunction "1_1") (pintype "passive"))
    )
    (net (code "176") (name "/115_1440304149") (class "Default")
      (node (ref "JP1070") (pin "P$1") (pinfunction "1_P$1") (pintype "passive"))
      (node (ref "JP249") (pin "1") (pinfunction "1_1") (pintype "passive"))
    )
    (net (code "177") (name "/116_1440304149") (class "Default")
      (node (ref "JP1072") (pin "P$1") (pinfunction "1_P$1") (pintype "passive"))
      (node (ref "JP259") (pin "1") (pinfunction "1_1") (pintype "passive"))
    )
    (net (code "178") (name "/117_1440304149") (class "Default")
      (node (ref "JP1074") (pin "P$1") (pinfunction "1_P$1") (pintype "passive"))
      (node (ref "JP269") (pin "1") (pinfunction "1_1") (pintype "passive"))
    )
    (net (code "179") (name "/118_1440304149") (class "Default")
      (node (ref "JP1076") (pin "P$1") (pinfunction "1_P$1") (pintype "passive"))
      (node (ref "JP279") (pin "1") (pinfunction "1_1") (pintype "passive"))
    )
    (net (code "180") (name "/119_1440304149") (class "Default")
      (node (ref "JP1078") (pin "P$1") (pinfunction "1_P$1") (pintype "passive"))
      (node (ref "JP289") (pin "1") (pinfunction "1_1") (pintype "passive"))
    )
    (net (code "181") (name "/120_1440304149") (class "Default")
      (node (ref "JP1081") (pin "P$1") (pinfunction "1_P$1") (pintype "passive"))
      (node (ref "JP8") (pin "1") (pinfunction "1_1") (pintype "passive"))
    )
    (net (code "182") (name "/121_1440304149") (class "Default")
      (node (ref "JP1083") (pin "P$1") (pinfunction "1_P$1") (pintype "passive"))
      (node (ref "JP18") (pin "1") (pinfunction "1_1") (pintype "passive"))
    )
    (net (code "183") (name "/122_1440304149") (class "Default")
      (node (ref "JP1085") (pin "P$1") (pinfunction "1_P$1") (pintype "passive"))
      (node (ref "JP28") (pin "1") (pinfunction "1_1") (pintype "passive"))
    )
    (net (code "184") (name "/123_1440304149") (class "Default")
      (node (ref "JP1087") (pin "P$1") (pinfunction "1_P$1") (pintype "passive"))
      (node (ref "JP38") (pin "1") (pinfunction "1_1") (pintype "passive"))
    )
    (net (code "185") (name "/124_1440304149") (class "Default")
      (node (ref "JP1089") (pin "P$1") (pinfunction "1_P$1") (pintype "passive"))
      (node (ref "JP48") (pin "1") (pinfunction "1_1") (pintype "passive"))
    )
    (net (code "186") (name "/125_1440304149") (class "Default")
      (node (ref "JP1091") (pin "P$1") (pinfunction "1_P$1") (pintype "passive"))
      (node (ref "JP58") (pin "1") (pinfunction "1_1") (pintype "passive"))
    )
    (net (code "187") (name "/126_1440304149") (class "Default")
      (node (ref "JP1093") (pin "P$1") (pinfunction "1_P$1") (pintype "passive"))
      (node (ref "JP68") (pin "1") (pinfunction "1_1") (pintype "passive"))
    )
    (net (code "188") (name "/127_1440304149") (class "Default")
      (node (ref "JP1095") (pin "P$1") (pinfunction "1_P$1") (pintype "passive"))
      (node (ref "JP78") (pin "1") (pinfunction "1_1") (pintype "passive"))
    )
    (net (code "189") (name "/128_1440304149") (class "Default")
      (node (ref "JP1097") (pin "P$1") (pinfunction "1_P$1") (pintype "passive"))
      (node (ref "JP88") (pin "1") (pinfunction "1_1") (pintype "passive"))
    )
    (net (code "190") (name "/129_1440304149") (class "Default")
      (node (ref "JP1099") (pin "P$1") (pinfunction "1_P$1") (pintype "passive"))
      (node (ref "JP98") (pin "1") (pinfunction "1_1") (pintype "passive"))
    )
    (net (code "191") (name "/130_1440304149") (class "Default")
      (node (ref "JP108") (pin "1") (pinfunction "1_1") (pintype "passive"))
      (node (ref "JP1101") (pin "P$1") (pinfunction "1_P$1") (pintype "passive"))
    )
    (net (code "192") (name "/131_1440304149") (class "Default")
      (node (ref "JP1103") (pin "P$1") (pinfunction "1_P$1") (pintype "passive"))
      (node (ref "JP118") (pin "1") (pinfunction "1_1") (pintype "passive"))
    )
    (net (code "193") (name "/132_1440304149") (class "Default")
      (node (ref "JP1105") (pin "P$1") (pinfunction "1_P$1") (pintype "passive"))
      (node (ref "JP128") (pin "1") (pinfunction "1_1") (pintype "passive"))
    )
    (net (code "194") (name "/133_1440304149") (class "Default")
      (node (ref "JP1107") (pin "P$1") (pinfunction "1_P$1") (pintype "passive"))
      (node (ref "JP138") (pin "1") (pinfunction "1_1") (pintype "passive"))
    )
    (net (code "195") (name "/134_1440304149") (class "Default")
      (node (ref "JP1109") (pin "P$1") (pinfunction "1_P$1") (pintype "passive"))
      (node (ref "JP148") (pin "1") (pinfunction "1_1") (pintype "passive"))
    )
    (net (code "196") (name "/135_1440304149") (class "Default")
      (node (ref "JP1111") (pin "P$1") (pinfunction "1_P$1") (pintype "passive"))
      (node (ref "JP158") (pin "1") (pinfunction "1_1") (pintype "passive"))
    )
    (net (code "197") (name "/136_1440304149") (class "Default")
      (node (ref "JP1113") (pin "P$1") (pinfunction "1_P$1") (pintype "passive"))
      (node (ref "JP168") (pin "1") (pinfunction "1_1") (pintype "passive"))
    )
    (net (code "198") (name "/137_1440304149") (class "Default")
      (node (ref "JP1115") (pin "P$1") (pinfunction "1_P$1") (pintype "passive"))
      (node (ref "JP178") (pin "1") (pinfunction "1_1") (pintype "passive"))
    )
    (net (code "199") (name "/138_1440304149") (class "Default")
      (node (ref "JP1117") (pin "P$1") (pinfunction "1_P$1") (pintype "passive"))
      (node (ref "JP188") (pin "1") (pinfunction "1_1") (pintype "passive"))
    )
    (net (code "200") (name "/139_1440304149") (class "Default")
      (node (ref "JP1119") (pin "P$1") (pinfunction "1_P$1") (pintype "passive"))
      (node (ref "JP198") (pin "1") (pinfunction "1_1") (pintype "passive"))
    )
    (net (code "201") (name "/140_1440304149") (class "Default")
      (node (ref "JP1121") (pin "P$1") (pinfunction "1_P$1") (pintype "passive"))
      (node (ref "JP208") (pin "1") (pinfunction "1_1") (pintype "passive"))
    )
    (net (code "202") (name "/141_1440304149") (class "Default")
      (node (ref "JP1123") (pin "P$1") (pinfunction "1_P$1") (pintype "passive"))
      (node (ref "JP218") (pin "1") (pinfunction "1_1") (pintype "passive"))
    )
    (net (code "203") (name "/142_1440304149") (class "Default")
      (node (ref "JP1125") (pin "P$1") (pinfunction "1_P$1") (pintype "passive"))
      (node (ref "JP228") (pin "1") (pinfunction "1_1") (pintype "passive"))
    )
    (net (code "204") (name "/143_1440304149") (class "Default")
      (node (ref "JP1127") (pin "P$1") (pinfunction "1_P$1") (pintype "passive"))
      (node (ref "JP238") (pin "1") (pinfunction "1_1") (pintype "passive"))
    )
    (net (code "205") (name "/144_1440304149") (class "Default")
      (node (ref "JP1129") (pin "P$1") (pinfunction "1_P$1") (pintype "passive"))
      (node (ref "JP248") (pin "1") (pinfunction "1_1") (pintype "passive"))
    )
    (net (code "206") (name "/145_1440304149") (class "Default")
      (node (ref "JP1131") (pin "P$1") (pinfunction "1_P$1") (pintype "passive"))
      (node (ref "JP258") (pin "1") (pinfunction "1_1") (pintype "passive"))
    )
    (net (code "207") (name "/146_1440304149") (class "Default")
      (node (ref "JP1133") (pin "P$1") (pinfunction "1_P$1") (pintype "passive"))
      (node (ref "JP268") (pin "1") (pinfunction "1_1") (pintype "passive"))
    )
    (net (code "208") (name "/147_1440304149") (class "Default")
      (node (ref "JP1135") (pin "P$1") (pinfunction "1_P$1") (pintype "passive"))
      (node (ref "JP278") (pin "1") (pinfunction "1_1") (pintype "passive"))
    )
    (net (code "209") (name "/148_1440304149") (class "Default")
      (node (ref "JP1137") (pin "P$1") (pinfunction "1_P$1") (pintype "passive"))
      (node (ref "JP288") (pin "1") (pinfunction "1_1") (pintype "passive"))
    )
    (net (code "210") (name "/149_1440304149") (class "Default")
      (node (ref "JP1139") (pin "P$1") (pinfunction "1_P$1") (pintype "passive"))
      (node (ref "JP298") (pin "1") (pinfunction "1_1") (pintype "passive"))
    )
    (net (code "211") (name "/150_1440304149") (class "Default")
      (node (ref "JP1140") (pin "P$1") (pinfunction "1_P$1") (pintype "passive"))
      (node (ref "JP297") (pin "1") (pinfunction "1_1") (pintype "passive"))
    )
    (net (code "212") (name "/151_1440304149") (class "Default")
      (node (ref "JP3") (pin "1") (pinfunction "1_1") (pintype "passive"))
      (node (ref "JP901") (pin "P$1") (pinfunction "1_P$1") (pintype "passive"))
    )
    (net (code "213") (name "/152_1440304149") (class "Default")
      (node (ref "JP13") (pin "1") (pinfunction "1_1") (pintype "passive"))
      (node (ref "JP903") (pin "P$1") (pinfunction "1_P$1") (pintype "passive"))
    )
    (net (code "214") (name "/153_1440304149") (class "Default")
      (node (ref "JP23") (pin "1") (pinfunction "1_1") (pintype "passive"))
      (node (ref "JP905") (pin "P$1") (pinfunction "1_P$1") (pintype "passive"))
    )
    (net (code "215") (name "/154_1440304149") (class "Default")
      (node (ref "JP33") (pin "1") (pinfunction "1_1") (pintype "passive"))
      (node (ref "JP907") (pin "P$1") (pinfunction "1_P$1") (pintype "passive"))
    )
    (net (code "216") (name "/155_1440304149") (class "Default")
      (node (ref "JP43") (pin "1") (pinfunction "1_1") (pintype "passive"))
      (node (ref "JP909") (pin "P$1") (pinfunction "1_P$1") (pintype "passive"))
    )
    (net (code "217") (name "/156_1440304149") (class "Default")
      (node (ref "JP53") (pin "1") (pinfunction "1_1") (pintype "passive"))
      (node (ref "JP911") (pin "P$1") (pinfunction "1_P$1") (pintype "passive"))
    )
    (net (code "218") (name "/157_1440304149") (class "Default")
      (node (ref "JP63") (pin "1") (pinfunction "1_1") (pintype "passive"))
      (node (ref "JP913") (pin "P$1") (pinfunction "1_P$1") (pintype "passive"))
    )
    (net (code "219") (name "/158_1440304149") (class "Default")
      (node (ref "JP73") (pin "1") (pinfunction "1_1") (pintype "passive"))
      (node (ref "JP915") (pin "P$1") (pinfunction "1_P$1") (pintype "passive"))
    )
    (net (code "220") (name "/159_1440304149") (class "Default")
      (node (ref "JP83") (pin "1") (pinfunction "1_1") (pintype "passive"))
      (node (ref "JP917") (pin "P$1") (pinfunction "1_P$1") (pintype "passive"))
    )
    (net (code "221") (name "/160_1440304149") (class "Default")
      (node (ref "JP919") (pin "P$1") (pinfunction "1_P$1") (pintype "passive"))
      (node (ref "JP93") (pin "1") (pinfunction "1_1") (pintype "passive"))
    )
    (net (code "222") (name "/161_1440304149") (class "Default")
      (node (ref "JP103") (pin "1") (pinfunction "1_1") (pintype "passive"))
      (node (ref "JP921") (pin "P$1") (pinfunction "1_P$1") (pintype "passive"))
    )
    (net (code "223") (name "/162_1440304149") (class "Default")
      (node (ref "JP113") (pin "1") (pinfunction "1_1") (pintype "passive"))
      (node (ref "JP923") (pin "P$1") (pinfunction "1_P$1") (pintype "passive"))
    )
    (net (code "224") (name "/163_1440304149") (class "Default")
      (node (ref "JP123") (pin "1") (pinfunction "1_1") (pintype "passive"))
      (node (ref "JP925") (pin "P$1") (pinfunction "1_P$1") (pintype "passive"))
    )
    (net (code "225") (name "/164_1440304149") (class "Default")
      (node (ref "JP133") (pin "1") (pinfunction "1_1") (pintype "passive"))
      (node (ref "JP927") (pin "P$1") (pinfunction "1_P$1") (pintype "passive"))
    )
    (net (code "226") (name "/165_1440304149") (class "Default")
      (node (ref "JP143") (pin "1") (pinfunction "1_1") (pintype "passive"))
      (node (ref "JP929") (pin "P$1") (pinfunction "1_P$1") (pintype "passive"))
    )
    (net (code "227") (name "/166_1440304149") (class "Default")
      (node (ref "JP153") (pin "1") (pinfunction "1_1") (pintype "passive"))
      (node (ref "JP931") (pin "P$1") (pinfunction "1_P$1") (pintype "passive"))
    )
    (net (code "228") (name "/167_1440304149") (class "Default")
      (node (ref "JP163") (pin "1") (pinfunction "1_1") (pintype "passive"))
      (node (ref "JP933") (pin "P$1") (pinfunction "1_P$1") (pintype "passive"))
    )
    (net (code "229") (name "/168_1440304149") (class "Default")
      (node (ref "JP173") (pin "1") (pinfunction "1_1") (pintype "passive"))
      (node (ref "JP935") (pin "P$1") (pinfunction "1_P$1") (pintype "passive"))
    )
    (net (code "230") (name "/169_1440304149") (class "Default")
      (node (ref "JP183") (pin "1") (pinfunction "1_1") (pintype "passive"))
      (node (ref "JP937") (pin "P$1") (pinfunction "1_P$1") (pintype "passive"))
    )
    (net (code "231") (name "/170_1440304149") (class "Default")
      (node (ref "JP193") (pin "1") (pinfunction "1_1") (pintype "passive"))
      (node (ref "JP939") (pin "P$1") (pinfunction "1_P$1") (pintype "passive"))
    )
    (net (code "232") (name "/171_1440304149") (class "Default")
      (node (ref "JP203") (pin "1") (pinfunction "1_1") (pintype "passive"))
      (node (ref "JP941") (pin "P$1") (pinfunction "1_P$1") (pintype "passive"))
    )
    (net (code "233") (name "/172_1440304149") (class "Default")
      (node (ref "JP213") (pin "1") (pinfunction "1_1") (pintype "passive"))
      (node (ref "JP943") (pin "P$1") (pinfunction "1_P$1") (pintype "passive"))
    )
    (net (code "234") (name "/173_1440304149") (class "Default")
      (node (ref "JP223") (pin "1") (pinfunction "1_1") (pintype "passive"))
      (node (ref "JP945") (pin "P$1") (pinfunction "1_P$1") (pintype "passive"))
    )
    (net (code "235") (name "/174_1440304149") (class "Default")
      (node (ref "JP233") (pin "1") (pinfunction "1_1") (pintype "passive"))
      (node (ref "JP947") (pin "P$1") (pinfunction "1_P$1") (pintype "passive"))
    )
    (net (code "236") (name "/175_1440304149") (class "Default")
      (node (ref "JP243") (pin "1") (pinfunction "1_1") (pintype "passive"))
      (node (ref "JP949") (pin "P$1") (pinfunction "1_P$1") (pintype "passive"))
    )
    (net (code "237") (name "/176_1440304149") (class "Default")
      (node (ref "JP253") (pin "1") (pinfunction "1_1") (pintype "passive"))
      (node (ref "JP951") (pin "P$1") (pinfunction "1_P$1") (pintype "passive"))
    )
    (net (code "238") (name "/177_1440304149") (class "Default")
      (node (ref "JP263") (pin "1") (pinfunction "1_1") (pintype "passive"))
      (node (ref "JP953") (pin "P$1") (pinfunction "1_P$1") (pintype "passive"))
    )
    (net (code "239") (name "/178_1440304149") (class "Default")
      (node (ref "JP273") (pin "1") (pinfunction "1_1") (pintype "passive"))
      (node (ref "JP955") (pin "P$1") (pinfunction "1_P$1") (pintype "passive"))
    )
    (net (code "240") (name "/179_1440304149") (class "Default")
      (node (ref "JP283") (pin "1") (pinfunction "1_1") (pintype "passive"))
      (node (ref "JP957") (pin "P$1") (pinfunction "1_P$1") (pintype "passive"))
    )
    (net (code "241") (name "/180_1440304149") (class "Default")
      (node (ref "JP293") (pin "1") (pinfunction "1_1") (pintype "passive"))
      (node (ref "JP959") (pin "P$1") (pinfunction "1_P$1") (pintype "passive"))
    )
    (net (code "242") (name "/181_1440304149") (class "Default")
      (node (ref "JP294") (pin "1") (pinfunction "1_1") (pintype "passive"))
      (node (ref "JP960") (pin "P$1") (pinfunction "1_P$1") (pintype "passive"))
    )
    (net (code "243") (name "/182_1440304149") (class "Default")
      (node (ref "JP1082") (pin "P$1") (pinfunction "1_P$1") (pintype "passive"))
      (node (ref "JP7") (pin "1") (pinfunction "1_1") (pintype "passive"))
    )
    (net (code "244") (name "/183_1440304149") (class "Default")
      (node (ref "JP1084") (pin "P$1") (pinfunction "1_P$1") (pintype "passive"))
      (node (ref "JP17") (pin "1") (pinfunction "1_1") (pintype "passive"))
    )
    (net (code "245") (name "/184_1440304149") (class "Default")
      (node (ref "JP1086") (pin "P$1") (pinfunction "1_P$1") (pintype "passive"))
      (node (ref "JP27") (pin "1") (pinfunction "1_1") (pintype "passive"))
    )
    (net (code "246") (name "/185_1440304149") (class "Default")
      (node (ref "JP1088") (pin "P$1") (pinfunction "1_P$1") (pintype "passive"))
      (node (ref "JP37") (pin "1") (pinfunction "1_1") (pintype "passive"))
    )
    (net (code "247") (name "/186_1440304149") (class "Default")
      (node (ref "JP1090") (pin "P$1") (pinfunction "1_P$1") (pintype "passive"))
      (node (ref "JP47") (pin "1") (pinfunction "1_1") (pintype "passive"))
    )
    (net (code "248") (name "/187_1440304149") (class "Default")
      (node (ref "JP1092") (pin "P$1") (pinfunction "1_P$1") (pintype "passive"))
      (node (ref "JP57") (pin "1") (pinfunction "1_1") (pintype "passive"))
    )
    (net (code "249") (name "/188_1440304149") (class "Default")
      (node (ref "JP1094") (pin "P$1") (pinfunction "1_P$1") (pintype "passive"))
      (node (ref "JP67") (pin "1") (pinfunction "1_1") (pintype "passive"))
    )
    (net (code "250") (name "/189_1440304149") (class "Default")
      (node (ref "JP1096") (pin "P$1") (pinfunction "1_P$1") (pintype "passive"))
      (node (ref "JP77") (pin "1") (pinfunction "1_1") (pintype "passive"))
    )
    (net (code "251") (name "/190_1440304149") (class "Default")
      (node (ref "JP1098") (pin "P$1") (pinfunction "1_P$1") (pintype "passive"))
      (node (ref "JP87") (pin "1") (pinfunction "1_1") (pintype "passive"))
    )
    (net (code "252") (name "/191_1440304149") (class "Default")
      (node (ref "JP1100") (pin "P$1") (pinfunction "1_P$1") (pintype "passive"))
      (node (ref "JP97") (pin "1") (pinfunction "1_1") (pintype "passive"))
    )
    (net (code "253") (name "/192_1440304149") (class "Default")
      (node (ref "JP107") (pin "1") (pinfunction "1_1") (pintype "passive"))
      (node (ref "JP1102") (pin "P$1") (pinfunction "1_P$1") (pintype "passive"))
    )
    (net (code "254") (name "/193_1440304149") (class "Default")
      (node (ref "JP1104") (pin "P$1") (pinfunction "1_P$1") (pintype "passive"))
      (node (ref "JP117") (pin "1") (pinfunction "1_1") (pintype "passive"))
    )
    (net (code "255") (name "/194_1440304149") (class "Default")
      (node (ref "JP1106") (pin "P$1") (pinfunction "1_P$1") (pintype "passive"))
      (node (ref "JP127") (pin "1") (pinfunction "1_1") (pintype "passive"))
    )
    (net (code "256") (name "/195_1440304149") (class "Default")
      (node (ref "JP1108") (pin "P$1") (pinfunction "1_P$1") (pintype "passive"))
      (node (ref "JP137") (pin "1") (pinfunction "1_1") (pintype "passive"))
    )
    (net (code "257") (name "/196_1440304149") (class "Default")
      (node (ref "JP1110") (pin "P$1") (pinfunction "1_P$1") (pintype "passive"))
      (node (ref "JP147") (pin "1") (pinfunction "1_1") (pintype "passive"))
    )
    (net (code "258") (name "/197_1440304149") (class "Default")
      (node (ref "JP1112") (pin "P$1") (pinfunction "1_P$1") (pintype "passive"))
      (node (ref "JP157") (pin "1") (pinfunction "1_1") (pintype "passive"))
    )
    (net (code "259") (name "/198_1440304149") (class "Default")
      (node (ref "JP1114") (pin "P$1") (pinfunction "1_P$1") (pintype "passive"))
      (node (ref "JP167") (pin "1") (pinfunction "1_1") (pintype "passive"))
    )
    (net (code "260") (name "/199_1440304149") (class "Default")
      (node (ref "JP1116") (pin "P$1") (pinfunction "1_P$1") (pintype "passive"))
      (node (ref "JP177") (pin "1") (pinfunction "1_1") (pintype "passive"))
    )
    (net (code "261") (name "/200_1440304149") (class "Default")
      (node (ref "JP1118") (pin "P$1") (pinfunction "1_P$1") (pintype "passive"))
      (node (ref "JP187") (pin "1") (pinfunction "1_1") (pintype "passive"))
    )
    (net (code "262") (name "/201_1440304149") (class "Default")
      (node (ref "JP1120") (pin "P$1") (pinfunction "1_P$1") (pintype "passive"))
      (node (ref "JP197") (pin "1") (pinfunction "1_1") (pintype "passive"))
    )
    (net (code "263") (name "/202_1440304149") (class "Default")
      (node (ref "JP1122") (pin "P$1") (pinfunction "1_P$1") (pintype "passive"))
      (node (ref "JP207") (pin "1") (pinfunction "1_1") (pintype "passive"))
    )
    (net (code "264") (name "/203_1440304149") (class "Default")
      (node (ref "JP1124") (pin "P$1") (pinfunction "1_P$1") (pintype "passive"))
      (node (ref "JP217") (pin "1") (pinfunction "1_1") (pintype "passive"))
    )
    (net (code "265") (name "/204_1440304149") (class "Default")
      (node (ref "JP1126") (pin "P$1") (pinfunction "1_P$1") (pintype "passive"))
      (node (ref "JP227") (pin "1") (pinfunction "1_1") (pintype "passive"))
    )
    (net (code "266") (name "/205_1440304149") (class "Default")
      (node (ref "JP1128") (pin "P$1") (pinfunction "1_P$1") (pintype "passive"))
      (node (ref "JP237") (pin "1") (pinfunction "1_1") (pintype "passive"))
    )
    (net (code "267") (name "/206_1440304149") (class "Default")
      (node (ref "JP1130") (pin "P$1") (pinfunction "1_P$1") (pintype "passive"))
      (node (ref "JP247") (pin "1") (pinfunction "1_1") (pintype "passive"))
    )
    (net (code "268") (name "/207_1440304149") (class "Default")
      (node (ref "JP1132") (pin "P$1") (pinfunction "1_P$1") (pintype "passive"))
      (node (ref "JP257") (pin "1") (pinfunction "1_1") (pintype "passive"))
    )
    (net (code "269") (name "/208_1440304149") (class "Default")
      (node (ref "JP1134") (pin "P$1") (pinfunction "1_P$1") (pintype "passive"))
      (node (ref "JP267") (pin "1") (pinfunction "1_1") (pintype "passive"))
    )
    (net (code "270") (name "/209_1440304149") (class "Default")
      (node (ref "JP1136") (pin "P$1") (pinfunction "1_P$1") (pintype "passive"))
      (node (ref "JP277") (pin "1") (pinfunction "1_1") (pintype "passive"))
    )
    (net (code "271") (name "/210_1440304149") (class "Default")
      (node (ref "JP1138") (pin "P$1") (pinfunction "1_P$1") (pintype "passive"))
      (node (ref "JP287") (pin "1") (pinfunction "1_1") (pintype "passive"))
    )
    (net (code "272") (name "/211_1440304149") (class "Default")
      (node (ref "JP4") (pin "1") (pinfunction "1_1") (pintype "passive"))
      (node (ref "JP902") (pin "P$1") (pinfunction "1_P$1") (pintype "passive"))
    )
    (net (code "273") (name "/212_1440304149") (class "Default")
      (node (ref "JP14") (pin "1") (pinfunction "1_1") (pintype "passive"))
      (node (ref "JP904") (pin "P$1") (pinfunction "1_P$1") (pintype "passive"))
    )
    (net (code "274") (name "/213_1440304149") (class "Default")
      (node (ref "JP24") (pin "1") (pinfunction "1_1") (pintype "passive"))
      (node (ref "JP906") (pin "P$1") (pinfunction "1_P$1") (pintype "passive"))
    )
    (net (code "275") (name "/214_1440304149") (class "Default")
      (node (ref "JP34") (pin "1") (pinfunction "1_1") (pintype "passive"))
      (node (ref "JP908") (pin "P$1") (pinfunction "1_P$1") (pintype "passive"))
    )
    (net (code "276") (name "/215_1440304149") (class "Default")
      (node (ref "JP44") (pin "1") (pinfunction "1_1") (pintype "passive"))
      (node (ref "JP910") (pin "P$1") (pinfunction "1_P$1") (pintype "passive"))
    )
    (net (code "277") (name "/216_1440304149") (class "Default")
      (node (ref "JP54") (pin "1") (pinfunction "1_1") (pintype "passive"))
      (node (ref "JP912") (pin "P$1") (pinfunction "1_P$1") (pintype "passive"))
    )
    (net (code "278") (name "/217_1440304149") (class "Default")
      (node (ref "JP64") (pin "1") (pinfunction "1_1") (pintype "passive"))
      (node (ref "JP914") (pin "P$1") (pinfunction "1_P$1") (pintype "passive"))
    )
    (net (code "279") (name "/218_1440304149") (class "Default")
      (node (ref "JP74") (pin "1") (pinfunction "1_1") (pintype "passive"))
      (node (ref "JP916") (pin "P$1") (pinfunction "1_P$1") (pintype "passive"))
    )
    (net (code "280") (name "/219_1440304149") (class "Default")
      (node (ref "JP84") (pin "1") (pinfunction "1_1") (pintype "passive"))
      (node (ref "JP918") (pin "P$1") (pinfunction "1_P$1") (pintype "passive"))
    )
    (net (code "281") (name "/220_1440304149") (class "Default")
      (node (ref "JP920") (pin "P$1") (pinfunction "1_P$1") (pintype "passive"))
      (node (ref "JP94") (pin "1") (pinfunction "1_1") (pintype "passive"))
    )
    (net (code "282") (name "/221_1440304149") (class "Default")
      (node (ref "JP104") (pin "1") (pinfunction "1_1") (pintype "passive"))
      (node (ref "JP922") (pin "P$1") (pinfunction "1_P$1") (pintype "passive"))
    )
    (net (code "283") (name "/222_1440304149") (class "Default")
      (node (ref "JP114") (pin "1") (pinfunction "1_1") (pintype "passive"))
      (node (ref "JP924") (pin "P$1") (pinfunction "1_P$1") (pintype "passive"))
    )
    (net (code "284") (name "/223_1440304149") (class "Default")
      (node (ref "JP124") (pin "1") (pinfunction "1_1") (pintype "passive"))
      (node (ref "JP926") (pin "P$1") (pinfunction "1_P$1") (pintype "passive"))
    )
    (net (code "285") (name "/224_1440304149") (class "Default")
      (node (ref "JP134") (pin "1") (pinfunction "1_1") (pintype "passive"))
      (node (ref "JP928") (pin "P$1") (pinfunction "1_P$1") (pintype "passive"))
    )
    (net (code "286") (name "/225_1440304149") (class "Default")
      (node (ref "JP144") (pin "1") (pinfunction "1_1") (pintype "passive"))
      (node (ref "JP930") (pin "P$1") (pinfunction "1_P$1") (pintype "passive"))
    )
    (net (code "287") (name "/226_1440304149") (class "Default")
      (node (ref "JP154") (pin "1") (pinfunction "1_1") (pintype "passive"))
      (node (ref "JP932") (pin "P$1") (pinfunction "1_P$1") (pintype "passive"))
    )
    (net (code "288") (name "/227_1440304149") (class "Default")
      (node (ref "JP164") (pin "1") (pinfunction "1_1") (pintype "passive"))
      (node (ref "JP934") (pin "P$1") (pinfunction "1_P$1") (pintype "passive"))
    )
    (net (code "289") (name "/228_1440304149") (class "Default")
      (node (ref "JP174") (pin "1") (pinfunction "1_1") (pintype "passive"))
      (node (ref "JP936") (pin "P$1") (pinfunction "1_P$1") (pintype "passive"))
    )
    (net (code "290") (name "/229_1440304149") (class "Default")
      (node (ref "JP184") (pin "1") (pinfunction "1_1") (pintype "passive"))
      (node (ref "JP938") (pin "P$1") (pinfunction "1_P$1") (pintype "passive"))
    )
    (net (code "291") (name "/230_1440304149") (class "Default")
      (node (ref "JP194") (pin "1") (pinfunction "1_1") (pintype "passive"))
      (node (ref "JP940") (pin "P$1") (pinfunction "1_P$1") (pintype "passive"))
    )
    (net (code "292") (name "/231_1440304149") (class "Default")
      (node (ref "JP204") (pin "1") (pinfunction "1_1") (pintype "passive"))
      (node (ref "JP942") (pin "P$1") (pinfunction "1_P$1") (pintype "passive"))
    )
    (net (code "293") (name "/232_1440304149") (class "Default")
      (node (ref "JP214") (pin "1") (pinfunction "1_1") (pintype "passive"))
      (node (ref "JP944") (pin "P$1") (pinfunction "1_P$1") (pintype "passive"))
    )
    (net (code "294") (name "/233_1440304149") (class "Default")
      (node (ref "JP224") (pin "1") (pinfunction "1_1") (pintype "passive"))
      (node (ref "JP946") (pin "P$1") (pinfunction "1_P$1") (pintype "passive"))
    )
    (net (code "295") (name "/234_1440304149") (class "Default")
      (node (ref "JP234") (pin "1") (pinfunction "1_1") (pintype "passive"))
      (node (ref "JP948") (pin "P$1") (pinfunction "1_P$1") (pintype "passive"))
    )
    (net (code "296") (name "/235_1440304149") (class "Default")
      (node (ref "JP244") (pin "1") (pinfunction "1_1") (pintype "passive"))
      (node (ref "JP950") (pin "P$1") (pinfunction "1_P$1") (pintype "passive"))
    )
    (net (code "297") (name "/236_1440304149") (class "Default")
      (node (ref "JP254") (pin "1") (pinfunction "1_1") (pintype "passive"))
      (node (ref "JP952") (pin "P$1") (pinfunction "1_P$1") (pintype "passive"))
    )
    (net (code "298") (name "/237_1440304149") (class "Default")
      (node (ref "JP264") (pin "1") (pinfunction "1_1") (pintype "passive"))
      (node (ref "JP954") (pin "P$1") (pinfunction "1_P$1") (pintype "passive"))
    )
    (net (code "299") (name "/238_1440304149") (class "Default")
      (node (ref "JP274") (pin "1") (pinfunction "1_1") (pintype "passive"))
      (node (ref "JP956") (pin "P$1") (pinfunction "1_P$1") (pintype "passive"))
    )
    (net (code "300") (name "/239_1440304149") (class "Default")
      (node (ref "JP284") (pin "1") (pinfunction "1_1") (pintype "passive"))
      (node (ref "JP958") (pin "P$1") (pinfunction "1_P$1") (pintype "passive"))
    )
  )
)
